# eps_version_0_4_0.net
KiCad netlist of a schematic drawn in EAGLE
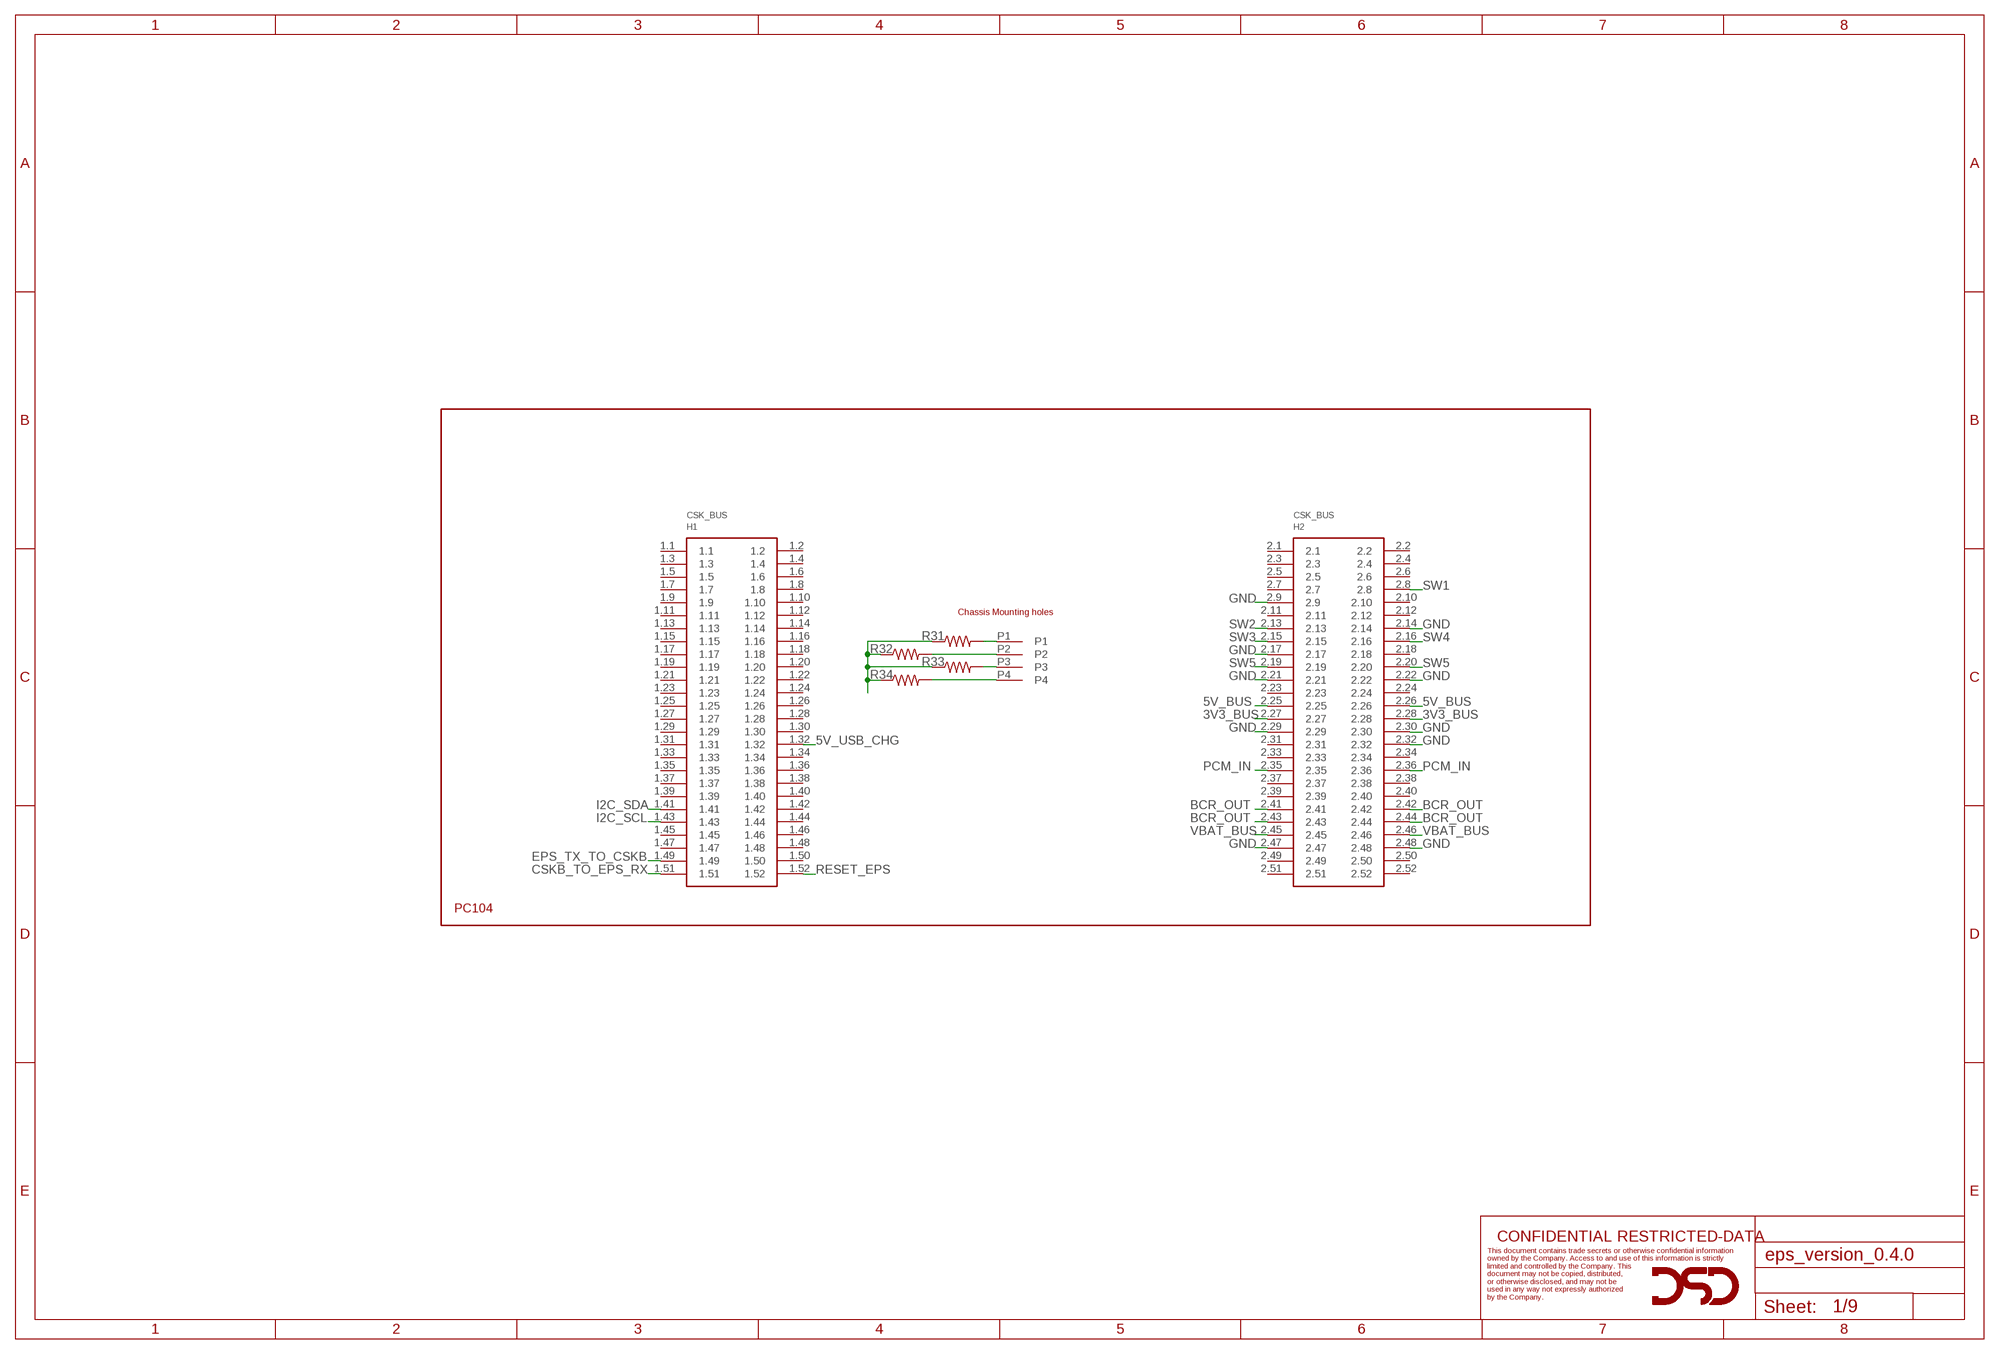
[diagram p0: schematic, sheet 1]
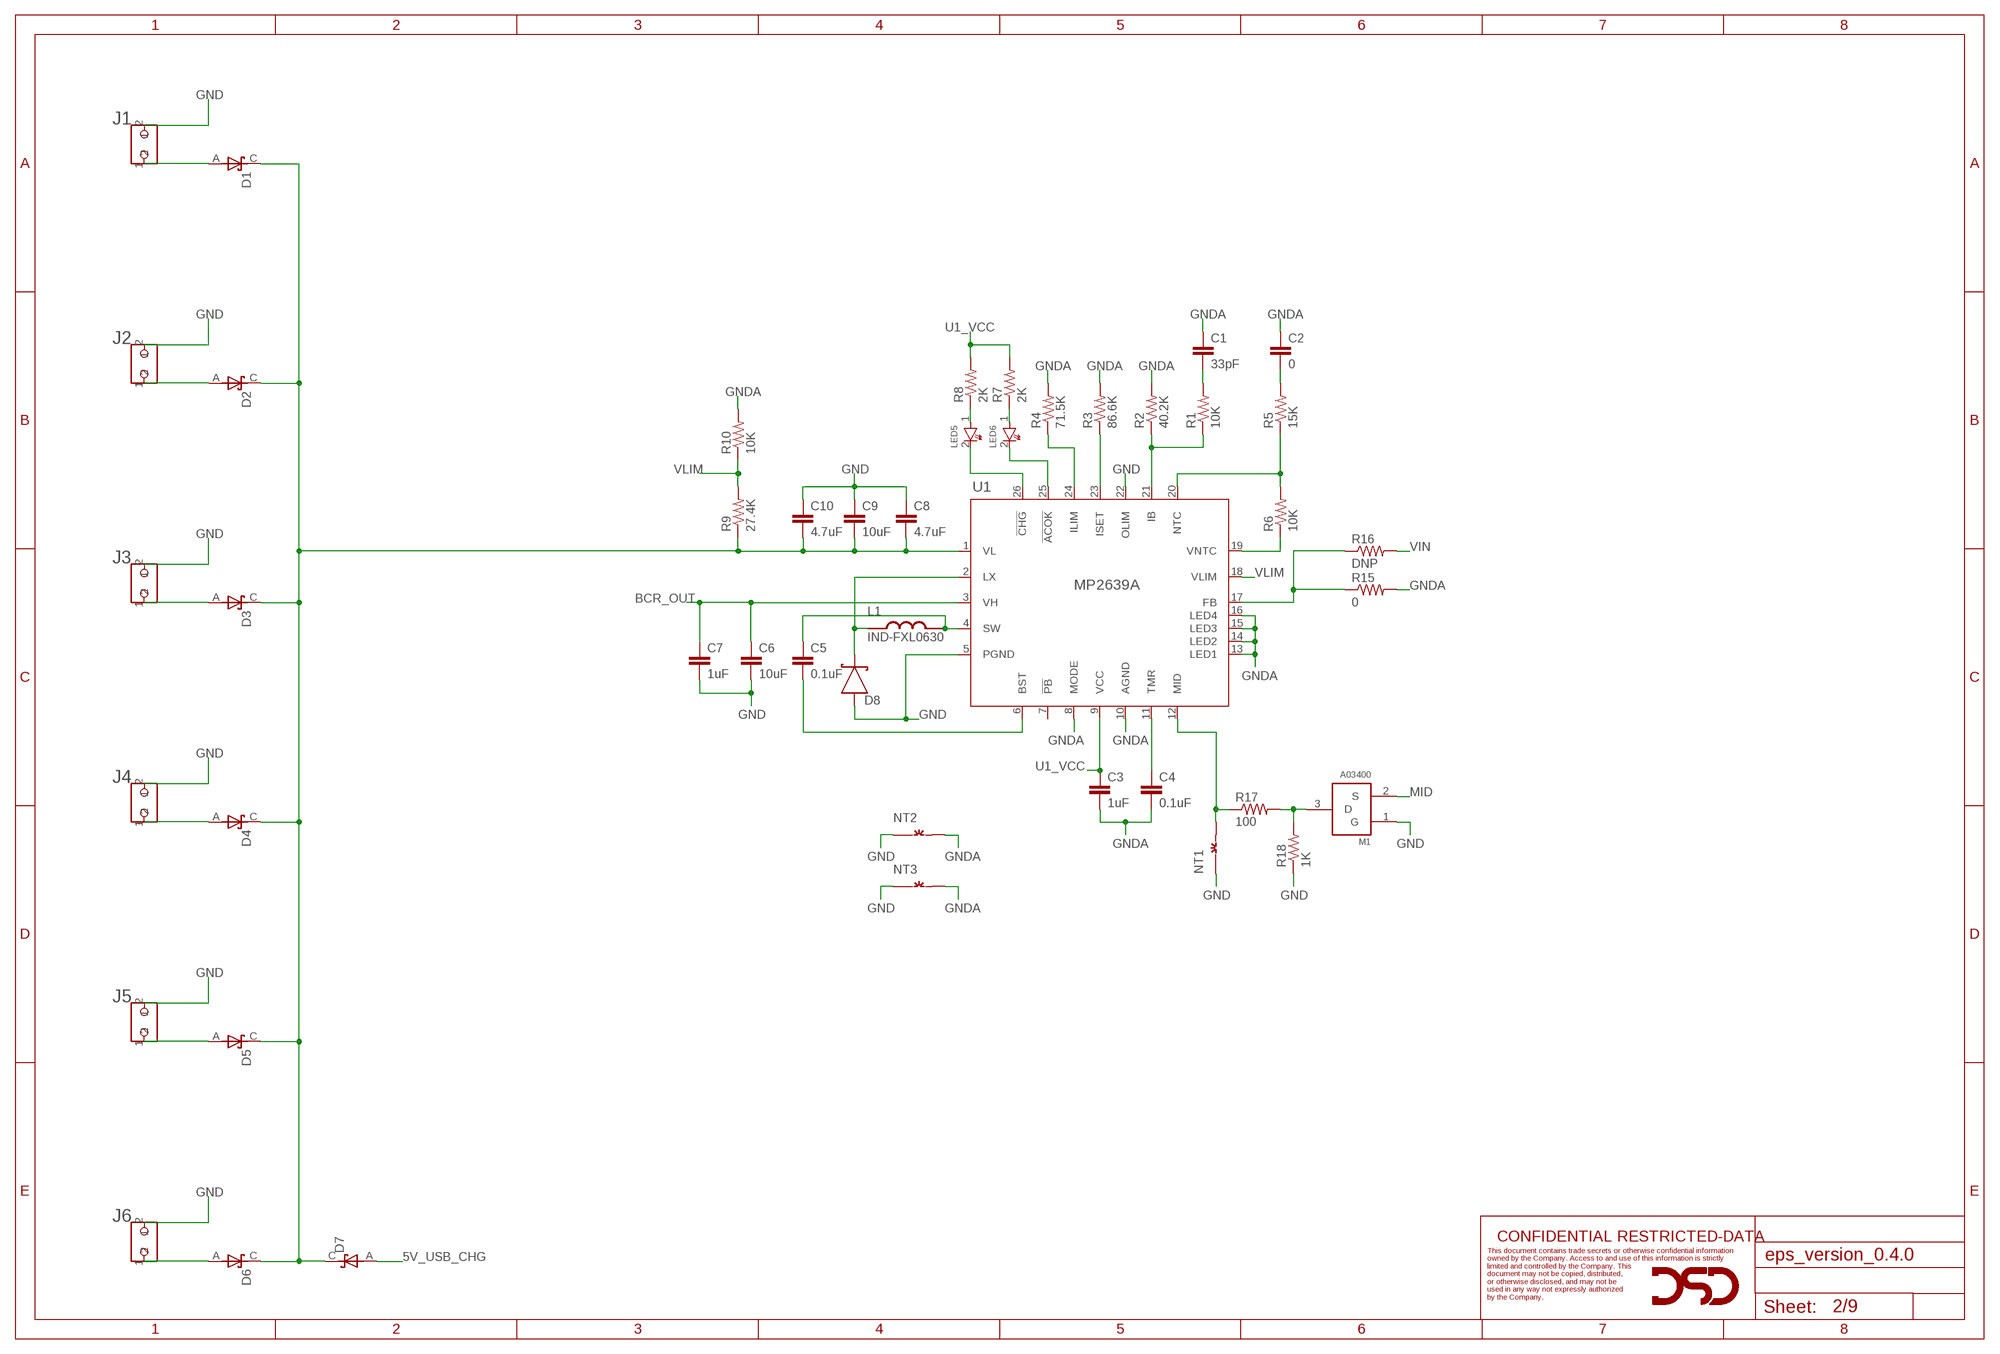
[diagram p1: schematic, sheet 2]
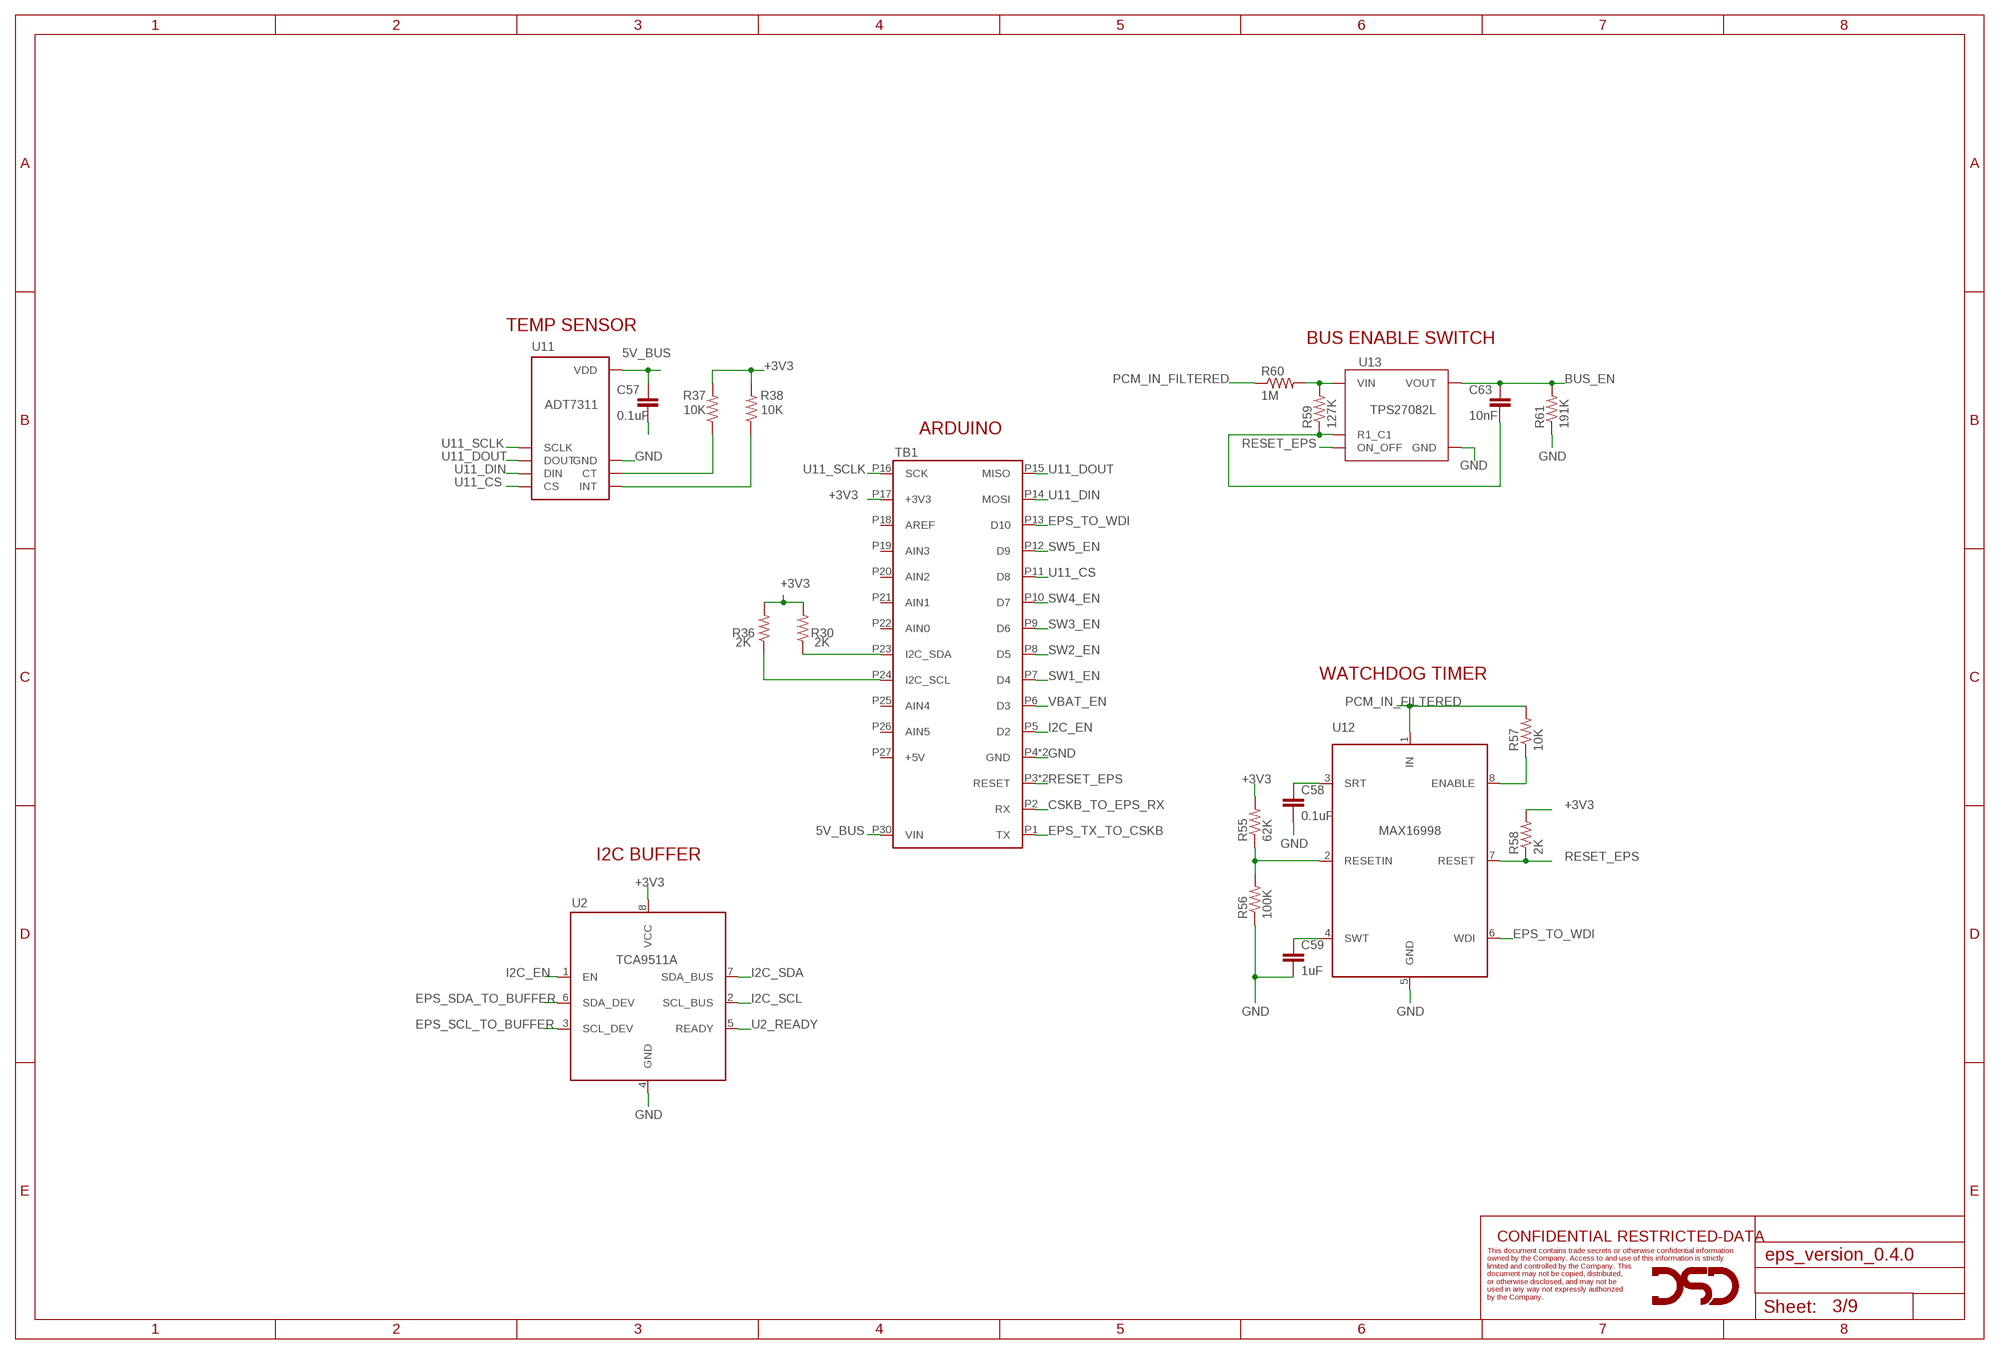
[diagram p2: schematic, sheet 3]
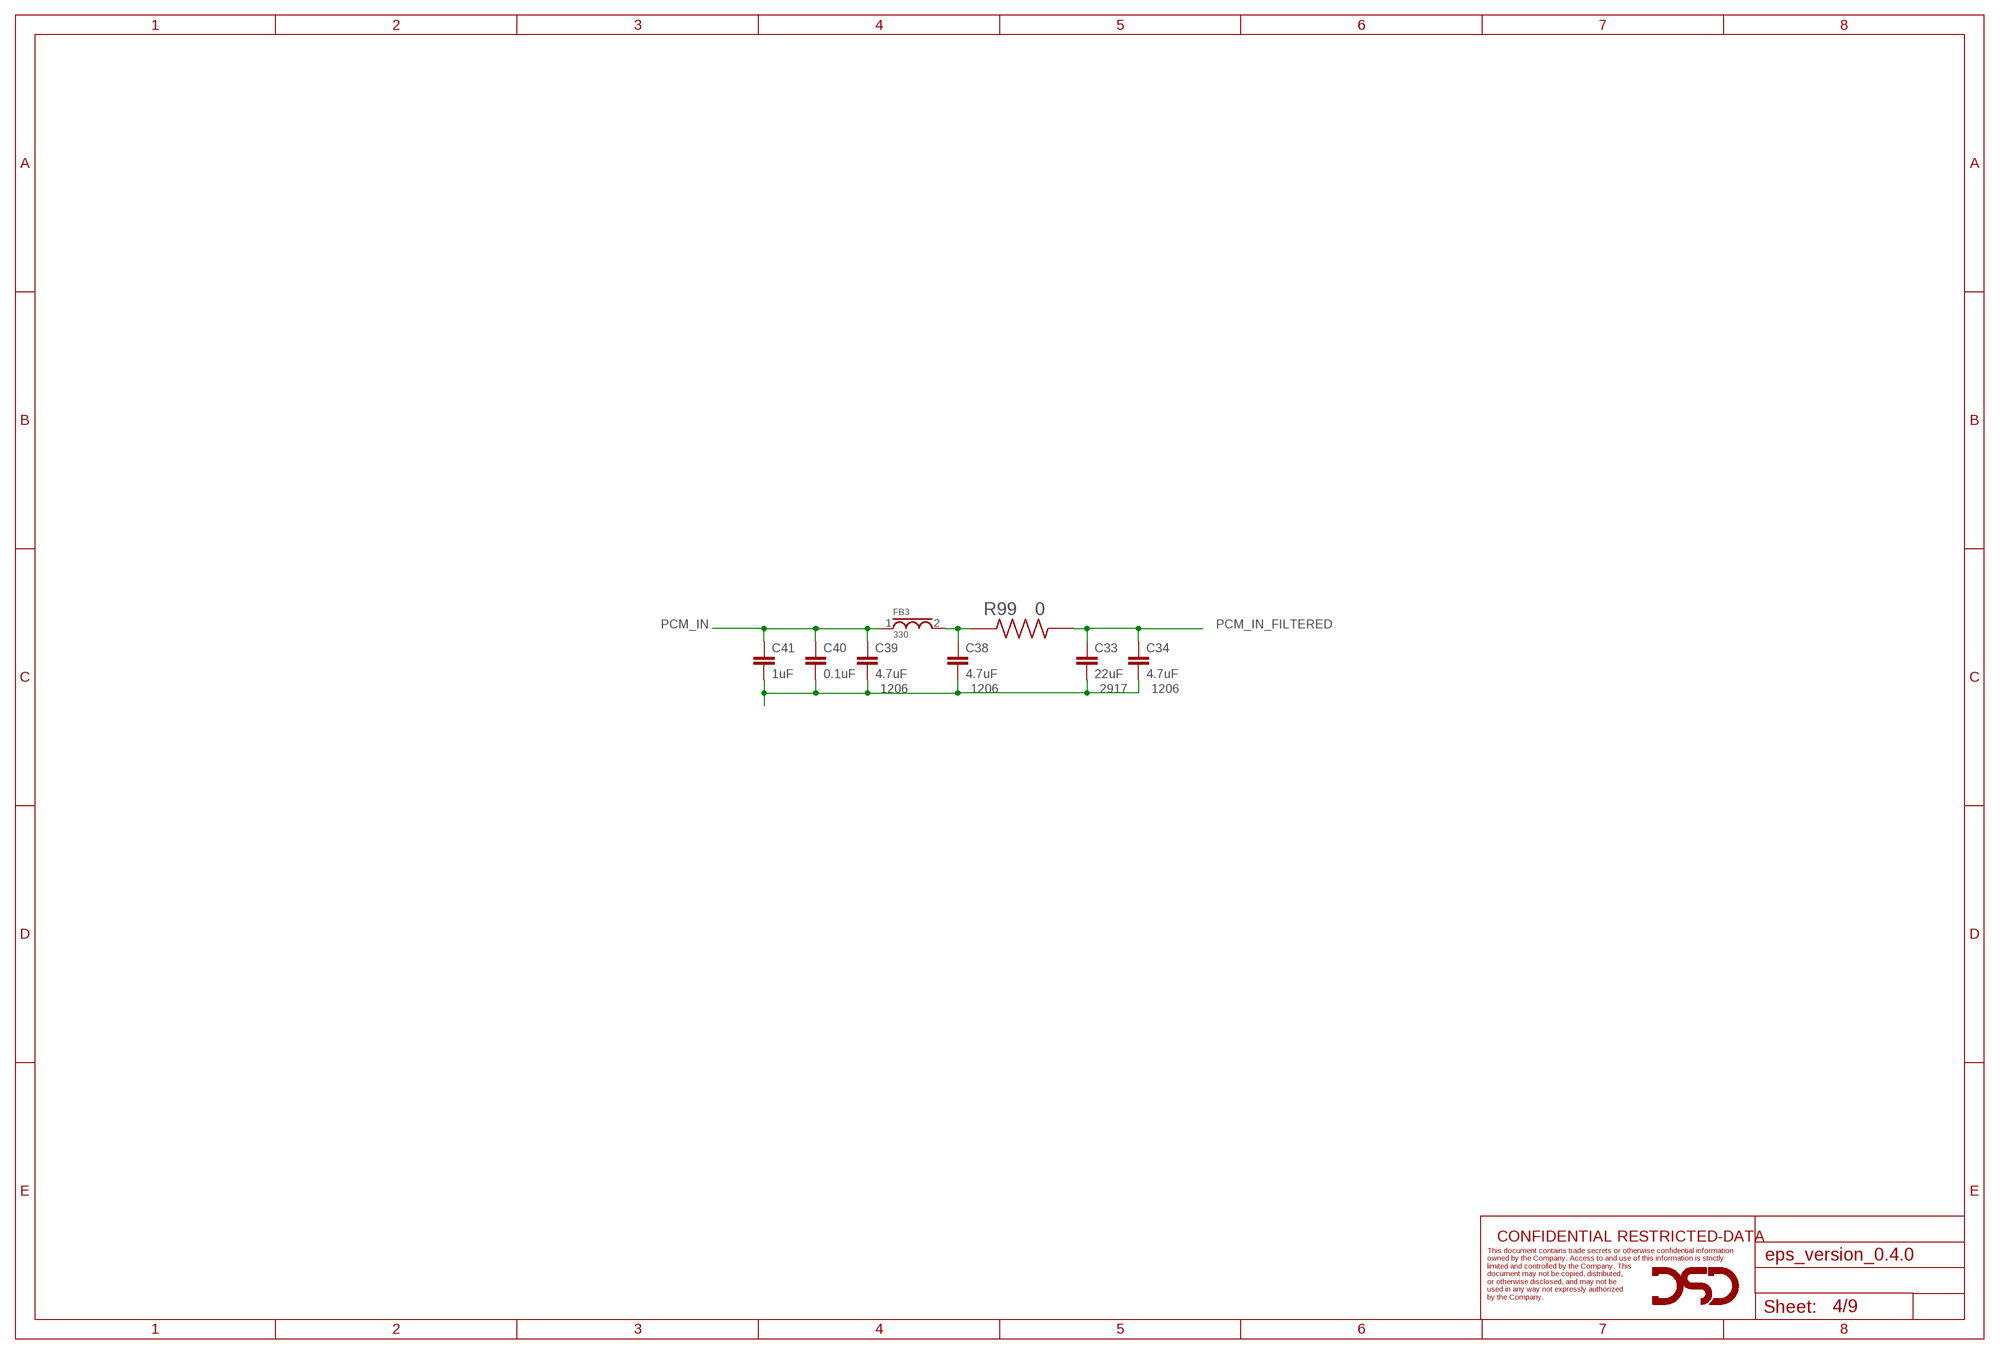
[diagram p3: schematic, sheet 4]
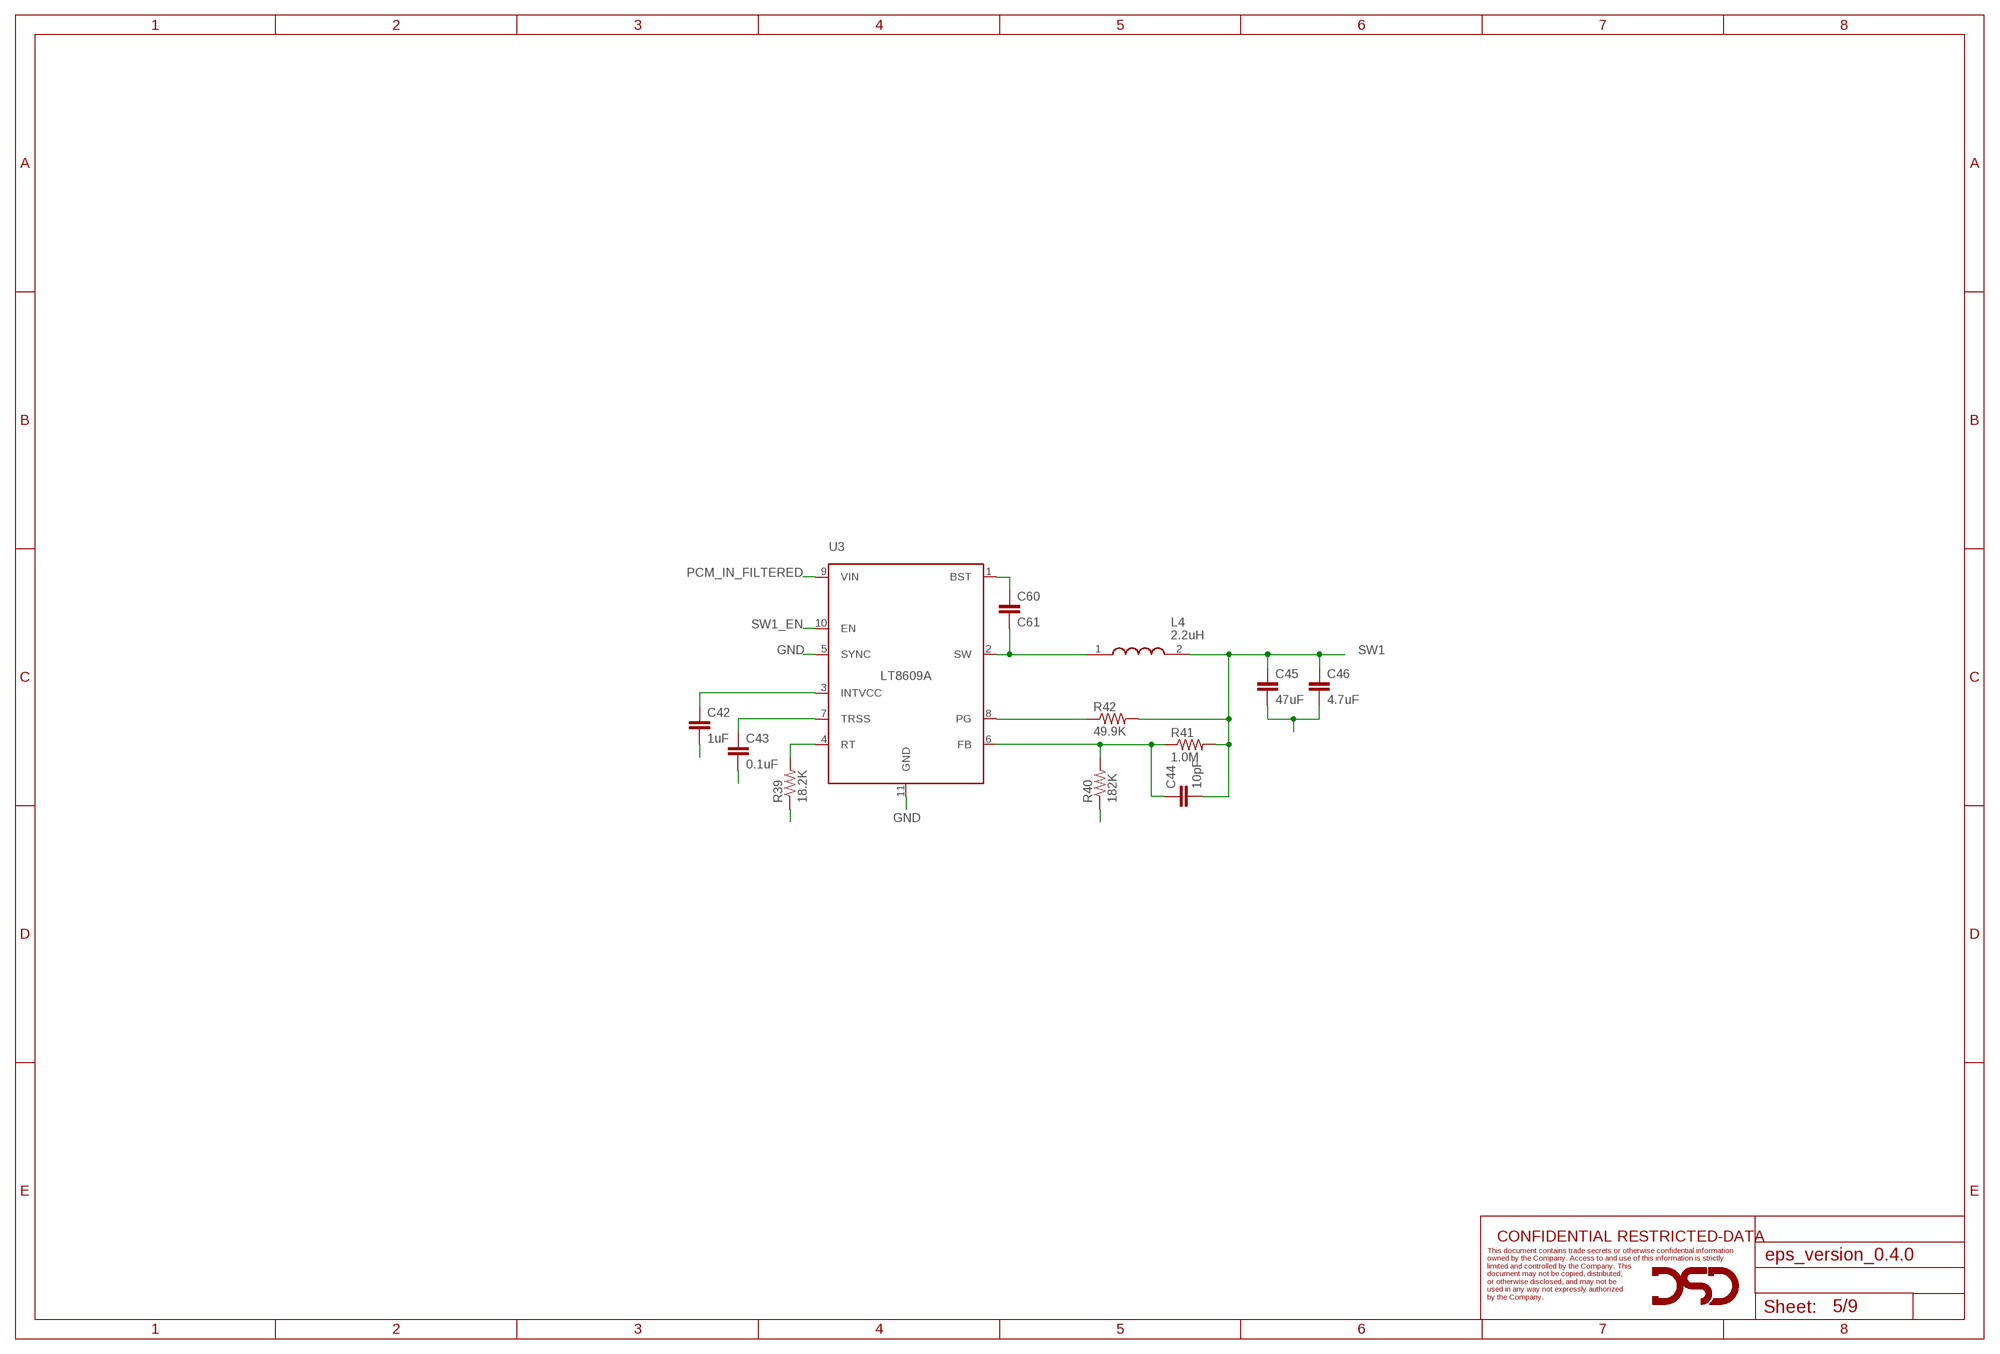
[diagram p4: schematic, sheet 5]
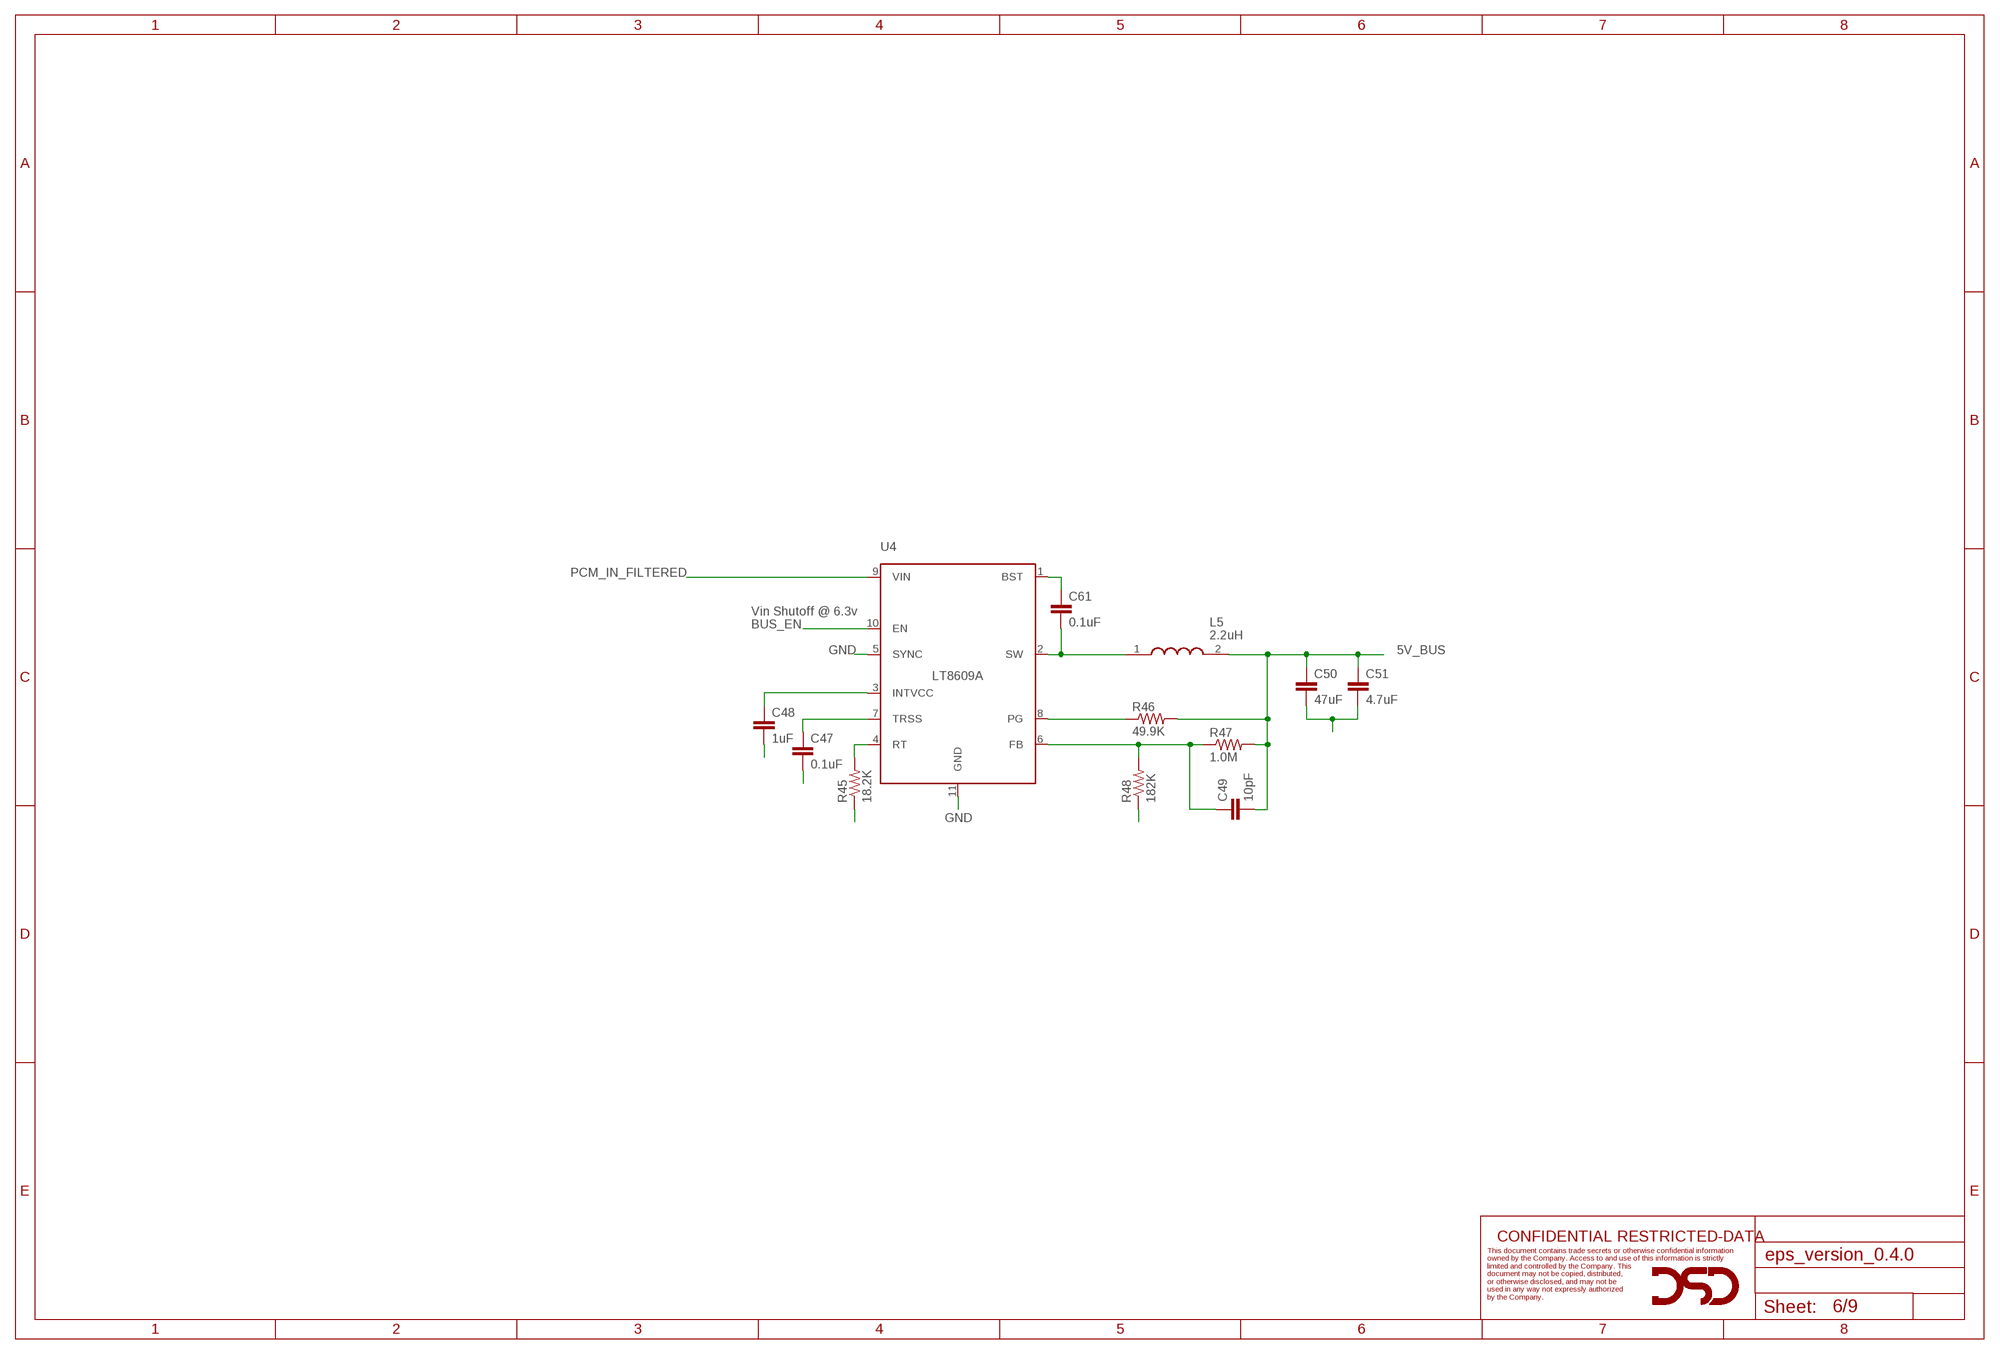
[diagram p5: schematic, sheet 6]
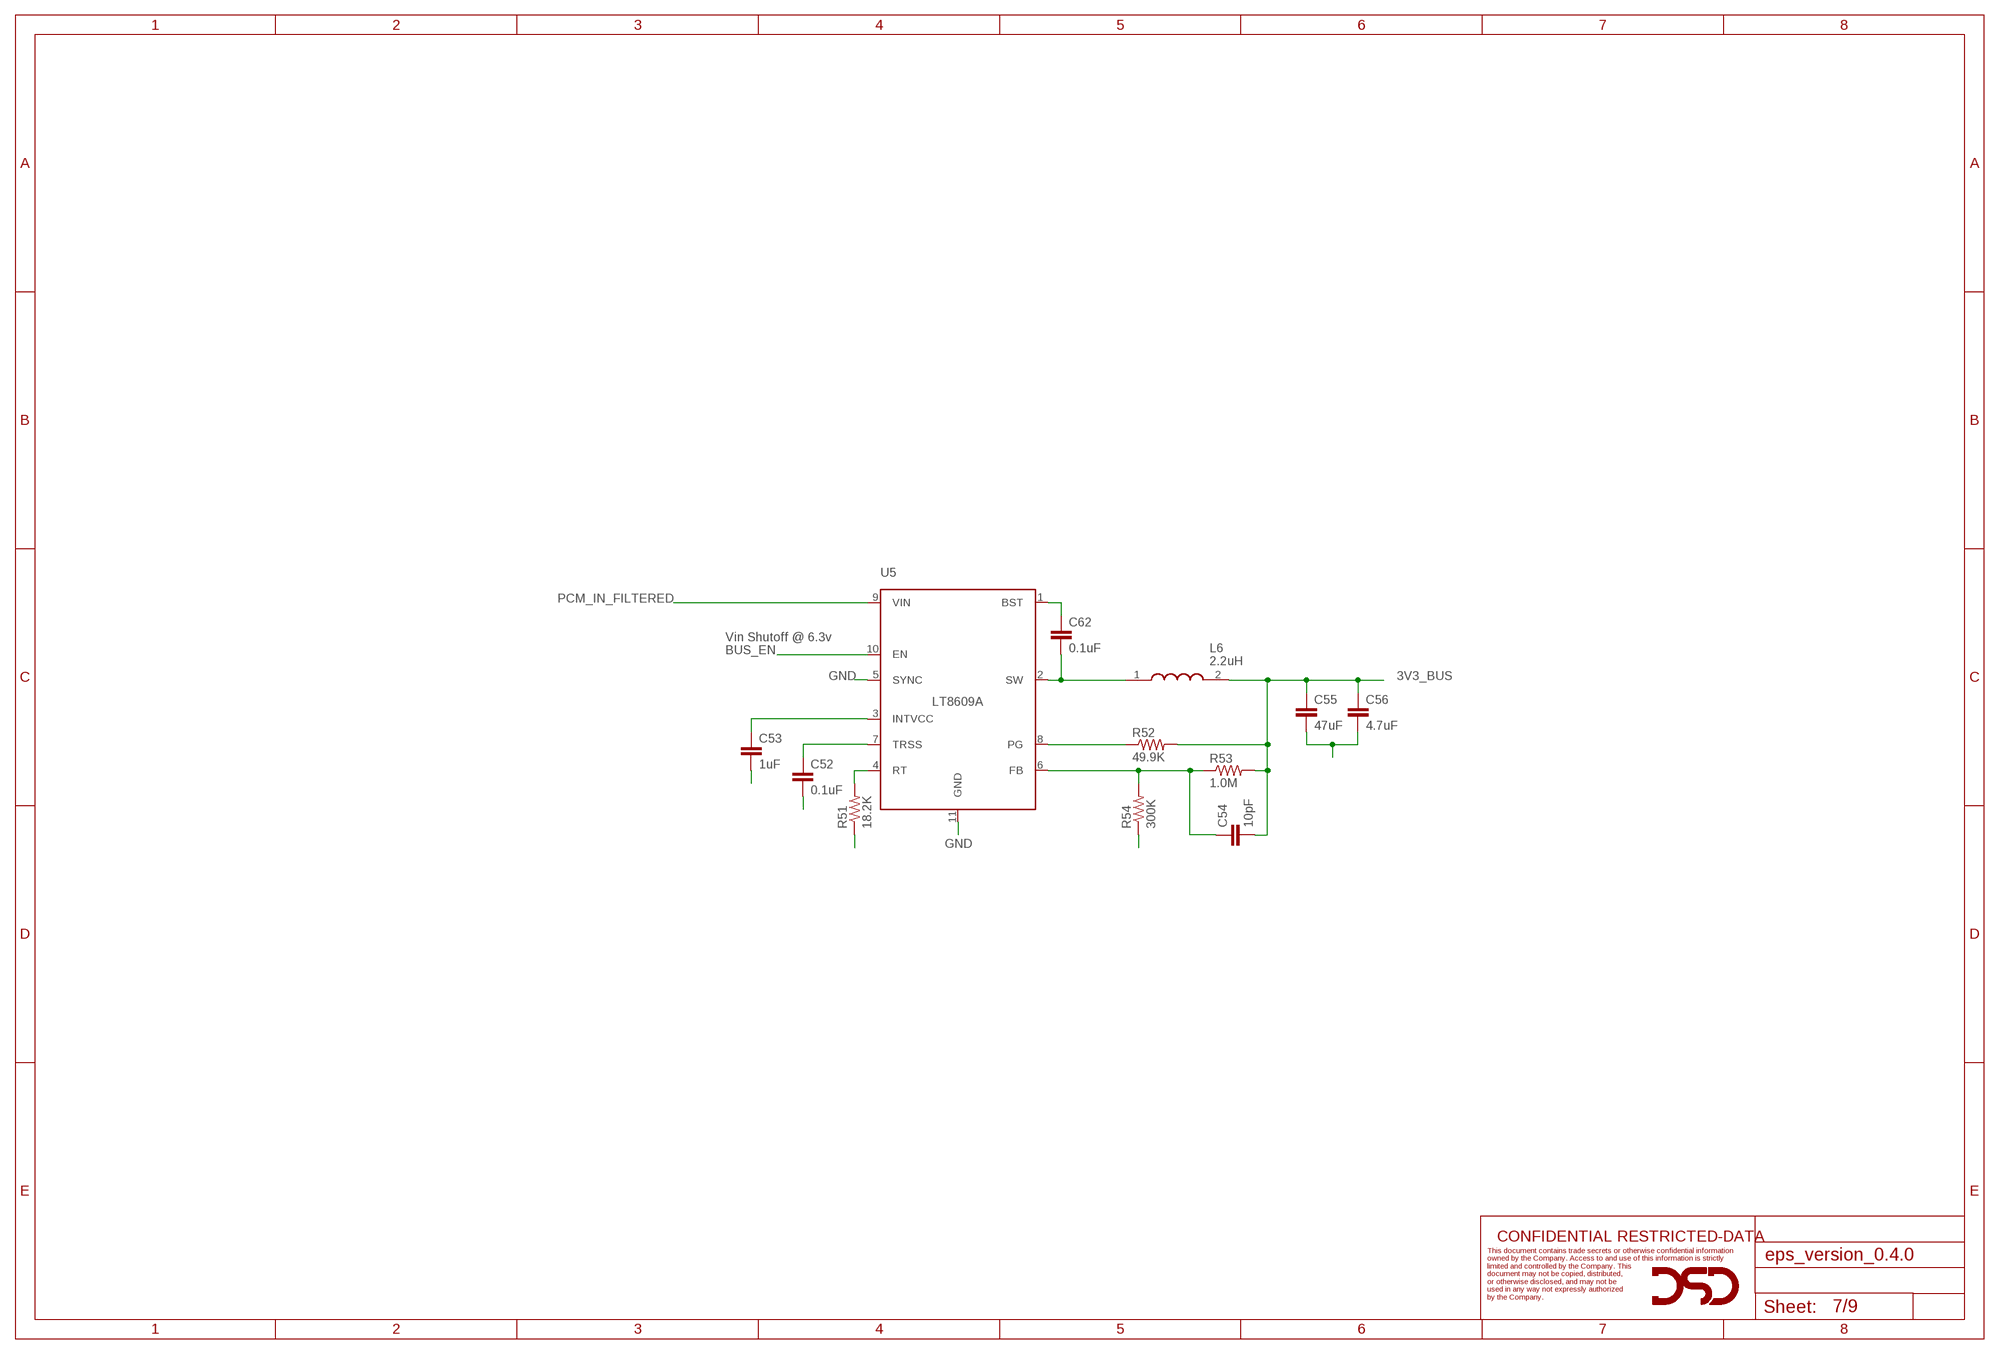
[diagram p6: schematic, sheet 7]
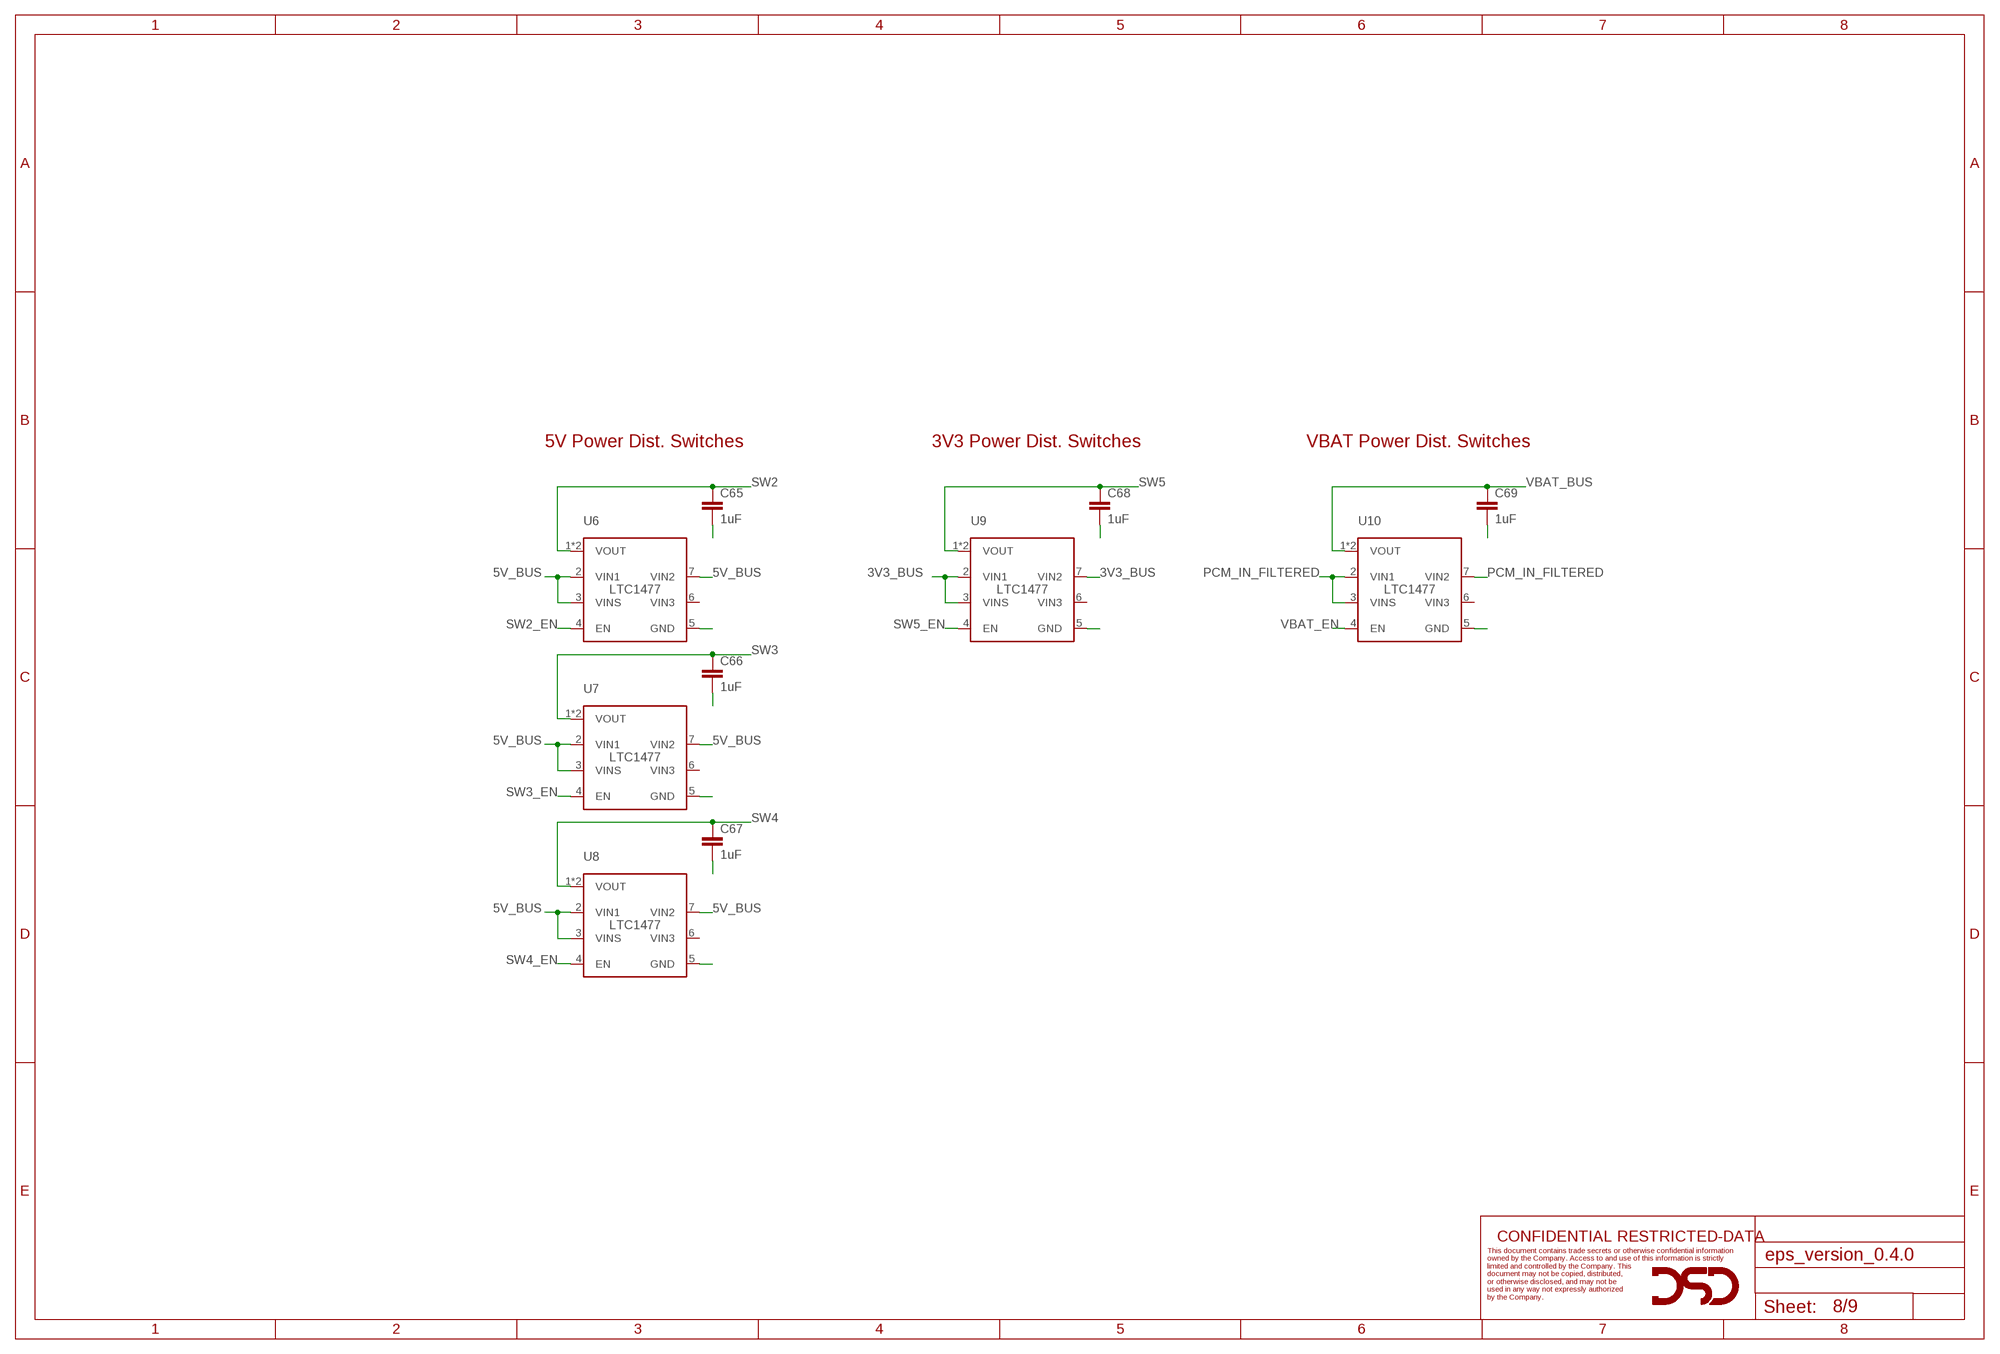
[diagram p7: schematic, sheet 8]
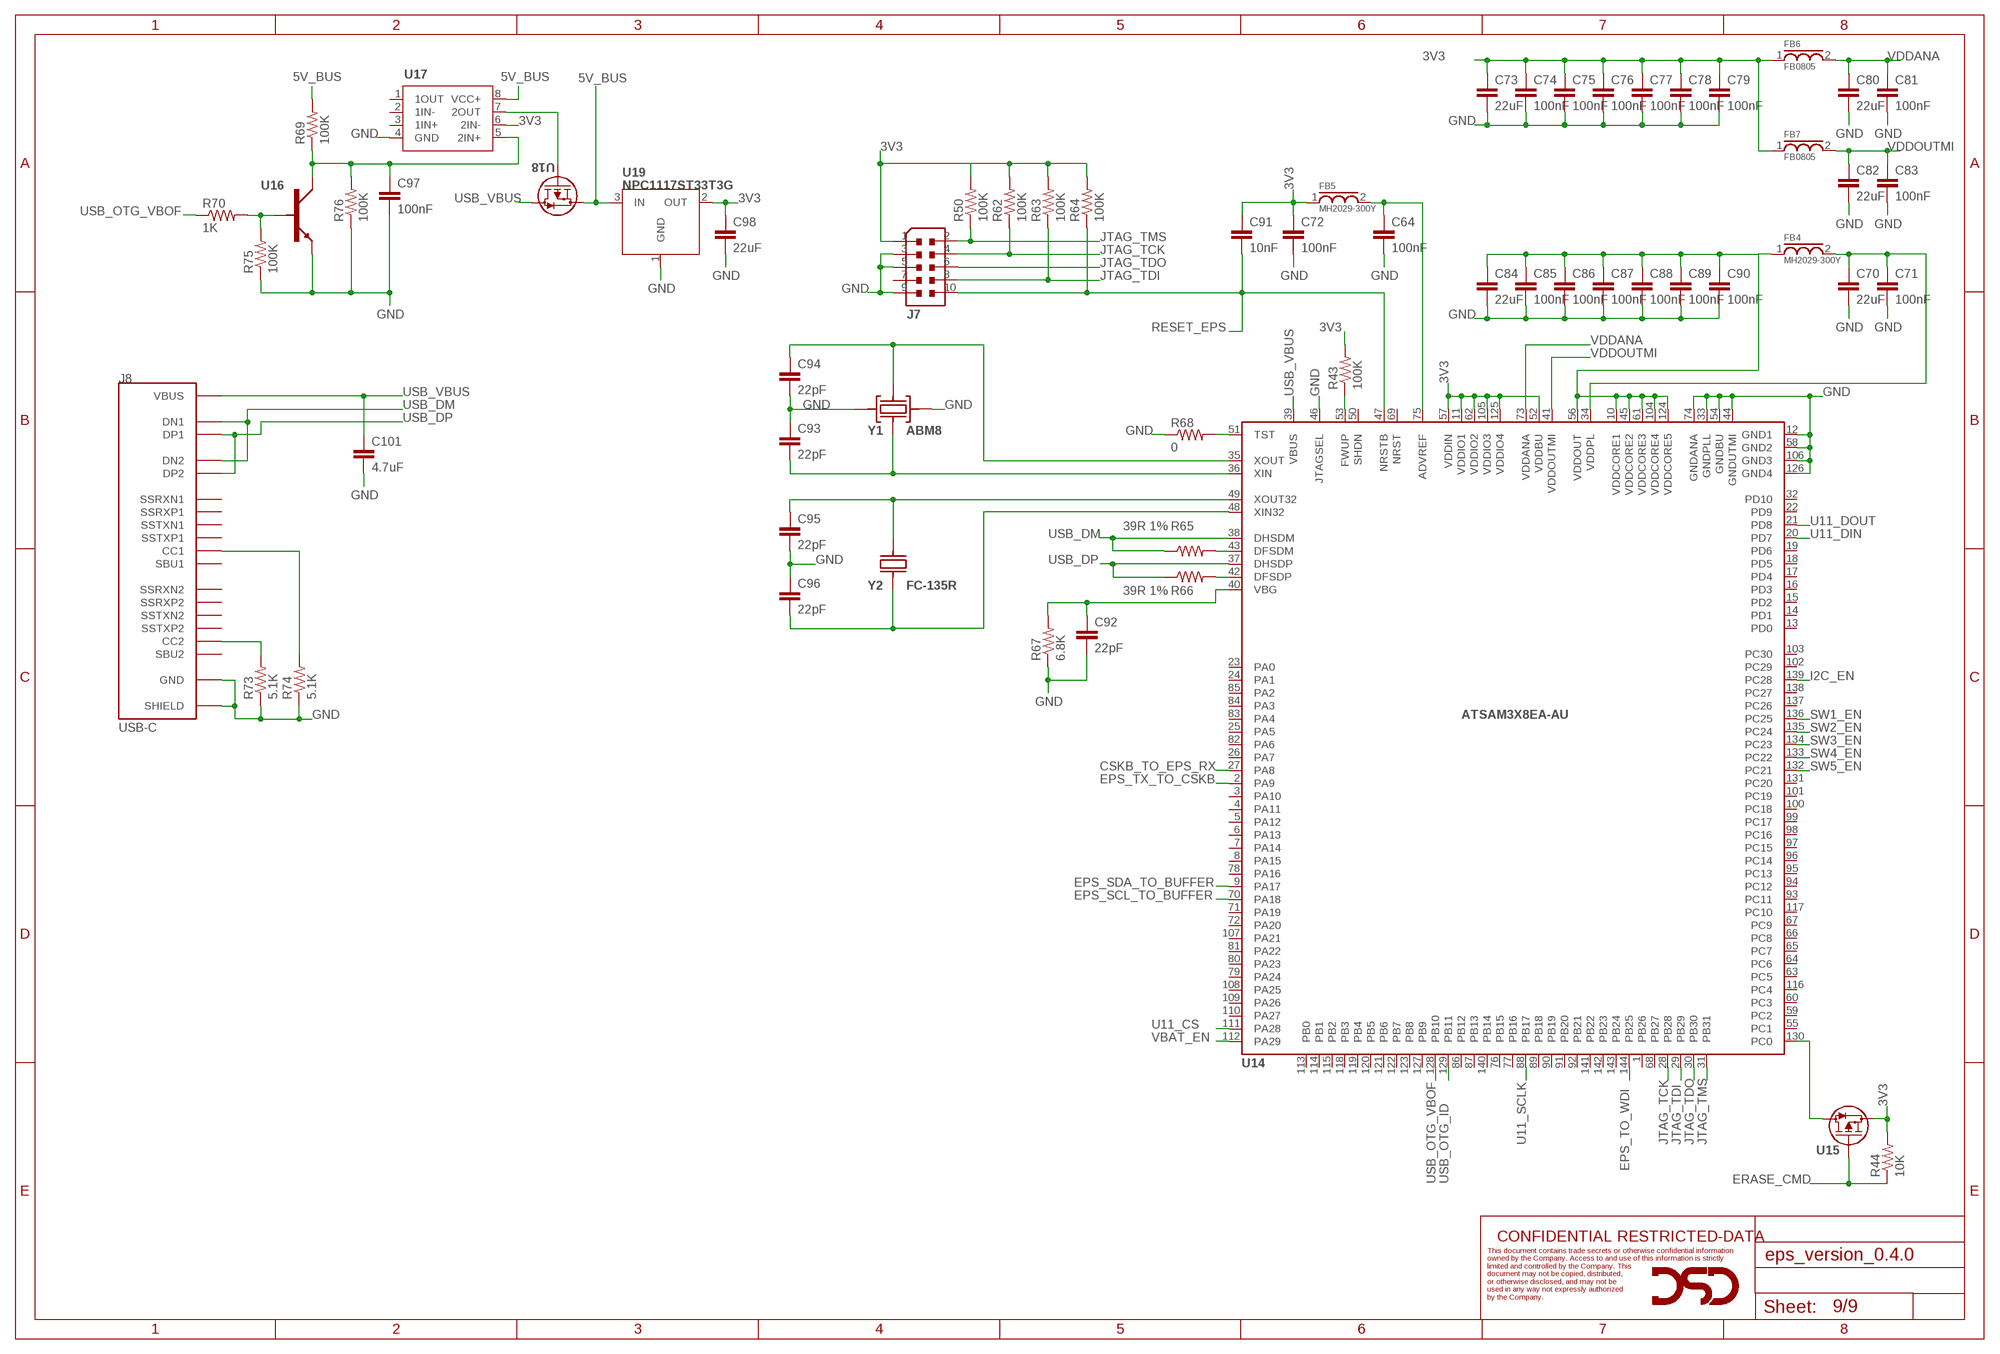
[diagram p8: schematic, sheet 9]

(export (version "E")
  (design (tool "Eeschema 10.0.6"))
  (components
    (comp (ref "C57")
      (value "0.1uF")
      (footprint "eagle-import:0805")
      (libsource (lib "eagle-import") (part "HSFL_Main_Library_CAP0805"))
    )
    (comp (ref "C58")
      (value "0.1uF")
      (footprint "eagle-import:0805")
      (libsource (lib "eagle-import") (part "HSFL_Main_Library_CAP0805"))
    )
    (comp (ref "C59")
      (value "1uF")
      (footprint "eagle-import:0805")
      (libsource (lib "eagle-import") (part "HSFL_Main_Library_CAP0805"))
    )
    (comp (ref "C63")
      (value "10nF")
      (footprint "eagle-import:0805")
      (libsource (lib "eagle-import") (part "HSFL_Main_Library_CAP0805"))
    )
    (comp (ref "R30")
      (value "2K")
      (footprint "eagle-import:0805")
      (libsource (lib "eagle-import") (part "HSFL_Main_Library_RESISTOR0805-RES"))
    )
    (comp (ref "R36")
      (value "2K")
      (footprint "eagle-import:0805")
      (libsource (lib "eagle-import") (part "HSFL_Main_Library_RESISTOR0805-RES"))
    )
    (comp (ref "R37")
      (value "10K")
      (footprint "eagle-import:0805")
      (libsource (lib "eagle-import") (part "HSFL_Main_Library_RESISTOR0805-RES"))
    )
    (comp (ref "R38")
      (value "10K")
      (footprint "eagle-import:0805")
      (libsource (lib "eagle-import") (part "HSFL_Main_Library_RESISTOR0805-RES"))
    )
    (comp (ref "R55")
      (value "62K")
      (footprint "eagle-import:0805")
      (libsource (lib "eagle-import") (part "HSFL_Main_Library_RESISTOR0805-RES"))
    )
    (comp (ref "R56")
      (value "100K")
      (footprint "eagle-import:0805")
      (libsource (lib "eagle-import") (part "HSFL_Main_Library_RESISTOR0805-RES"))
    )
    (comp (ref "R57")
      (value "10K")
      (footprint "eagle-import:0805")
      (libsource (lib "eagle-import") (part "HSFL_Main_Library_RESISTOR0805-RES"))
    )
    (comp (ref "R58")
      (value "2K")
      (footprint "eagle-import:0805")
      (libsource (lib "eagle-import") (part "HSFL_Main_Library_RESISTOR0805-RES"))
    )
    (comp (ref "R59")
      (value "127K")
      (footprint "eagle-import:0805")
      (libsource (lib "eagle-import") (part "HSFL_Main_Library_RESISTOR0805-RES"))
    )
    (comp (ref "R60")
      (value "1M")
      (footprint "eagle-import:0805")
      (libsource (lib "eagle-import") (part "HSFL_Main_Library_RESISTOR0805-RES"))
    )
    (comp (ref "R61")
      (value "191K")
      (footprint "eagle-import:0805")
      (libsource (lib "eagle-import") (part "HSFL_Main_Library_RESISTOR0805-RES"))
    )
    (comp (ref "TB1")
      (value "ARDUINO_NANO")
      (footprint "eagle-import:SHIELD_ARDUINO_NANO")
      (fields (field (name "MF") "Arduino") (field (name "MP") "ARDUINO NANO"))
      (libsource (lib "eagle-import") (part "ARDUINO_NANO"))
    )
    (comp (ref "U2")
      (value "TCA9511A")
      (footprint "eagle-import:SOP65P490X110-8N")
      (libsource (lib "eagle-import") (part "TCA9511A"))
    )
    (comp (ref "U11")
      (value "ADT7311")
      (footprint "eagle-import:SOIC-8")
      (libsource (lib "eagle-import") (part "ADT7311"))
    )
    (comp (ref "U12")
      (value "MAX16998AAUA+")
      (footprint "eagle-import:21-0036K_MXM")
      (libsource (lib "eagle-import") (part "MAX16998AAUA+"))
    )
    (comp (ref "U13")
      (value "Value")
      (footprint "eagle-import:DDC0006A_N")
      (fields (field (name "MANUFACTURER") "Texas Instruments") (field (name "PARTNUMBER") "TPS27082LDDC"))
      (libsource (lib "eagle-import") (part "TPS27082LDDCR"))
    )
    (comp (ref "H1")
      (value "PC104_WCONN")
      (footprint "eagle-import:PC104_WCONN")
      (libsource (lib "eagle-import") (part "PC104_WCONN"))
    )
    (comp (ref "R31")
      (value "1M")
      (footprint "eagle-import:0805")
      (libsource (lib "eagle-import") (part "HSFL_Main_Library_RESISTOR0805-RES"))
    )
    (comp (ref "R32")
      (value "1M")
      (footprint "eagle-import:0805")
      (libsource (lib "eagle-import") (part "HSFL_Main_Library_RESISTOR0805-RES"))
    )
    (comp (ref "R33")
      (value "1M")
      (footprint "eagle-import:0805")
      (libsource (lib "eagle-import") (part "HSFL_Main_Library_RESISTOR0805-RES"))
    )
    (comp (ref "R34")
      (value "1M")
      (footprint "eagle-import:0805")
      (libsource (lib "eagle-import") (part "HSFL_Main_Library_RESISTOR0805-RES"))
    )
    (comp (ref "C33")
      (value "22uF")
      (footprint "eagle-import:CAPMP7343X430N")
      (libsource (lib "eagle-import") (part "CAP_29172917"))
    )
    (comp (ref "C34")
      (value "4.7uF")
      (footprint "eagle-import:1206")
      (libsource (lib "eagle-import") (part "HSFL_Main_Library_CAP1206"))
    )
    (comp (ref "C38")
      (value "4.7uF")
      (footprint "eagle-import:1206")
      (libsource (lib "eagle-import") (part "HSFL_Main_Library_CAP1206"))
    )
    (comp (ref "C39")
      (value "4.7uF")
      (footprint "eagle-import:1206")
      (libsource (lib "eagle-import") (part "HSFL_Main_Library_CAP1206"))
    )
    (comp (ref "C40")
      (value "0.1uF")
      (footprint "eagle-import:0805")
      (libsource (lib "eagle-import") (part "HSFL_Main_Library_CAP0805"))
    )
    (comp (ref "C41")
      (value "1uF")
      (footprint "eagle-import:0805")
      (libsource (lib "eagle-import") (part "HSFL_Main_Library_CAP0805"))
    )
    (comp (ref "FB3")
      (value "330")
      (footprint "eagle-import:0805")
      (libsource (lib "eagle-import") (part "FB_0805"))
    )
    (comp (ref "R99")
      (value "0")
      (footprint "eagle-import:RESC5025X70N")
      (fields
        (field (name "DIGI-KEY_PART_NUMBER") "541-0.0WCT-ND")
        (field (name "MF") "Vishay Dale")
        (field (name "MP") "CRCW20100000Z0EF")
      )
      (libsource (lib "eagle-import") (part "CRCW20100000Z0EF"))
    )
    (comp (ref "C47")
      (value "0.1uF")
      (footprint "eagle-import:0805")
      (libsource (lib "eagle-import") (part "HSFL_Main_Library_CAP0805"))
    )
    (comp (ref "C48")
      (value "1uF")
      (footprint "eagle-import:0805")
      (libsource (lib "eagle-import") (part "HSFL_Main_Library_CAP0805"))
    )
    (comp (ref "C49")
      (value "10pF")
      (footprint "eagle-import:0805")
      (libsource (lib "eagle-import") (part "HSFL_Main_Library_CAP0805"))
    )
    (comp (ref "C50")
      (value "47uF")
      (footprint "eagle-import:1210")
      (libsource (lib "eagle-import") (part "HSFL_Main_Library_CAP1210"))
    )
    (comp (ref "C51")
      (value "4.7uF")
      (footprint "eagle-import:0805")
      (libsource (lib "eagle-import") (part "HSFL_Main_Library_CAP0805"))
    )
    (comp (ref "C61")
      (value "0.1uF")
      (footprint "eagle-import:0805")
      (libsource (lib "eagle-import") (part "HSFL_Main_Library_CAP0805"))
    )
    (comp (ref "L5")
      (value "2.2uH")
      (footprint "eagle-import:XFL4030472MEB")
      (fields
        (field (name "ARROW_PART_NUMBER") "XFL4020-222MEC")
        (field (name "MOUSER_PART_NUMBER") "994-XFL4020-222MEC")
      )
      (libsource (lib "eagle-import") (part "XFL4020-222MEC"))
    )
    (comp (ref "R45")
      (value "18.2K")
      (footprint "eagle-import:0805")
      (libsource (lib "eagle-import") (part "HSFL_Main_Library_RESISTOR0805-RES"))
    )
    (comp (ref "R46")
      (value "49.9K")
      (footprint "eagle-import:0805")
      (libsource (lib "eagle-import") (part "HSFL_Main_Library_RESISTOR0805-RES"))
    )
    (comp (ref "R47")
      (value "1.0M")
      (footprint "eagle-import:0805")
      (libsource (lib "eagle-import") (part "HSFL_Main_Library_RESISTOR0805-RES"))
    )
    (comp (ref "R48")
      (value "182K")
      (footprint "eagle-import:0805")
      (libsource (lib "eagle-import") (part "HSFL_Main_Library_RESISTOR0805-RES"))
    )
    (comp (ref "U4")
      (value "LT8609A")
      (footprint "eagle-import:MSOP-10_MSE")
      (libsource (lib "eagle-import") (part "LT8609A"))
    )
    (comp (ref "C52")
      (value "0.1uF")
      (footprint "eagle-import:0805")
      (libsource (lib "eagle-import") (part "HSFL_Main_Library_CAP0805"))
    )
    (comp (ref "C53")
      (value "1uF")
      (footprint "eagle-import:0805")
      (libsource (lib "eagle-import") (part "HSFL_Main_Library_CAP0805"))
    )
    (comp (ref "C54")
      (value "10pF")
      (footprint "eagle-import:0805")
      (libsource (lib "eagle-import") (part "HSFL_Main_Library_CAP0805"))
    )
    (comp (ref "C55")
      (value "47uF")
      (footprint "eagle-import:1210")
      (libsource (lib "eagle-import") (part "HSFL_Main_Library_CAP1210"))
    )
    (comp (ref "C56")
      (value "4.7uF")
      (footprint "eagle-import:0805")
      (libsource (lib "eagle-import") (part "HSFL_Main_Library_CAP0805"))
    )
    (comp (ref "C62")
      (value "0.1uF")
      (footprint "eagle-import:0805")
      (libsource (lib "eagle-import") (part "HSFL_Main_Library_CAP0805"))
    )
    (comp (ref "L6")
      (value "2.2uH")
      (footprint "eagle-import:XFL4030472MEB")
      (fields
        (field (name "ARROW_PART_NUMBER") "XFL4020-222MEC")
        (field (name "MOUSER_PART_NUMBER") "994-XFL4020-222MEC")
      )
      (libsource (lib "eagle-import") (part "XFL4020-222MEC"))
    )
    (comp (ref "R51")
      (value "18.2K")
      (footprint "eagle-import:0805")
      (libsource (lib "eagle-import") (part "HSFL_Main_Library_RESISTOR0805-RES"))
    )
    (comp (ref "R52")
      (value "49.9K")
      (footprint "eagle-import:0805")
      (libsource (lib "eagle-import") (part "HSFL_Main_Library_RESISTOR0805-RES"))
    )
    (comp (ref "R53")
      (value "1.0M")
      (footprint "eagle-import:0805")
      (libsource (lib "eagle-import") (part "HSFL_Main_Library_RESISTOR0805-RES"))
    )
    (comp (ref "R54")
      (value "300K")
      (footprint "eagle-import:0805")
      (libsource (lib "eagle-import") (part "HSFL_Main_Library_RESISTOR0805-RES"))
    )
    (comp (ref "U5")
      (value "LT8609A")
      (footprint "eagle-import:MSOP-10_MSE")
      (libsource (lib "eagle-import") (part "LT8609A"))
    )
    (comp (ref "C42")
      (value "1uF")
      (footprint "eagle-import:0805")
      (libsource (lib "eagle-import") (part "HSFL_Main_Library_CAP0805"))
    )
    (comp (ref "C43")
      (value "0.1uF")
      (footprint "eagle-import:0805")
      (libsource (lib "eagle-import") (part "HSFL_Main_Library_CAP0805"))
    )
    (comp (ref "C44")
      (value "10pF")
      (footprint "eagle-import:0805")
      (libsource (lib "eagle-import") (part "HSFL_Main_Library_CAP0805"))
    )
    (comp (ref "C45")
      (value "47uF")
      (footprint "eagle-import:1210")
      (libsource (lib "eagle-import") (part "HSFL_Main_Library_CAP1210"))
    )
    (comp (ref "C46")
      (value "4.7uF")
      (footprint "eagle-import:0805")
      (libsource (lib "eagle-import") (part "HSFL_Main_Library_CAP0805"))
    )
    (comp (ref "C60")
      (value "C61")
      (footprint "eagle-import:0805")
      (libsource (lib "eagle-import") (part "HSFL_Main_Library_CAP0805"))
    )
    (comp (ref "L4")
      (value "2.2uH")
      (footprint "eagle-import:XFL4030472MEB")
      (fields
        (field (name "ARROW_PART_NUMBER") "XFL4020-222MEC")
        (field (name "MOUSER_PART_NUMBER") "994-XFL4020-222MEC")
      )
      (libsource (lib "eagle-import") (part "XFL4020-222MEC"))
    )
    (comp (ref "R39")
      (value "18.2K")
      (footprint "eagle-import:0805")
      (libsource (lib "eagle-import") (part "HSFL_Main_Library_RESISTOR0805-RES"))
    )
    (comp (ref "R40")
      (value "182K")
      (footprint "eagle-import:0805")
      (libsource (lib "eagle-import") (part "HSFL_Main_Library_RESISTOR0805-RES"))
    )
    (comp (ref "R41")
      (value "1.0M")
      (footprint "eagle-import:0805")
      (libsource (lib "eagle-import") (part "HSFL_Main_Library_RESISTOR0805-RES"))
    )
    (comp (ref "R42")
      (value "49.9K")
      (footprint "eagle-import:0805")
      (libsource (lib "eagle-import") (part "HSFL_Main_Library_RESISTOR0805-RES"))
    )
    (comp (ref "U3")
      (value "LT8609A")
      (footprint "eagle-import:MSOP-10_MSE")
      (libsource (lib "eagle-import") (part "LT8609A"))
    )
    (comp (ref "C1")
      (value "33pF")
      (footprint "eagle-import:0603-CAP")
      (libsource (lib "eagle-import") (part "CAP0603-CAP"))
    )
    (comp (ref "C2")
      (value "0")
      (footprint "eagle-import:0603-CAP")
      (libsource (lib "eagle-import") (part "CAP0603-CAP"))
    )
    (comp (ref "C3")
      (value "1uF")
      (footprint "eagle-import:0603-CAP")
      (libsource (lib "eagle-import") (part "CAP0603-CAP"))
    )
    (comp (ref "C4")
      (value "0.1uF")
      (footprint "eagle-import:0603-CAP")
      (libsource (lib "eagle-import") (part "CAP0603-CAP"))
    )
    (comp (ref "C5")
      (value "0.1uF")
      (footprint "eagle-import:0603-CAP")
      (libsource (lib "eagle-import") (part "CAP0603-CAP"))
    )
    (comp (ref "C6")
      (value "10uF")
      (footprint "eagle-import:1206")
      (libsource (lib "eagle-import") (part "CAP1206"))
    )
    (comp (ref "C7")
      (value "1uF")
      (footprint "eagle-import:0603-CAP")
      (libsource (lib "eagle-import") (part "CAP0603-CAP"))
    )
    (comp (ref "C8")
      (value "4.7uF")
      (footprint "eagle-import:0603-CAP")
      (libsource (lib "eagle-import") (part "CAP0603-CAP"))
    )
    (comp (ref "C9")
      (value "10uF")
      (footprint "eagle-import:1206")
      (libsource (lib "eagle-import") (part "CAP1206"))
    )
    (comp (ref "C10")
      (value "4.7uF")
      (footprint "eagle-import:0603-CAP")
      (libsource (lib "eagle-import") (part "CAP0603-CAP"))
    )
    (comp (ref "D1")
      (value "DNP")
      (footprint "eagle-import:SODFL3616X98N")
      (fields (field (name "MF") "ON Semiconductor") (field (name "MP") "MBR2H100SFT3G"))
      (libsource (lib "eagle-import") (part "MBR2H100SFT3G"))
    )
    (comp (ref "D2")
      (value "DNP")
      (footprint "eagle-import:SODFL3616X98N")
      (fields (field (name "MF") "ON Semiconductor") (field (name "MP") "MBR2H100SFT3G"))
      (libsource (lib "eagle-import") (part "MBR2H100SFT3G"))
    )
    (comp (ref "D3")
      (value "DNP")
      (footprint "eagle-import:SODFL3616X98N")
      (fields (field (name "MF") "ON Semiconductor") (field (name "MP") "MBR2H100SFT3G"))
      (libsource (lib "eagle-import") (part "MBR2H100SFT3G"))
    )
    (comp (ref "D4")
      (value "DNP")
      (footprint "eagle-import:SODFL3616X98N")
      (fields (field (name "MF") "ON Semiconductor") (field (name "MP") "MBR2H100SFT3G"))
      (libsource (lib "eagle-import") (part "MBR2H100SFT3G"))
    )
    (comp (ref "D5")
      (value "DNP")
      (footprint "eagle-import:SODFL3616X98N")
      (fields (field (name "MF") "ON Semiconductor") (field (name "MP") "MBR2H100SFT3G"))
      (libsource (lib "eagle-import") (part "MBR2H100SFT3G"))
    )
    (comp (ref "D6")
      (value "DNP")
      (footprint "eagle-import:SODFL3616X98N")
      (fields (field (name "MF") "ON Semiconductor") (field (name "MP") "MBR2H100SFT3G"))
      (libsource (lib "eagle-import") (part "MBR2H100SFT3G"))
    )
    (comp (ref "D7")
      (value "DNP")
      (footprint "eagle-import:SODFL3616X98N")
      (fields (field (name "MF") "ON Semiconductor") (field (name "MP") "MBR2H100SFT3G"))
      (libsource (lib "eagle-import") (part "MBR2H100SFT3G"))
    )
    (comp (ref "D8")
      (value "1N5819HW")
      (footprint "eagle-import:SOD123")
      (libsource (lib "eagle-import") (part "DIODE-SOD123"))
    )
    (comp (ref "J1")
      (value "2PIN_HEADER")
      (footprint "eagle-import:2MM_2PIN_HEADER")
      (libsource (lib "eagle-import") (part "2PIN_HEADER"))
    )
    (comp (ref "J2")
      (value "2PIN_HEADER")
      (footprint "eagle-import:2MM_2PIN_HEADER")
      (libsource (lib "eagle-import") (part "2PIN_HEADER"))
    )
    (comp (ref "J3")
      (value "2PIN_HEADER")
      (footprint "eagle-import:2MM_2PIN_HEADER")
      (libsource (lib "eagle-import") (part "2PIN_HEADER"))
    )
    (comp (ref "J4")
      (value "2PIN_HEADER")
      (footprint "eagle-import:2MM_2PIN_HEADER")
      (libsource (lib "eagle-import") (part "2PIN_HEADER"))
    )
    (comp (ref "J5")
      (value "2PIN_HEADER")
      (footprint "eagle-import:2MM_2PIN_HEADER")
      (libsource (lib "eagle-import") (part "2PIN_HEADER"))
    )
    (comp (ref "J6")
      (value "2PIN_HEADER")
      (footprint "eagle-import:2MM_2PIN_HEADER")
      (libsource (lib "eagle-import") (part "2PIN_HEADER"))
    )
    (comp (ref "L1")
      (value "IND-FXL0630")
      (footprint "eagle-import:FXL0630")
      (libsource (lib "eagle-import") (part "IND-FXL0630"))
    )
    (comp (ref "LED5")
      (value "LED_0805")
      (footprint "eagle-import:LED_0805")
      (libsource (lib "eagle-import") (part "LED_0805"))
    )
    (comp (ref "LED6")
      (value "LED_0805")
      (footprint "eagle-import:LED_0805")
      (libsource (lib "eagle-import") (part "LED_0805"))
    )
    (comp (ref "M1")
      (value "A03400")
      (footprint "eagle-import:SOT23")
      (libsource (lib "eagle-import") (part "SOT23_NMOS"))
    )
    (comp (ref "NT1")
      (value "GND-GNDA1,27MM")
      (footprint "eagle-import:GND-GNDA-1,27MM")
      (libsource (lib "eagle-import") (part "GND-GNDA1,27MM"))
    )
    (comp (ref "NT2")
      (value "GND-GNDA1,27MM")
      (footprint "eagle-import:GND-GNDA-1,27MM")
      (libsource (lib "eagle-import") (part "GND-GNDA1,27MM"))
    )
    (comp (ref "NT3")
      (value "GND-GNDA1,27MM")
      (footprint "eagle-import:GND-GNDA-1,27MM")
      (libsource (lib "eagle-import") (part "GND-GNDA1,27MM"))
    )
    (comp (ref "R1")
      (value "10K")
      (footprint "eagle-import:0603-RES")
      (libsource (lib "eagle-import") (part "RESISTOR0603-RES"))
    )
    (comp (ref "R2")
      (value "40.2K")
      (footprint "eagle-import:0603-RES")
      (libsource (lib "eagle-import") (part "RESISTOR0603-RES"))
    )
    (comp (ref "R3")
      (value "86.6K")
      (footprint "eagle-import:0603-RES")
      (libsource (lib "eagle-import") (part "RESISTOR0603-RES"))
    )
    (comp (ref "R4")
      (value "71.5K")
      (footprint "eagle-import:0603-RES")
      (libsource (lib "eagle-import") (part "RESISTOR0603-RES"))
    )
    (comp (ref "R5")
      (value "15K")
      (footprint "eagle-import:0805")
      (libsource (lib "eagle-import") (part "RESISTOR0805-RES"))
    )
    (comp (ref "R6")
      (value "10K")
      (footprint "eagle-import:0805")
      (libsource (lib "eagle-import") (part "RESISTOR0805-RES"))
    )
    (comp (ref "R7")
      (value "2K")
      (footprint "eagle-import:0603-RES")
      (libsource (lib "eagle-import") (part "RESISTOR0603-RES"))
    )
    (comp (ref "R8")
      (value "2K")
      (footprint "eagle-import:0603-RES")
      (libsource (lib "eagle-import") (part "RESISTOR0603-RES"))
    )
    (comp (ref "R9")
      (value "27.4K")
      (footprint "eagle-import:0603-RES")
      (libsource (lib "eagle-import") (part "RESISTOR0603-RES"))
    )
    (comp (ref "R10")
      (value "10K")
      (footprint "eagle-import:0603-RES")
      (libsource (lib "eagle-import") (part "RESISTOR0603-RES"))
    )
    (comp (ref "R15")
      (value "0")
      (footprint "eagle-import:0603-RES")
      (libsource (lib "eagle-import") (part "RESISTOR0603-RES"))
    )
    (comp (ref "R16")
      (value "DNP")
      (footprint "eagle-import:0603-RES")
      (libsource (lib "eagle-import") (part "RESISTOR0603-RES"))
    )
    (comp (ref "R17")
      (value "100")
      (footprint "eagle-import:0603-RES")
      (libsource (lib "eagle-import") (part "RESISTOR0603-RES"))
    )
    (comp (ref "R18")
      (value "1K")
      (footprint "eagle-import:0603-RES")
      (libsource (lib "eagle-import") (part "RESISTOR0603-RES"))
    )
    (comp (ref "U1")
      (value "MP2639A")
      (footprint "eagle-import:IC26_MP2639A_MNP")
      (fields (field (name "COPYRIGHT") "Copyright (C) 2018 Accelerated Designs. All rights reserved"))
      (libsource (lib "eagle-import") (part "MP2639A"))
    )
    (comp (ref "C65")
      (value "1uF")
      (footprint "eagle-import:0805")
      (libsource (lib "eagle-import") (part "HSFL_Main_Library_CAP0805"))
    )
    (comp (ref "C66")
      (value "1uF")
      (footprint "eagle-import:0805")
      (libsource (lib "eagle-import") (part "HSFL_Main_Library_CAP0805"))
    )
    (comp (ref "C67")
      (value "1uF")
      (footprint "eagle-import:0805")
      (libsource (lib "eagle-import") (part "HSFL_Main_Library_CAP0805"))
    )
    (comp (ref "C68")
      (value "1uF")
      (footprint "eagle-import:0805")
      (libsource (lib "eagle-import") (part "HSFL_Main_Library_CAP0805"))
    )
    (comp (ref "C69")
      (value "1uF")
      (footprint "eagle-import:0805")
      (libsource (lib "eagle-import") (part "HSFL_Main_Library_CAP0805"))
    )
    (comp (ref "U6")
      (value "LTC1477")
      (footprint "eagle-import:SO8")
      (libsource (lib "eagle-import") (part "LTC1477"))
    )
    (comp (ref "U7")
      (value "LTC1477")
      (footprint "eagle-import:SO8")
      (libsource (lib "eagle-import") (part "LTC1477"))
    )
    (comp (ref "U8")
      (value "LTC1477")
      (footprint "eagle-import:SO8")
      (libsource (lib "eagle-import") (part "LTC1477"))
    )
    (comp (ref "U9")
      (value "LTC1477")
      (footprint "eagle-import:SO8")
      (libsource (lib "eagle-import") (part "LTC1477"))
    )
    (comp (ref "U10")
      (value "LTC1477")
      (footprint "eagle-import:SO8")
      (libsource (lib "eagle-import") (part "LTC1477"))
    )
    (comp (ref "C64")
      (value "100nF")
      (footprint "eagle-import:0603-CAP")
      (libsource (lib "eagle-import") (part "CAP0603-CAP"))
    )
    (comp (ref "C70")
      (value "22uF")
      (footprint "eagle-import:0603-CAP")
      (libsource (lib "eagle-import") (part "CAP0603-CAP"))
    )
    (comp (ref "C71")
      (value "100nF")
      (footprint "eagle-import:0603-CAP")
      (libsource (lib "eagle-import") (part "CAP0603-CAP"))
    )
    (comp (ref "C72")
      (value "100nF")
      (footprint "eagle-import:0603-CAP")
      (libsource (lib "eagle-import") (part "CAP0603-CAP"))
    )
    (comp (ref "C73")
      (value "22uF")
      (footprint "eagle-import:0603-CAP")
      (libsource (lib "eagle-import") (part "CAP0603-CAP"))
    )
    (comp (ref "C74")
      (value "100nF")
      (footprint "eagle-import:0603-CAP")
      (libsource (lib "eagle-import") (part "CAP0603-CAP"))
    )
    (comp (ref "C75")
      (value "100nF")
      (footprint "eagle-import:0603-CAP")
      (libsource (lib "eagle-import") (part "CAP0603-CAP"))
    )
    (comp (ref "C76")
      (value "100nF")
      (footprint "eagle-import:0603-CAP")
      (libsource (lib "eagle-import") (part "CAP0603-CAP"))
    )
    (comp (ref "C77")
      (value "100nF")
      (footprint "eagle-import:0603-CAP")
      (libsource (lib "eagle-import") (part "CAP0603-CAP"))
    )
    (comp (ref "C78")
      (value "100nF")
      (footprint "eagle-import:0603-CAP")
      (libsource (lib "eagle-import") (part "CAP0603-CAP"))
    )
    (comp (ref "C79")
      (value "100nF")
      (footprint "eagle-import:0603-CAP")
      (libsource (lib "eagle-import") (part "CAP0603-CAP"))
    )
    (comp (ref "C80")
      (value "22uF")
      (footprint "eagle-import:0603-CAP")
      (libsource (lib "eagle-import") (part "CAP0603-CAP"))
    )
    (comp (ref "C81")
      (value "100nF")
      (footprint "eagle-import:0603-CAP")
      (libsource (lib "eagle-import") (part "CAP0603-CAP"))
    )
    (comp (ref "C82")
      (value "22uF")
      (footprint "eagle-import:0603-CAP")
      (libsource (lib "eagle-import") (part "CAP0603-CAP"))
    )
    (comp (ref "C83")
      (value "100nF")
      (footprint "eagle-import:0603-CAP")
      (libsource (lib "eagle-import") (part "CAP0603-CAP"))
    )
    (comp (ref "C84")
      (value "22uF")
      (footprint "eagle-import:0603-CAP")
      (libsource (lib "eagle-import") (part "CAP0603-CAP"))
    )
    (comp (ref "C85")
      (value "100nF")
      (footprint "eagle-import:0603-CAP")
      (libsource (lib "eagle-import") (part "CAP0603-CAP"))
    )
    (comp (ref "C86")
      (value "100nF")
      (footprint "eagle-import:0603-CAP")
      (libsource (lib "eagle-import") (part "CAP0603-CAP"))
    )
    (comp (ref "C87")
      (value "100nF")
      (footprint "eagle-import:0603-CAP")
      (libsource (lib "eagle-import") (part "CAP0603-CAP"))
    )
    (comp (ref "C88")
      (value "100nF")
      (footprint "eagle-import:0603-CAP")
      (libsource (lib "eagle-import") (part "CAP0603-CAP"))
    )
    (comp (ref "C89")
      (value "100nF")
      (footprint "eagle-import:0603-CAP")
      (libsource (lib "eagle-import") (part "CAP0603-CAP"))
    )
    (comp (ref "C90")
      (value "100nF")
      (footprint "eagle-import:0603-CAP")
      (libsource (lib "eagle-import") (part "CAP0603-CAP"))
    )
    (comp (ref "C91")
      (value "10nF")
      (footprint "eagle-import:0603-CAP")
      (libsource (lib "eagle-import") (part "CAP0603-CAP"))
    )
    (comp (ref "C92")
      (value "22pF")
      (footprint "eagle-import:0603-CAP")
      (libsource (lib "eagle-import") (part "CAP0603-CAP"))
    )
    (comp (ref "C93")
      (value "22pF")
      (footprint "eagle-import:0603-CAP")
      (libsource (lib "eagle-import") (part "CAP0603-CAP"))
    )
    (comp (ref "C94")
      (value "22pF")
      (footprint "eagle-import:0603-CAP")
      (libsource (lib "eagle-import") (part "CAP0603-CAP"))
    )
    (comp (ref "C95")
      (value "22pF")
      (footprint "eagle-import:0603-CAP")
      (libsource (lib "eagle-import") (part "CAP0603-CAP"))
    )
    (comp (ref "C96")
      (value "22pF")
      (footprint "eagle-import:0603-CAP")
      (libsource (lib "eagle-import") (part "CAP0603-CAP"))
    )
    (comp (ref "C97")
      (value "100nF")
      (footprint "eagle-import:0603-CAP")
      (libsource (lib "eagle-import") (part "CAP0603-CAP"))
    )
    (comp (ref "C98")
      (value "22uF")
      (footprint "eagle-import:0603-CAP")
      (libsource (lib "eagle-import") (part "CAP0603-CAP"))
    )
    (comp (ref "C101")
      (value "4.7uF")
      (footprint "eagle-import:0603-CAP")
      (libsource (lib "eagle-import") (part "CAP0603-CAP"))
    )
    (comp (ref "FB4")
      (value "MH2029-300Y")
      (footprint "eagle-import:0805")
      (libsource (lib "eagle-import") (part "FB0805"))
    )
    (comp (ref "FB5")
      (value "MH2029-300Y")
      (footprint "eagle-import:0805")
      (libsource (lib "eagle-import") (part "FB0805"))
    )
    (comp (ref "FB6")
      (value "FB0805")
      (footprint "eagle-import:0805")
      (libsource (lib "eagle-import") (part "FB0805"))
    )
    (comp (ref "FB7")
      (value "FB0805")
      (footprint "eagle-import:0805")
      (libsource (lib "eagle-import") (part "FB0805"))
    )
    (comp (ref "J7")
      (value "CONN_2X5_127")
      (footprint "eagle-import:2X5_127")
      (fields
        (field (name "MANUFACTURER_PART_NUMBER") "20021121-00010C4LF")
        (field (name "COPYRIGHT") "Copyright (C) 2018 Accelerated Designs. All rights reserved")
      )
      (libsource (lib "eagle-import") (part "CONN_2X5_127"))
    )
    (comp (ref "J8")
      (value "USB-C")
      (footprint "eagle-import:CUI_UJ31-CH-G1-SMT-TR")
      (fields (field (name "MF") "CUI Devices") (field (name "MP") "UJ31-CH-G1-SMT-TR"))
      (libsource (lib "eagle-import") (part "USB-C"))
    )
    (comp (ref "R43")
      (value "100K")
      (footprint "eagle-import:0603-RES")
      (libsource (lib "eagle-import") (part "RESISTOR0603-RES"))
    )
    (comp (ref "R44")
      (value "10K")
      (footprint "eagle-import:0603-RES")
      (libsource (lib "eagle-import") (part "RESISTOR0603-RES"))
    )
    (comp (ref "R50")
      (value "100K")
      (footprint "eagle-import:0603-RES")
      (libsource (lib "eagle-import") (part "RESISTOR0603-RES"))
    )
    (comp (ref "R62")
      (value "100K")
      (footprint "eagle-import:0603-RES")
      (libsource (lib "eagle-import") (part "RESISTOR0603-RES"))
    )
    (comp (ref "R63")
      (value "100K")
      (footprint "eagle-import:0603-RES")
      (libsource (lib "eagle-import") (part "RESISTOR0603-RES"))
    )
    (comp (ref "R64")
      (value "100K")
      (footprint "eagle-import:0603-RES")
      (libsource (lib "eagle-import") (part "RESISTOR0603-RES"))
    )
    (comp (ref "R65")
      (value "39R 1%")
      (footprint "eagle-import:0603-RES")
      (libsource (lib "eagle-import") (part "RESISTOR0603-RES"))
    )
    (comp (ref "R66")
      (value "39R 1%")
      (footprint "eagle-import:0603-RES")
      (libsource (lib "eagle-import") (part "RESISTOR0603-RES"))
    )
    (comp (ref "R67")
      (value "6.8K")
      (footprint "eagle-import:0603-RES")
      (libsource (lib "eagle-import") (part "RESISTOR0603-RES"))
    )
    (comp (ref "R68")
      (value "0")
      (footprint "eagle-import:0402-RES")
      (libsource (lib "eagle-import") (part "RESISTOR0402-RES"))
    )
    (comp (ref "R69")
      (value "100K")
      (footprint "eagle-import:0603-RES")
      (libsource (lib "eagle-import") (part "RESISTOR0603-RES"))
    )
    (comp (ref "R70")
      (value "1K")
      (footprint "eagle-import:0603-RES")
      (libsource (lib "eagle-import") (part "RESISTOR0603-RES"))
    )
    (comp (ref "R73")
      (value "5.1K")
      (footprint "eagle-import:0603-RES")
      (libsource (lib "eagle-import") (part "RESISTOR0603-RES"))
    )
    (comp (ref "R74")
      (value "5.1K")
      (footprint "eagle-import:0603-RES")
      (libsource (lib "eagle-import") (part "RESISTOR0603-RES"))
    )
    (comp (ref "R75")
      (value "100K")
      (footprint "eagle-import:0603-RES")
      (libsource (lib "eagle-import") (part "RESISTOR0603-RES"))
    )
    (comp (ref "R76")
      (value "100K")
      (footprint "eagle-import:0603-RES")
      (libsource (lib "eagle-import") (part "RESISTOR0603-RES"))
    )
    (comp (ref "U14")
      (value "ATSAM3X8EA-AU")
      (footprint "eagle-import:LQFP144")
      (libsource (lib "eagle-import") (part "ATSAM3X8EA-AU"))
    )
    (comp (ref "U15")
      (value "PMV48XP")
      (footprint "eagle-import:TO-236_SOT23_NEX")
      (fields
        (field (name "MANUFACTURER_PART_NUMBER") "PMV48XP,215")
        (field (name "COPYRIGHT") "Copyright (C) 2018 Accelerated Designs. All rights reserved")
      )
      (libsource (lib "eagle-import") (part "PMV48XP,215"))
    )
    (comp (ref "U16")
      (value "BC847B-7-F")
      (footprint "eagle-import:TO-236_SOT23_NEX")
      (libsource (lib "eagle-import") (part "BC847B-7-F"))
    )
    (comp (ref "U17")
      (value "LMV358IDGKR")
      (footprint "eagle-import:DGK8")
      (fields (field (name "GENERIC_PART_NUMBER") "LMV358") (field (name "MANUFACTURER") "Texas Instruments"))
      (libsource (lib "eagle-import") (part "LMV358IDGKR"))
    )
    (comp (ref "U18")
      (value "PMV48XP,215")
      (footprint "eagle-import:TO-236_SOT23_NEX")
      (fields (field (name "COPYRIGHT") "Copyright (C) 2018 Accelerated Designs. All rights reserved"))
      (libsource (lib "eagle-import") (part "PMV48XP,215"))
    )
    (comp (ref "U19")
      (value "NCP1117ST33T3G")
      (footprint "eagle-import:SOT223-3_ONS")
      (fields (field (name "COPYRIGHT") "Copyright (C) 2016 Accelerated Designs. All rights reserved"))
      (libsource (lib "eagle-import") (part "NCP1117ST33T3G"))
    )
    (comp (ref "Y1")
      (value "ABM8")
      (footprint "eagle-import:ABM8")
      (libsource (lib "eagle-import") (part "ABM8"))
    )
    (comp (ref "Y2")
      (value "FC-135R")
      (footprint "eagle-import:FC-135")
      (libsource (lib "eagle-import") (part "FC-135R"))
    )
  )
  (nets
    (net (code "1") (name "+3V3") (class "Default")
      (node (ref "R30") (pin "2") (pinfunction "2_2") (pintype "passive"))
      (node (ref "R36") (pin "2") (pinfunction "2_2") (pintype "passive"))
      (node (ref "R37") (pin "2") (pinfunction "2_2") (pintype "passive"))
      (node (ref "R38") (pin "2") (pinfunction "2_2") (pintype "passive"))
      (node (ref "R55") (pin "2") (pinfunction "2_2") (pintype "passive"))
      (node (ref "R58") (pin "2") (pinfunction "2_2") (pintype "passive"))
      (node (ref "TB1") (pin "P17") (pinfunction "+3V3_P17") (pintype "bidirectional"))
      (node (ref "U2") (pin "8") (pinfunction "VCC_8") (pintype "bidirectional"))
    )
    (net (code "2") (name "3V3") (class "Default")
      (node (ref "C72") (pin "1") (pinfunction "1_1") (pintype "passive"))
      (node (ref "C73") (pin "1") (pinfunction "1_1") (pintype "passive"))
      (node (ref "C74") (pin "1") (pinfunction "1_1") (pintype "passive"))
      (node (ref "C75") (pin "1") (pinfunction "1_1") (pintype "passive"))
      (node (ref "C76") (pin "1") (pinfunction "1_1") (pintype "passive"))
      (node (ref "C77") (pin "1") (pinfunction "1_1") (pintype "passive"))
      (node (ref "C78") (pin "1") (pinfunction "1_1") (pintype "passive"))
      (node (ref "C79") (pin "1") (pinfunction "1_1") (pintype "passive"))
      (node (ref "C91") (pin "1") (pinfunction "1_1") (pintype "passive"))
      (node (ref "C98") (pin "1") (pinfunction "1_1") (pintype "passive"))
      (node (ref "FB5") (pin "1") (pinfunction "1_1") (pintype "bidirectional"))
      (node (ref "FB6") (pin "1") (pinfunction "1_1") (pintype "bidirectional"))
      (node (ref "FB7") (pin "1") (pinfunction "1_1") (pintype "bidirectional"))
      (node (ref "J7") (pin "1") (pinfunction "1_1") (pintype "passive"))
      (node (ref "R43") (pin "2") (pinfunction "2_2") (pintype "passive"))
      (node (ref "R44") (pin "2") (pinfunction "2_2") (pintype "passive"))
      (node (ref "R50") (pin "2") (pinfunction "2_2") (pintype "passive"))
      (node (ref "R62") (pin "2") (pinfunction "2_2") (pintype "passive"))
      (node (ref "R63") (pin "2") (pinfunction "2_2") (pintype "passive"))
      (node (ref "R64") (pin "2") (pinfunction "2_2") (pintype "passive"))
      (node (ref "U14") (pin "105") (pinfunction "VDDIO3_105") (pintype "bidirectional"))
      (node (ref "U14") (pin "11") (pinfunction "VDDIO1_11") (pintype "bidirectional"))
      (node (ref "U14") (pin "125") (pinfunction "VDDIO4_125") (pintype "bidirectional"))
      (node (ref "U14") (pin "52") (pinfunction "VDDBU_52") (pintype "bidirectional"))
      (node (ref "U14") (pin "57") (pinfunction "VDDIN_57") (pintype "bidirectional"))
      (node (ref "U14") (pin "62") (pinfunction "VDDIO2_62") (pintype "bidirectional"))
      (node (ref "U15") (pin "2") (pinfunction "S_2") (pintype "passive"))
      (node (ref "U17") (pin "6") (pinfunction "2IN-_6") (pintype "input"))
      (node (ref "U19") (pin "2") (pinfunction "OUT_2") (pintype "output"))
    )
    (net (code "3") (name "3V3_BUS") (class "Default")
      (node (ref "C54") (pin "2") (pinfunction "2_2") (pintype "passive"))
      (node (ref "C55") (pin "1") (pinfunction "1_1") (pintype "passive"))
      (node (ref "C56") (pin "1") (pinfunction "1_1") (pintype "passive"))
      (node (ref "H1") (pin "2.27") (pinfunction "2.27_2.27") (pintype "bidirectional"))
      (node (ref "H1") (pin "2.28") (pinfunction "2.28_2.28") (pintype "bidirectional"))
      (node (ref "L6") (pin "2") (pinfunction "2_2") (pintype "bidirectional"))
      (node (ref "R52") (pin "2") (pinfunction "2_2") (pintype "passive"))
      (node (ref "R53") (pin "2") (pinfunction "2_2") (pintype "passive"))
      (node (ref "U9") (pin "2") (pinfunction "VIN1_2") (pintype "bidirectional"))
      (node (ref "U9") (pin "3") (pinfunction "VINS_3") (pintype "bidirectional"))
      (node (ref "U9") (pin "7") (pinfunction "VIN2_7") (pintype "bidirectional"))
    )
    (net (code "4") (name "5V_BUS") (class "Default")
      (node (ref "C49") (pin "2") (pinfunction "2_2") (pintype "passive"))
      (node (ref "C50") (pin "1") (pinfunction "1_1") (pintype "passive"))
      (node (ref "C51") (pin "1") (pinfunction "1_1") (pintype "passive"))
      (node (ref "C57") (pin "1") (pinfunction "1_1") (pintype "passive"))
      (node (ref "H1") (pin "2.25") (pinfunction "2.25_2.25") (pintype "bidirectional"))
      (node (ref "H1") (pin "2.26") (pinfunction "2.26_2.26") (pintype "bidirectional"))
      (node (ref "L5") (pin "2") (pinfunction "2_2") (pintype "bidirectional"))
      (node (ref "R46") (pin "2") (pinfunction "2_2") (pintype "passive"))
      (node (ref "R47") (pin "2") (pinfunction "2_2") (pintype "passive"))
      (node (ref "R69") (pin "2") (pinfunction "2_2") (pintype "passive"))
      (node (ref "TB1") (pin "P30") (pinfunction "VIN_P30") (pintype "bidirectional"))
      (node (ref "U11") (pin "8") (pinfunction "VDD_8") (pintype "bidirectional"))
      (node (ref "U17") (pin "8") (pinfunction "VCC+_8") (pintype "power_in"))
      (node (ref "U18") (pin "2") (pinfunction "S_2") (pintype "passive"))
      (node (ref "U19") (pin "3") (pinfunction "IN_3") (pintype "input"))
      (node (ref "U6") (pin "2") (pinfunction "VIN1_2") (pintype "bidirectional"))
      (node (ref "U6") (pin "3") (pinfunction "VINS_3") (pintype "bidirectional"))
      (node (ref "U6") (pin "7") (pinfunction "VIN2_7") (pintype "bidirectional"))
      (node (ref "U7") (pin "2") (pinfunction "VIN1_2") (pintype "bidirectional"))
      (node (ref "U7") (pin "3") (pinfunction "VINS_3") (pintype "bidirectional"))
      (node (ref "U7") (pin "7") (pinfunction "VIN2_7") (pintype "bidirectional"))
      (node (ref "U8") (pin "2") (pinfunction "VIN1_2") (pintype "bidirectional"))
      (node (ref "U8") (pin "3") (pinfunction "VINS_3") (pintype "bidirectional"))
      (node (ref "U8") (pin "7") (pinfunction "VIN2_7") (pintype "bidirectional"))
    )
    (net (code "5") (name "5V_USB_CHG") (class "Default")
      (node (ref "D7") (pin "A") (pinfunction "A_A") (pintype "passive"))
      (node (ref "H1") (pin "1.32") (pinfunction "1.32_1.32") (pintype "bidirectional"))
    )
    (net (code "6") (name "BCR_OUT") (class "Default")
      (node (ref "C6") (pin "1") (pinfunction "1_1") (pintype "passive"))
      (node (ref "C7") (pin "1") (pinfunction "1_1") (pintype "passive"))
      (node (ref "H1") (pin "2.41") (pinfunction "2.41_2.41") (pintype "bidirectional"))
      (node (ref "H1") (pin "2.42") (pinfunction "2.42_2.42") (pintype "bidirectional"))
      (node (ref "H1") (pin "2.43") (pinfunction "2.43_2.43") (pintype "bidirectional"))
      (node (ref "H1") (pin "2.44") (pinfunction "2.44_2.44") (pintype "bidirectional"))
      (node (ref "U1") (pin "3") (pinfunction "VH_3") (pintype "passive"))
    )
    (net (code "7") (name "BUS_EN") (class "Default")
      (node (ref "C63") (pin "1") (pinfunction "1_1") (pintype "passive"))
      (node (ref "R61") (pin "2") (pinfunction "2_2") (pintype "passive"))
      (node (ref "U13") (pin "2") (pinfunction "VOUT_2") (pintype "power_in"))
      (node (ref "U13") (pin "3") (pinfunction "VOUT_3") (pintype "power_in"))
      (node (ref "U4") (pin "10") (pinfunction "EN_10") (pintype "bidirectional"))
      (node (ref "U5") (pin "10") (pinfunction "EN_10") (pintype "bidirectional"))
    )
    (net (code "8") (name "CSKB_TO_EPS_RX") (class "Default")
      (node (ref "H1") (pin "1.51") (pinfunction "1.51_1.51") (pintype "bidirectional"))
      (node (ref "TB1") (pin "P2") (pinfunction "RX_P2") (pintype "bidirectional"))
      (node (ref "U14") (pin "27") (pinfunction "PA8_27") (pintype "bidirectional"))
    )
    (net (code "9") (name "EPS_SCL_TO_BUFFER") (class "Default")
      (node (ref "R36") (pin "1") (pinfunction "1_1") (pintype "passive"))
      (node (ref "TB1") (pin "P24") (pinfunction "I2C_SCL_P24") (pintype "bidirectional"))
      (node (ref "U14") (pin "70") (pinfunction "PA18_70") (pintype "bidirectional"))
      (node (ref "U2") (pin "3") (pinfunction "SCL_DEV_3") (pintype "bidirectional"))
    )
    (net (code "10") (name "EPS_SDA_TO_BUFFER") (class "Default")
      (node (ref "R30") (pin "1") (pinfunction "1_1") (pintype "passive"))
      (node (ref "TB1") (pin "P23") (pinfunction "I2C_SDA_P23") (pintype "bidirectional"))
      (node (ref "U14") (pin "9") (pinfunction "PA17_9") (pintype "bidirectional"))
      (node (ref "U2") (pin "6") (pinfunction "SDA_DEV_6") (pintype "bidirectional"))
    )
    (net (code "11") (name "EPS_TO_WDI") (class "Default")
      (node (ref "TB1") (pin "P13") (pinfunction "D10_P13") (pintype "bidirectional"))
      (node (ref "U12") (pin "6") (pinfunction "WDI_6") (pintype "bidirectional"))
      (node (ref "U14") (pin "144") (pinfunction "PB25_144") (pintype "bidirectional"))
    )
    (net (code "12") (name "EPS_TX_TO_CSKB") (class "Default")
      (node (ref "H1") (pin "1.49") (pinfunction "1.49_1.49") (pintype "bidirectional"))
      (node (ref "TB1") (pin "P1") (pinfunction "TX_P1") (pintype "bidirectional"))
      (node (ref "U14") (pin "2") (pinfunction "PA9_2") (pintype "bidirectional"))
    )
    (net (code "13") (name "ERASE_CMD") (class "Default")
      (node (ref "R44") (pin "1") (pinfunction "1_1") (pintype "passive"))
      (node (ref "U15") (pin "1") (pinfunction "G_1") (pintype "passive"))
    )
    (net (code "14") (name "GND") (class "Default")
      (node (ref "C10") (pin "1") (pinfunction "1_1") (pintype "passive"))
      (node (ref "C101") (pin "2") (pinfunction "2_2") (pintype "passive"))
      (node (ref "C33") (pin "2") (pinfunction "2_2") (pintype "passive"))
      (node (ref "C34") (pin "2") (pinfunction "2_2") (pintype "passive"))
      (node (ref "C38") (pin "2") (pinfunction "2_2") (pintype "passive"))
      (node (ref "C39") (pin "2") (pinfunction "2_2") (pintype "passive"))
      (node (ref "C40") (pin "2") (pinfunction "2_2") (pintype "passive"))
      (node (ref "C41") (pin "2") (pinfunction "2_2") (pintype "passive"))
      (node (ref "C42") (pin "2") (pinfunction "2_2") (pintype "passive"))
      (node (ref "C43") (pin "2") (pinfunction "2_2") (pintype "passive"))
      (node (ref "C45") (pin "2") (pinfunction "2_2") (pintype "passive"))
      (node (ref "C46") (pin "2") (pinfunction "2_2") (pintype "passive"))
      (node (ref "C47") (pin "2") (pinfunction "2_2") (pintype "passive"))
      (node (ref "C48") (pin "2") (pinfunction "2_2") (pintype "passive"))
      (node (ref "C50") (pin "2") (pinfunction "2_2") (pintype "passive"))
      (node (ref "C51") (pin "2") (pinfunction "2_2") (pintype "passive"))
      (node (ref "C52") (pin "2") (pinfunction "2_2") (pintype "passive"))
      (node (ref "C53") (pin "2") (pinfunction "2_2") (pintype "passive"))
      (node (ref "C55") (pin "2") (pinfunction "2_2") (pintype "passive"))
      (node (ref "C56") (pin "2") (pinfunction "2_2") (pintype "passive"))
      (node (ref "C57") (pin "2") (pinfunction "2_2") (pintype "passive"))
      (node (ref "C58") (pin "2") (pinfunction "2_2") (pintype "passive"))
      (node (ref "C59") (pin "2") (pinfunction "2_2") (pintype "passive"))
      (node (ref "C6") (pin "2") (pinfunction "2_2") (pintype "passive"))
      (node (ref "C64") (pin "2") (pinfunction "2_2") (pintype "passive"))
      (node (ref "C65") (pin "2") (pinfunction "2_2") (pintype "passive"))
      (node (ref "C66") (pin "2") (pinfunction "2_2") (pintype "passive"))
      (node (ref "C67") (pin "2") (pinfunction "2_2") (pintype "passive"))
      (node (ref "C68") (pin "2") (pinfunction "2_2") (pintype "passive"))
      (node (ref "C69") (pin "2") (pinfunction "2_2") (pintype "passive"))
      (node (ref "C7") (pin "2") (pinfunction "2_2") (pintype "passive"))
      (node (ref "C70") (pin "2") (pinfunction "2_2") (pintype "passive"))
      (node (ref "C71") (pin "2") (pinfunction "2_2") (pintype "passive"))
      (node (ref "C72") (pin "2") (pinfunction "2_2") (pintype "passive"))
      (node (ref "C73") (pin "2") (pinfunction "2_2") (pintype "passive"))
      (node (ref "C74") (pin "2") (pinfunction "2_2") (pintype "passive"))
      (node (ref "C75") (pin "2") (pinfunction "2_2") (pintype "passive"))
      (node (ref "C76") (pin "2") (pinfunction "2_2") (pintype "passive"))
      (node (ref "C77") (pin "2") (pinfunction "2_2") (pintype "passive"))
      (node (ref "C78") (pin "2") (pinfunction "2_2") (pintype "passive"))
      (node (ref "C79") (pin "2") (pinfunction "2_2") (pintype "passive"))
      (node (ref "C8") (pin "1") (pinfunction "1_1") (pintype "passive"))
      (node (ref "C80") (pin "2") (pinfunction "2_2") (pintype "passive"))
      (node (ref "C81") (pin "2") (pinfunction "2_2") (pintype "passive"))
      (node (ref "C82") (pin "2") (pinfunction "2_2") (pintype "passive"))
      (node (ref "C83") (pin "2") (pinfunction "2_2") (pintype "passive"))
      (node (ref "C84") (pin "2") (pinfunction "2_2") (pintype "passive"))
      (node (ref "C85") (pin "2") (pinfunction "2_2") (pintype "passive"))
      (node (ref "C86") (pin "2") (pinfunction "2_2") (pintype "passive"))
      (node (ref "C87") (pin "2") (pinfunction "2_2") (pintype "passive"))
      (node (ref "C88") (pin "2") (pinfunction "2_2") (pintype "passive"))
      (node (ref "C89") (pin "2") (pinfunction "2_2") (pintype "passive"))
      (node (ref "C9") (pin "1") (pinfunction "1_1") (pintype "passive"))
      (node (ref "C90") (pin "2") (pinfunction "2_2") (pintype "passive"))
      (node (ref "C92") (pin "2") (pinfunction "2_2") (pintype "passive"))
      (node (ref "C93") (pin "1") (pinfunction "1_1") (pintype "passive"))
      (node (ref "C94") (pin "2") (pinfunction "2_2") (pintype "passive"))
      (node (ref "C95") (pin "2") (pinfunction "2_2") (pintype "passive"))
      (node (ref "C96") (pin "1") (pinfunction "1_1") (pintype "passive"))
      (node (ref "C97") (pin "2") (pinfunction "2_2") (pintype "passive"))
      (node (ref "C98") (pin "2") (pinfunction "2_2") (pintype "passive"))
      (node (ref "D8") (pin "2") (pinfunction "1_2") (pintype "bidirectional"))
      (node (ref "H1") (pin "2.14") (pinfunction "2.14_2.14") (pintype "bidirectional"))
      (node (ref "H1") (pin "2.17") (pinfunction "2.17_2.17") (pintype "bidirectional"))
      (node (ref "H1") (pin "2.21") (pinfunction "2.21_2.21") (pintype "bidirectional"))
      (node (ref "H1") (pin "2.22") (pinfunction "2.22_2.22") (pintype "bidirectional"))
      (node (ref "H1") (pin "2.29") (pinfunction "2.29_2.29") (pintype "bidirectional"))
      (node (ref "H1") (pin "2.30") (pinfunction "2.30_2.30") (pintype "bidirectional"))
      (node (ref "H1") (pin "2.32") (pinfunction "2.32_2.32") (pintype "bidirectional"))
      (node (ref "H1") (pin "2.47") (pinfunction "2.47_2.47") (pintype "bidirectional"))
      (node (ref "H1") (pin "2.48") (pinfunction "2.48_2.48") (pintype "bidirectional"))
      (node (ref "H1") (pin "2.9") (pinfunction "2.9_2.9") (pintype "bidirectional"))
      (node (ref "J1") (pin "2") (pinfunction "2_2") (pintype "bidirectional"))
      (node (ref "J2") (pin "2") (pinfunction "2_2") (pintype "bidirectional"))
      (node (ref "J3") (pin "2") (pinfunction "2_2") (pintype "bidirectional"))
      (node (ref "J4") (pin "2") (pinfunction "2_2") (pintype "bidirectional"))
      (node (ref "J5") (pin "2") (pinfunction "2_2") (pintype "bidirectional"))
      (node (ref "J6") (pin "2") (pinfunction "2_2") (pintype "bidirectional"))
      (node (ref "J7") (pin "3") (pinfunction "3_3") (pintype "passive"))
      (node (ref "J7") (pin "5") (pinfunction "5_5") (pintype "passive"))
      (node (ref "J7") (pin "9") (pinfunction "9_9") (pintype "passive"))
      (node (ref "J8") (pin "A1") (pinfunction "GND_A1") (pintype "power_in"))
      (node (ref "J8") (pin "A12") (pinfunction "GND_A12") (pintype "power_in"))
      (node (ref "J8") (pin "B1") (pinfunction "GND_B1") (pintype "power_in"))
      (node (ref "J8") (pin "B12") (pinfunction "GND_B12") (pintype "power_in"))
      (node (ref "J8") (pin "SH1") (pinfunction "SHIELD_SH1") (pintype "power_in"))
      (node (ref "J8") (pin "SH2") (pinfunction "SHIELD_SH2") (pintype "power_in"))
      (node (ref "J8") (pin "SH3") (pinfunction "SHIELD_SH3") (pintype "power_in"))
      (node (ref "J8") (pin "SH4") (pinfunction "SHIELD_SH4") (pintype "power_in"))
      (node (ref "J8") (pin "SH5") (pinfunction "SHIELD_SH5") (pintype "power_in"))
      (node (ref "J8") (pin "SH6") (pinfunction "SHIELD_SH6") (pintype "power_in"))
      (node (ref "M1") (pin "1") (pinfunction "G_1") (pintype "bidirectional"))
      (node (ref "NT1") (pin "GND") (pinfunction "GND_GND") (pintype "power_in"))
      (node (ref "NT2") (pin "GND") (pinfunction "GND_GND") (pintype "power_in"))
      (node (ref "NT3") (pin "GND") (pinfunction "GND_GND") (pintype "power_in"))
      (node (ref "R18") (pin "1") (pinfunction "1_1") (pintype "passive"))
      (node (ref "R31") (pin "1") (pinfunction "1_1") (pintype "passive"))
      (node (ref "R32") (pin "1") (pinfunction "1_1") (pintype "passive"))
      (node (ref "R33") (pin "1") (pinfunction "1_1") (pintype "passive"))
      (node (ref "R34") (pin "1") (pinfunction "1_1") (pintype "passive"))
      (node (ref "R39") (pin "1") (pinfunction "1_1") (pintype "passive"))
      (node (ref "R40") (pin "1") (pinfunction "1_1") (pintype "passive"))
      (node (ref "R45") (pin "1") (pinfunction "1_1") (pintype "passive"))
      (node (ref "R48") (pin "1") (pinfunction "1_1") (pintype "passive"))
      (node (ref "R51") (pin "1") (pinfunction "1_1") (pintype "passive"))
      (node (ref "R54") (pin "1") (pinfunction "1_1") (pintype "passive"))
      (node (ref "R56") (pin "1") (pinfunction "1_1") (pintype "passive"))
      (node (ref "R61") (pin "1") (pinfunction "1_1") (pintype "passive"))
      (node (ref "R67") (pin "1") (pinfunction "1_1") (pintype "passive"))
      (node (ref "R68") (pin "1") (pinfunction "1_1") (pintype "passive"))
      (node (ref "R73") (pin "1") (pinfunction "1_1") (pintype "passive"))
      (node (ref "R74") (pin "1") (pinfunction "1_1") (pintype "passive"))
      (node (ref "R75") (pin "1") (pinfunction "1_1") (pintype "passive"))
      (node (ref "R76") (pin "1") (pinfunction "1_1") (pintype "passive"))
      (node (ref "TB1") (pin "P29") (pinfunction "GND_P29") (pintype "bidirectional"))
      (node (ref "TB1") (pin "P4") (pinfunction "GND_P4") (pintype "bidirectional"))
      (node (ref "U1") (pin "22") (pinfunction "OLIM_22") (pintype "passive"))
      (node (ref "U1") (pin "5") (pinfunction "PGND_5") (pintype "passive"))
      (node (ref "U10") (pin "5") (pinfunction "GND_5") (pintype "bidirectional"))
      (node (ref "U11") (pin "7") (pinfunction "GND_7") (pintype "bidirectional"))
      (node (ref "U12") (pin "5") (pinfunction "GND_5") (pintype "bidirectional"))
      (node (ref "U13") (pin "1") (pinfunction "GND_1") (pintype "power_in"))
      (node (ref "U14") (pin "106") (pinfunction "GND3_106") (pintype "bidirectional"))
      (node (ref "U14") (pin "12") (pinfunction "GND1_12") (pintype "bidirectional"))
      (node (ref "U14") (pin "126") (pinfunction "GND4_126") (pintype "bidirectional"))
      (node (ref "U14") (pin "33") (pinfunction "GNDPLL_33") (pintype "bidirectional"))
      (node (ref "U14") (pin "44") (pinfunction "GNDUTMI_44") (pintype "bidirectional"))
      (node (ref "U14") (pin "46") (pinfunction "JTAGSEL_46") (pintype "bidirectional"))
      (node (ref "U14") (pin "54") (pinfunction "GNDBU_54") (pintype "bidirectional"))
      (node (ref "U14") (pin "58") (pinfunction "GND2_58") (pintype "bidirectional"))
      (node (ref "U14") (pin "74") (pinfunction "GNDANA_74") (pintype "bidirectional"))
      (node (ref "U16") (pin "2") (pinfunction "E_2") (pintype "passive"))
      (node (ref "U17") (pin "4") (pinfunction "GND_4") (pintype "power_in"))
      (node (ref "U19") (pin "1") (pinfunction "GND_1") (pintype "bidirectional"))
      (node (ref "U2") (pin "4") (pinfunction "GND_4") (pintype "bidirectional"))
      (node (ref "U3") (pin "11") (pinfunction "GND_11") (pintype "bidirectional"))
      (node (ref "U3") (pin "5") (pinfunction "SYNC_5") (pintype "bidirectional"))
      (node (ref "U4") (pin "11") (pinfunction "GND_11") (pintype "bidirectional"))
      (node (ref "U4") (pin "5") (pinfunction "SYNC_5") (pintype "bidirectional"))
      (node (ref "U5") (pin "11") (pinfunction "GND_11") (pintype "bidirectional"))
      (node (ref "U5") (pin "5") (pinfunction "SYNC_5") (pintype "bidirectional"))
      (node (ref "U6") (pin "5") (pinfunction "GND_5") (pintype "bidirectional"))
      (node (ref "U7") (pin "5") (pinfunction "GND_5") (pintype "bidirectional"))
      (node (ref "U8") (pin "5") (pinfunction "GND_5") (pintype "bidirectional"))
      (node (ref "U9") (pin "5") (pinfunction "GND_5") (pintype "bidirectional"))
      (node (ref "Y1") (pin "2") (pinfunction "2_2") (pintype "bidirectional"))
      (node (ref "Y1") (pin "4") (pinfunction "4_4") (pintype "bidirectional"))
    )
    (net (code "15") (name "GNDA") (class "Default")
      (node (ref "C1") (pin "1") (pinfunction "1_1") (pintype "passive"))
      (node (ref "C2") (pin "1") (pinfunction "1_1") (pintype "passive"))
      (node (ref "C3") (pin "2") (pinfunction "2_2") (pintype "passive"))
      (node (ref "C4") (pin "2") (pinfunction "2_2") (pintype "passive"))
      (node (ref "NT2") (pin "GNDA") (pinfunction "GNDA_GNDA") (pintype "power_in"))
      (node (ref "NT3") (pin "GNDA") (pinfunction "GNDA_GNDA") (pintype "power_in"))
      (node (ref "R10") (pin "2") (pinfunction "2_2") (pintype "passive"))
      (node (ref "R15") (pin "2") (pinfunction "2_2") (pintype "passive"))
      (node (ref "R2") (pin "2") (pinfunction "2_2") (pintype "passive"))
      (node (ref "R3") (pin "2") (pinfunction "2_2") (pintype "passive"))
      (node (ref "R4") (pin "2") (pinfunction "2_2") (pintype "passive"))
      (node (ref "U1") (pin "10") (pinfunction "AGND_10") (pintype "passive"))
      (node (ref "U1") (pin "13") (pinfunction "LED1_13") (pintype "bidirectional"))
      (node (ref "U1") (pin "14") (pinfunction "LED2_14") (pintype "bidirectional"))
      (node (ref "U1") (pin "15") (pinfunction "LED3_15") (pintype "bidirectional"))
      (node (ref "U1") (pin "16") (pinfunction "LED4_16") (pintype "bidirectional"))
      (node (ref "U1") (pin "8") (pinfunction "MODE_8") (pintype "passive"))
    )
    (net (code "16") (name "I2C_EN") (class "Default")
      (node (ref "TB1") (pin "P5") (pinfunction "D2_P5") (pintype "bidirectional"))
      (node (ref "U14") (pin "139") (pinfunction "PC28_139") (pintype "bidirectional"))
      (node (ref "U2") (pin "1") (pinfunction "EN_1") (pintype "bidirectional"))
    )
    (net (code "17") (name "I2C_SCL") (class "Default")
      (node (ref "H1") (pin "1.43") (pinfunction "1.43_1.43") (pintype "bidirectional"))
      (node (ref "U2") (pin "2") (pinfunction "SCL_BUS_2") (pintype "bidirectional"))
    )
    (net (code "18") (name "I2C_SDA") (class "Default")
      (node (ref "H1") (pin "1.41") (pinfunction "1.41_1.41") (pintype "bidirectional"))
      (node (ref "U2") (pin "7") (pinfunction "SDA_BUS_7") (pintype "bidirectional"))
    )
    (net (code "19") (name "JTAG_TCK") (class "Default")
      (node (ref "J7") (pin "4") (pinfunction "4_4") (pintype "passive"))
      (node (ref "R62") (pin "1") (pinfunction "1_1") (pintype "passive"))
      (node (ref "U14") (pin "28") (pinfunction "PB28_28") (pintype "bidirectional"))
    )
    (net (code "20") (name "JTAG_TDI") (class "Default")
      (node (ref "J7") (pin "8") (pinfunction "8_8") (pintype "passive"))
      (node (ref "R63") (pin "1") (pinfunction "1_1") (pintype "passive"))
      (node (ref "U14") (pin "29") (pinfunction "PB29_29") (pintype "bidirectional"))
    )
    (net (code "21") (name "JTAG_TDO") (class "Default")
      (node (ref "J7") (pin "6") (pinfunction "6_6") (pintype "passive"))
      (node (ref "U14") (pin "30") (pinfunction "PB30_30") (pintype "bidirectional"))
    )
    (net (code "22") (name "JTAG_TMS") (class "Default")
      (node (ref "J7") (pin "2") (pinfunction "2_2") (pintype "passive"))
      (node (ref "R50") (pin "1") (pinfunction "1_1") (pintype "passive"))
      (node (ref "U14") (pin "31") (pinfunction "PB31_31") (pintype "bidirectional"))
    )
    (net (code "23") (name "MID") (class "Default")
      (node (ref "M1") (pin "2") (pinfunction "S_2") (pintype "bidirectional"))
      (node (ref "NT1") (pin "GNDA") (pinfunction "GNDA_GNDA") (pintype "power_in"))
      (node (ref "R17") (pin "1") (pinfunction "1_1") (pintype "passive"))
      (node (ref "U1") (pin "12") (pinfunction "MID_12") (pintype "passive"))
    )
    (net (code "24") (name "Net-(C1-Pad2)") (class "Default")
      (node (ref "C1") (pin "2") (pinfunction "2_2") (pintype "passive"))
      (node (ref "R1") (pin "2") (pinfunction "2_2") (pintype "passive"))
    )
    (net (code "25") (name "Net-(C2-Pad2)") (class "Default")
      (node (ref "C2") (pin "2") (pinfunction "2_2") (pintype "passive"))
      (node (ref "R5") (pin "2") (pinfunction "2_2") (pintype "passive"))
    )
    (net (code "26") (name "Net-(C38-Pad1)") (class "Default")
      (node (ref "C38") (pin "1") (pinfunction "1_1") (pintype "passive"))
      (node (ref "FB3") (pin "2") (pinfunction "2_2") (pintype "bidirectional"))
      (node (ref "R99") (pin "1") (pinfunction "1_1") (pintype "passive"))
    )
    (net (code "27") (name "Net-(D1-PadA)") (class "Default")
      (node (ref "D1") (pin "A") (pinfunction "A_A") (pintype "passive"))
      (node (ref "J1") (pin "1") (pinfunction "1_1") (pintype "bidirectional"))
    )
    (net (code "28") (name "Net-(D2-PadA)") (class "Default")
      (node (ref "D2") (pin "A") (pinfunction "A_A") (pintype "passive"))
      (node (ref "J2") (pin "1") (pinfunction "1_1") (pintype "bidirectional"))
    )
    (net (code "29") (name "Net-(D3-PadA)") (class "Default")
      (node (ref "D3") (pin "A") (pinfunction "A_A") (pintype "passive"))
      (node (ref "J3") (pin "1") (pinfunction "1_1") (pintype "bidirectional"))
    )
    (net (code "30") (name "Net-(D4-PadA)") (class "Default")
      (node (ref "D4") (pin "A") (pinfunction "A_A") (pintype "passive"))
      (node (ref "J4") (pin "1") (pinfunction "1_1") (pintype "bidirectional"))
    )
    (net (code "31") (name "Net-(D5-PadA)") (class "Default")
      (node (ref "D5") (pin "A") (pinfunction "A_A") (pintype "passive"))
      (node (ref "J5") (pin "1") (pinfunction "1_1") (pintype "bidirectional"))
    )
    (net (code "32") (name "Net-(D6-PadA)") (class "Default")
      (node (ref "D6") (pin "A") (pinfunction "A_A") (pintype "passive"))
      (node (ref "J6") (pin "1") (pinfunction "1_1") (pintype "bidirectional"))
    )
    (net (code "33") (name "Net-(D8-2)") (class "Default")
      (node (ref "D8") (pin "1") (pinfunction "2_1") (pintype "bidirectional"))
      (node (ref "L1") (pin "1") (pinfunction "1_1") (pintype "bidirectional"))
      (node (ref "U1") (pin "2") (pinfunction "LX_2") (pintype "passive"))
    )
    (net (code "34") (name "Net-(H1-PadP1)") (class "Default")
      (node (ref "H1") (pin "P1") (pinfunction "P1_P1") (pintype "bidirectional"))
      (node (ref "R31") (pin "2") (pinfunction "2_2") (pintype "passive"))
    )
    (net (code "35") (name "Net-(H1-PadP2)") (class "Default")
      (node (ref "H1") (pin "P2") (pinfunction "P2_P2") (pintype "bidirectional"))
      (node (ref "R32") (pin "2") (pinfunction "2_2") (pintype "passive"))
    )
    (net (code "36") (name "Net-(H1-PadP3)") (class "Default")
      (node (ref "H1") (pin "P3") (pinfunction "P3_P3") (pintype "bidirectional"))
      (node (ref "R33") (pin "2") (pinfunction "2_2") (pintype "passive"))
    )
    (net (code "37") (name "Net-(H1-PadP4)") (class "Default")
      (node (ref "H1") (pin "P4") (pinfunction "P4_P4") (pintype "bidirectional"))
      (node (ref "R34") (pin "2") (pinfunction "2_2") (pintype "passive"))
    )
    (net (code "38") (name "Net-(J8-CC1)") (class "Default")
      (node (ref "J8") (pin "A5") (pinfunction "CC1_A5") (pintype "bidirectional"))
      (node (ref "R74") (pin "2") (pinfunction "2_2") (pintype "passive"))
    )
    (net (code "39") (name "Net-(J8-CC2)") (class "Default")
      (node (ref "J8") (pin "B5") (pinfunction "CC2_B5") (pintype "bidirectional"))
      (node (ref "R73") (pin "2") (pinfunction "2_2") (pintype "passive"))
    )
    (net (code "40") (name "Net-(LED5-Pad1)") (class "Default")
      (node (ref "LED5") (pin "1") (pinfunction "1_1") (pintype "bidirectional"))
      (node (ref "R8") (pin "1") (pinfunction "1_1") (pintype "passive"))
    )
    (net (code "41") (name "Net-(LED6-Pad1)") (class "Default")
      (node (ref "LED6") (pin "1") (pinfunction "1_1") (pintype "bidirectional"))
      (node (ref "R7") (pin "1") (pinfunction "1_1") (pintype "passive"))
    )
    (net (code "42") (name "Net-(M1-D)") (class "Default")
      (node (ref "M1") (pin "3") (pinfunction "D_3") (pintype "bidirectional"))
      (node (ref "R17") (pin "2") (pinfunction "2_2") (pintype "passive"))
      (node (ref "R18") (pin "2") (pinfunction "2_2") (pintype "passive"))
    )
    (net (code "43") (name "Net-(U1-BST)") (class "Default")
      (node (ref "C5") (pin "2") (pinfunction "2_2") (pintype "passive"))
      (node (ref "U1") (pin "6") (pinfunction "BST_6") (pintype "passive"))
    )
    (net (code "44") (name "Net-(U1-FB)") (class "Default")
      (node (ref "R15") (pin "1") (pinfunction "1_1") (pintype "passive"))
      (node (ref "R16") (pin "1") (pinfunction "1_1") (pintype "passive"))
      (node (ref "U1") (pin "17") (pinfunction "FB_17") (pintype "passive"))
    )
    (net (code "45") (name "Net-(U1-IB)") (class "Default")
      (node (ref "R1") (pin "1") (pinfunction "1_1") (pintype "passive"))
      (node (ref "R2") (pin "1") (pinfunction "1_1") (pintype "passive"))
      (node (ref "U1") (pin "21") (pinfunction "IB_21") (pintype "passive"))
    )
    (net (code "46") (name "Net-(U1-ILIM)") (class "Default")
      (node (ref "R4") (pin "1") (pinfunction "1_1") (pintype "passive"))
      (node (ref "U1") (pin "24") (pinfunction "ILIM_24") (pintype "passive"))
    )
    (net (code "47") (name "Net-(U1-ISET)") (class "Default")
      (node (ref "R3") (pin "1") (pinfunction "1_1") (pintype "passive"))
      (node (ref "U1") (pin "23") (pinfunction "ISET_23") (pintype "passive"))
    )
    (net (code "48") (name "Net-(U1-NTC)") (class "Default")
      (node (ref "R5") (pin "1") (pinfunction "1_1") (pintype "passive"))
      (node (ref "R6") (pin "2") (pinfunction "2_2") (pintype "passive"))
      (node (ref "U1") (pin "20") (pinfunction "NTC_20") (pintype "passive"))
    )
    (net (code "49") (name "Net-(U1-SW)") (class "Default")
      (node (ref "C5") (pin "1") (pinfunction "1_1") (pintype "passive"))
      (node (ref "L1") (pin "2") (pinfunction "2_2") (pintype "bidirectional"))
      (node (ref "U1") (pin "4") (pinfunction "SW_4") (pintype "passive"))
    )
    (net (code "50") (name "Net-(U1-TMR)") (class "Default")
      (node (ref "C4") (pin "1") (pinfunction "1_1") (pintype "passive"))
      (node (ref "U1") (pin "11") (pinfunction "TMR_11") (pintype "passive"))
    )
    (net (code "51") (name "Net-(U1-VNTC)") (class "Default")
      (node (ref "R6") (pin "1") (pinfunction "1_1") (pintype "passive"))
      (node (ref "U1") (pin "19") (pinfunction "VNTC_19") (pintype "passive"))
    )
    (net (code "52") (name "Net-(U1-~{ACOK})") (class "Default")
      (node (ref "LED6") (pin "2") (pinfunction "2_2") (pintype "bidirectional"))
      (node (ref "U1") (pin "25") (pinfunction "~{ACOK}_25") (pintype "passive"))
    )
    (net (code "53") (name "Net-(U1-~{CHG})") (class "Default")
      (node (ref "LED5") (pin "2") (pinfunction "2_2") (pintype "bidirectional"))
      (node (ref "U1") (pin "26") (pinfunction "~{CHG}_26") (pintype "passive"))
    )
    (net (code "54") (name "Net-(U3-BST)") (class "Default")
      (node (ref "C60") (pin "1") (pinfunction "1_1") (pintype "passive"))
      (node (ref "U3") (pin "1") (pinfunction "BST_1") (pintype "bidirectional"))
    )
    (net (code "55") (name "Net-(U3-FB)") (class "Default")
      (node (ref "C44") (pin "1") (pinfunction "1_1") (pintype "passive"))
      (node (ref "R40") (pin "2") (pinfunction "2_2") (pintype "passive"))
      (node (ref "R41") (pin "1") (pinfunction "1_1") (pintype "passive"))
      (node (ref "U3") (pin "6") (pinfunction "FB_6") (pintype "bidirectional"))
    )
    (net (code "56") (name "Net-(U3-INTVCC)") (class "Default")
      (node (ref "C42") (pin "1") (pinfunction "1_1") (pintype "passive"))
      (node (ref "U3") (pin "3") (pinfunction "INTVCC_3") (pintype "bidirectional"))
    )
    (net (code "57") (name "Net-(U3-PG)") (class "Default")
      (node (ref "R42") (pin "1") (pinfunction "1_1") (pintype "passive"))
      (node (ref "U3") (pin "8") (pinfunction "PG_8") (pintype "bidirectional"))
    )
    (net (code "58") (name "Net-(U3-RT)") (class "Default")
      (node (ref "R39") (pin "2") (pinfunction "2_2") (pintype "passive"))
      (node (ref "U3") (pin "4") (pinfunction "RT_4") (pintype "bidirectional"))
    )
    (net (code "59") (name "Net-(U3-SW)") (class "Default")
      (node (ref "C60") (pin "2") (pinfunction "2_2") (pintype "passive"))
      (node (ref "L4") (pin "1") (pinfunction "1_1") (pintype "bidirectional"))
      (node (ref "U3") (pin "2") (pinfunction "SW_2") (pintype "bidirectional"))
    )
    (net (code "60") (name "Net-(U3-TRSS)") (class "Default")
      (node (ref "C43") (pin "1") (pinfunction "1_1") (pintype "passive"))
      (node (ref "U3") (pin "7") (pinfunction "TRSS_7") (pintype "bidirectional"))
    )
    (net (code "61") (name "Net-(U4-BST)") (class "Default")
      (node (ref "C61") (pin "1") (pinfunction "1_1") (pintype "passive"))
      (node (ref "U4") (pin "1") (pinfunction "BST_1") (pintype "bidirectional"))
    )
    (net (code "62") (name "Net-(U4-FB)") (class "Default")
      (node (ref "C49") (pin "1") (pinfunction "1_1") (pintype "passive"))
      (node (ref "R47") (pin "1") (pinfunction "1_1") (pintype "passive"))
      (node (ref "R48") (pin "2") (pinfunction "2_2") (pintype "passive"))
      (node (ref "U4") (pin "6") (pinfunction "FB_6") (pintype "bidirectional"))
    )
    (net (code "63") (name "Net-(U4-INTVCC)") (class "Default")
      (node (ref "C48") (pin "1") (pinfunction "1_1") (pintype "passive"))
      (node (ref "U4") (pin "3") (pinfunction "INTVCC_3") (pintype "bidirectional"))
    )
    (net (code "64") (name "Net-(U4-PG)") (class "Default")
      (node (ref "R46") (pin "1") (pinfunction "1_1") (pintype "passive"))
      (node (ref "U4") (pin "8") (pinfunction "PG_8") (pintype "bidirectional"))
    )
    (net (code "65") (name "Net-(U4-RT)") (class "Default")
      (node (ref "R45") (pin "2") (pinfunction "2_2") (pintype "passive"))
      (node (ref "U4") (pin "4") (pinfunction "RT_4") (pintype "bidirectional"))
    )
    (net (code "66") (name "Net-(U4-SW)") (class "Default")
      (node (ref "C61") (pin "2") (pinfunction "2_2") (pintype "passive"))
      (node (ref "L5") (pin "1") (pinfunction "1_1") (pintype "bidirectional"))
      (node (ref "U4") (pin "2") (pinfunction "SW_2") (pintype "bidirectional"))
    )
    (net (code "67") (name "Net-(U4-TRSS)") (class "Default")
      (node (ref "C47") (pin "1") (pinfunction "1_1") (pintype "passive"))
      (node (ref "U4") (pin "7") (pinfunction "TRSS_7") (pintype "bidirectional"))
    )
    (net (code "68") (name "Net-(U5-BST)") (class "Default")
      (node (ref "C62") (pin "1") (pinfunction "1_1") (pintype "passive"))
      (node (ref "U5") (pin "1") (pinfunction "BST_1") (pintype "bidirectional"))
    )
    (net (code "69") (name "Net-(U5-FB)") (class "Default")
      (node (ref "C54") (pin "1") (pinfunction "1_1") (pintype "passive"))
      (node (ref "R53") (pin "1") (pinfunction "1_1") (pintype "passive"))
      (node (ref "R54") (pin "2") (pinfunction "2_2") (pintype "passive"))
      (node (ref "U5") (pin "6") (pinfunction "FB_6") (pintype "bidirectional"))
    )
    (net (code "70") (name "Net-(U5-INTVCC)") (class "Default")
      (node (ref "C53") (pin "1") (pinfunction "1_1") (pintype "passive"))
      (node (ref "U5") (pin "3") (pinfunction "INTVCC_3") (pintype "bidirectional"))
    )
    (net (code "71") (name "Net-(U5-PG)") (class "Default")
      (node (ref "R52") (pin "1") (pinfunction "1_1") (pintype "passive"))
      (node (ref "U5") (pin "8") (pinfunction "PG_8") (pintype "bidirectional"))
    )
    (net (code "72") (name "Net-(U5-RT)") (class "Default")
      (node (ref "R51") (pin "2") (pinfunction "2_2") (pintype "passive"))
      (node (ref "U5") (pin "4") (pinfunction "RT_4") (pintype "bidirectional"))
    )
    (net (code "73") (name "Net-(U5-SW)") (class "Default")
      (node (ref "C62") (pin "2") (pinfunction "2_2") (pintype "passive"))
      (node (ref "L6") (pin "1") (pinfunction "1_1") (pintype "bidirectional"))
      (node (ref "U5") (pin "2") (pinfunction "SW_2") (pintype "bidirectional"))
    )
    (net (code "74") (name "Net-(U5-TRSS)") (class "Default")
      (node (ref "C52") (pin "1") (pinfunction "1_1") (pintype "passive"))
      (node (ref "U5") (pin "7") (pinfunction "TRSS_7") (pintype "bidirectional"))
    )
    (net (code "75") (name "Net-(U11-CT)") (class "Default")
      (node (ref "R37") (pin "1") (pinfunction "1_1") (pintype "passive"))
      (node (ref "U11") (pin "6") (pinfunction "CT_6") (pintype "bidirectional"))
    )
    (net (code "76") (name "Net-(U11-INT)") (class "Default")
      (node (ref "R38") (pin "1") (pinfunction "1_1") (pintype "passive"))
      (node (ref "U11") (pin "5") (pinfunction "INT_5") (pintype "bidirectional"))
    )
    (net (code "77") (name "Net-(U12-ENABLE)") (class "Default")
      (node (ref "R57") (pin "1") (pinfunction "1_1") (pintype "passive"))
      (node (ref "U12") (pin "8") (pinfunction "ENABLE_8") (pintype "bidirectional"))
    )
    (net (code "78") (name "Net-(U12-RESETIN)") (class "Default")
      (node (ref "R55") (pin "1") (pinfunction "1_1") (pintype "passive"))
      (node (ref "R56") (pin "2") (pinfunction "2_2") (pintype "passive"))
      (node (ref "U12") (pin "2") (pinfunction "RESETIN_2") (pintype "bidirectional"))
    )
    (net (code "79") (name "Net-(U12-SRT)") (class "Default")
      (node (ref "C58") (pin "1") (pinfunction "1_1") (pintype "passive"))
      (node (ref "U12") (pin "3") (pinfunction "SRT_3") (pintype "bidirectional"))
    )
    (net (code "80") (name "Net-(U12-SWT)") (class "Default")
      (node (ref "C59") (pin "1") (pinfunction "1_1") (pintype "passive"))
      (node (ref "U12") (pin "4") (pinfunction "SWT_4") (pintype "bidirectional"))
    )
    (net (code "81") (name "Net-(U13-R1_C1)") (class "Default")
      (node (ref "C63") (pin "2") (pinfunction "2_2") (pintype "passive"))
      (node (ref "R59") (pin "1") (pinfunction "1_1") (pintype "passive"))
      (node (ref "U13") (pin "6") (pinfunction "R1_C1_6") (pintype "input"))
    )
    (net (code "82") (name "Net-(U13-VIN)") (class "Default")
      (node (ref "R59") (pin "2") (pinfunction "2_2") (pintype "passive"))
      (node (ref "R60") (pin "2") (pinfunction "2_2") (pintype "passive"))
      (node (ref "U13") (pin "4") (pinfunction "VIN_4") (pintype "power_in"))
    )
    (net (code "83") (name "Net-(U14-ADVREF)") (class "Default")
      (node (ref "C64") (pin "1") (pinfunction "1_1") (pintype "passive"))
      (node (ref "FB5") (pin "2") (pinfunction "2_2") (pintype "bidirectional"))
      (node (ref "U14") (pin "75") (pinfunction "ADVREF_75") (pintype "bidirectional"))
    )
    (net (code "84") (name "Net-(U14-DFSDM)") (class "Default")
      (node (ref "R65") (pin "2") (pinfunction "2_2") (pintype "passive"))
      (node (ref "U14") (pin "43") (pinfunction "DFSDM_43") (pintype "bidirectional"))
    )
    (net (code "85") (name "Net-(U14-DFSDP)") (class "Default")
      (node (ref "R66") (pin "2") (pinfunction "2_2") (pintype "passive"))
      (node (ref "U14") (pin "42") (pinfunction "DFSDP_42") (pintype "bidirectional"))
    )
    (net (code "86") (name "Net-(U14-FWUP)") (class "Default")
      (node (ref "R43") (pin "1") (pinfunction "1_1") (pintype "passive"))
      (node (ref "U14") (pin "53") (pinfunction "FWUP_53") (pintype "bidirectional"))
    )
    (net (code "87") (name "Net-(U14-PC0)") (class "Default")
      (node (ref "U14") (pin "130") (pinfunction "PC0_130") (pintype "bidirectional"))
      (node (ref "U15") (pin "3") (pinfunction "D_3") (pintype "passive"))
    )
    (net (code "88") (name "Net-(U14-TST)") (class "Default")
      (node (ref "R68") (pin "2") (pinfunction "2_2") (pintype "passive"))
      (node (ref "U14") (pin "51") (pinfunction "TST_51") (pintype "bidirectional"))
    )
    (net (code "89") (name "Net-(U14-VBG)") (class "Default")
      (node (ref "C92") (pin "1") (pinfunction "1_1") (pintype "passive"))
      (node (ref "R67") (pin "2") (pinfunction "2_2") (pintype "passive"))
      (node (ref "U14") (pin "40") (pinfunction "VBG_40") (pintype "bidirectional"))
    )
    (net (code "90") (name "Net-(U14-VDDCORE1)") (class "Default")
      (node (ref "C84") (pin "1") (pinfunction "1_1") (pintype "passive"))
      (node (ref "C85") (pin "1") (pinfunction "1_1") (pintype "passive"))
      (node (ref "C86") (pin "1") (pinfunction "1_1") (pintype "passive"))
      (node (ref "C87") (pin "1") (pinfunction "1_1") (pintype "passive"))
      (node (ref "C88") (pin "1") (pinfunction "1_1") (pintype "passive"))
      (node (ref "C89") (pin "1") (pinfunction "1_1") (pintype "passive"))
      (node (ref "C90") (pin "1") (pinfunction "1_1") (pintype "passive"))
      (node (ref "FB4") (pin "1") (pinfunction "1_1") (pintype "bidirectional"))
      (node (ref "U14") (pin "10") (pinfunction "VDDCORE1_10") (pintype "bidirectional"))
      (node (ref "U14") (pin "104") (pinfunction "VDDCORE4_104") (pintype "bidirectional"))
      (node (ref "U14") (pin "124") (pinfunction "VDDCORE5_124") (pintype "bidirectional"))
      (node (ref "U14") (pin "45") (pinfunction "VDDCORE2_45") (pintype "bidirectional"))
      (node (ref "U14") (pin "56") (pinfunction "VDDOUT_56") (pintype "bidirectional"))
      (node (ref "U14") (pin "61") (pinfunction "VDDCORE3_61") (pintype "bidirectional"))
    )
    (net (code "91") (name "Net-(U14-VDDPL)") (class "Default")
      (node (ref "C70") (pin "1") (pinfunction "1_1") (pintype "passive"))
      (node (ref "C71") (pin "1") (pinfunction "1_1") (pintype "passive"))
      (node (ref "FB4") (pin "2") (pinfunction "2_2") (pintype "bidirectional"))
      (node (ref "U14") (pin "34") (pinfunction "VDDPL_34") (pintype "bidirectional"))
    )
    (net (code "92") (name "Net-(U14-XIN)") (class "Default")
      (node (ref "C93") (pin "2") (pinfunction "2_2") (pintype "passive"))
      (node (ref "U14") (pin "36") (pinfunction "XIN_36") (pintype "bidirectional"))
      (node (ref "Y1") (pin "3") (pinfunction "3_3") (pintype "bidirectional"))
    )
    (net (code "93") (name "Net-(U14-XIN32)") (class "Default")
      (node (ref "C96") (pin "2") (pinfunction "2_2") (pintype "passive"))
      (node (ref "U14") (pin "48") (pinfunction "XIN32_48") (pintype "bidirectional"))
      (node (ref "Y2") (pin "2") (pinfunction "2_2") (pintype "bidirectional"))
    )
    (net (code "94") (name "Net-(U14-XOUT)") (class "Default")
      (node (ref "C94") (pin "1") (pinfunction "1_1") (pintype "passive"))
      (node (ref "U14") (pin "35") (pinfunction "XOUT_35") (pintype "bidirectional"))
      (node (ref "Y1") (pin "1") (pinfunction "1_1") (pintype "bidirectional"))
    )
    (net (code "95") (name "Net-(U14-XOUT32)") (class "Default")
      (node (ref "C95") (pin "1") (pinfunction "1_1") (pintype "passive"))
      (node (ref "U14") (pin "49") (pinfunction "XOUT32_49") (pintype "bidirectional"))
      (node (ref "Y2") (pin "1") (pinfunction "1_1") (pintype "bidirectional"))
    )
    (net (code "96") (name "Net-(U16-B)") (class "Default")
      (node (ref "R70") (pin "2") (pinfunction "2_2") (pintype "passive"))
      (node (ref "R75") (pin "2") (pinfunction "2_2") (pintype "passive"))
      (node (ref "U16") (pin "1") (pinfunction "B_1") (pintype "passive"))
    )
    (net (code "97") (name "Net-(U16-C)") (class "Default")
      (node (ref "C97") (pin "1") (pinfunction "1_1") (pintype "passive"))
      (node (ref "R69") (pin "1") (pinfunction "1_1") (pintype "passive"))
      (node (ref "R76") (pin "2") (pinfunction "2_2") (pintype "passive"))
      (node (ref "U16") (pin "3") (pinfunction "C_3") (pintype "passive"))
      (node (ref "U17") (pin "5") (pinfunction "2IN+_5") (pintype "input"))
    )
    (net (code "98") (name "Net-(U17-2OUT)") (class "Default")
      (node (ref "U17") (pin "7") (pinfunction "2OUT_7") (pintype "output"))
      (node (ref "U18") (pin "1") (pinfunction "G_1") (pintype "passive"))
    )
    (net (code "99") (name "PCM_IN") (class "Default")
      (node (ref "C39") (pin "1") (pinfunction "1_1") (pintype "passive"))
      (node (ref "C40") (pin "1") (pinfunction "1_1") (pintype "passive"))
      (node (ref "C41") (pin "1") (pinfunction "1_1") (pintype "passive"))
      (node (ref "FB3") (pin "1") (pinfunction "1_1") (pintype "bidirectional"))
      (node (ref "H1") (pin "2.35") (pinfunction "2.35_2.35") (pintype "bidirectional"))
      (node (ref "H1") (pin "2.36") (pinfunction "2.36_2.36") (pintype "bidirectional"))
    )
    (net (code "100") (name "PCM_IN_FILTERED") (class "Default")
      (node (ref "C33") (pin "1") (pinfunction "1_1") (pintype "passive"))
      (node (ref "C34") (pin "1") (pinfunction "1_1") (pintype "passive"))
      (node (ref "R57") (pin "2") (pinfunction "2_2") (pintype "passive"))
      (node (ref "R60") (pin "1") (pinfunction "1_1") (pintype "passive"))
      (node (ref "R99") (pin "2") (pinfunction "2_2") (pintype "passive"))
      (node (ref "U10") (pin "2") (pinfunction "VIN1_2") (pintype "bidirectional"))
      (node (ref "U10") (pin "3") (pinfunction "VINS_3") (pintype "bidirectional"))
      (node (ref "U10") (pin "7") (pinfunction "VIN2_7") (pintype "bidirectional"))
      (node (ref "U12") (pin "1") (pinfunction "IN_1") (pintype "bidirectional"))
      (node (ref "U3") (pin "9") (pinfunction "VIN_9") (pintype "bidirectional"))
      (node (ref "U4") (pin "9") (pinfunction "VIN_9") (pintype "bidirectional"))
      (node (ref "U5") (pin "9") (pinfunction "VIN_9") (pintype "bidirectional"))
    )
    (net (code "101") (name "RESET_EPS") (class "Default")
      (node (ref "C91") (pin "2") (pinfunction "2_2") (pintype "passive"))
      (node (ref "H1") (pin "1.52") (pinfunction "1.52_1.52") (pintype "bidirectional"))
      (node (ref "J7") (pin "10") (pinfunction "10_10") (pintype "passive"))
      (node (ref "R58") (pin "1") (pinfunction "1_1") (pintype "passive"))
      (node (ref "R64") (pin "1") (pinfunction "1_1") (pintype "passive"))
      (node (ref "TB1") (pin "P28") (pinfunction "RESET_P28") (pintype "bidirectional"))
      (node (ref "TB1") (pin "P3") (pinfunction "RESET_P3") (pintype "bidirectional"))
      (node (ref "U12") (pin "7") (pinfunction "RESET_7") (pintype "bidirectional"))
      (node (ref "U13") (pin "5") (pinfunction "ON_OFF_5") (pintype "input"))
      (node (ref "U14") (pin "47") (pinfunction "NRSTB_47") (pintype "bidirectional"))
    )
    (net (code "102") (name "SW1") (class "Default")
      (node (ref "C44") (pin "2") (pinfunction "2_2") (pintype "passive"))
      (node (ref "C45") (pin "1") (pinfunction "1_1") (pintype "passive"))
      (node (ref "C46") (pin "1") (pinfunction "1_1") (pintype "passive"))
      (node (ref "H1") (pin "2.8") (pinfunction "2.8_2.8") (pintype "bidirectional"))
      (node (ref "L4") (pin "2") (pinfunction "2_2") (pintype "bidirectional"))
      (node (ref "R41") (pin "2") (pinfunction "2_2") (pintype "passive"))
      (node (ref "R42") (pin "2") (pinfunction "2_2") (pintype "passive"))
    )
    (net (code "103") (name "SW1_EN") (class "Default")
      (node (ref "TB1") (pin "P7") (pinfunction "D4_P7") (pintype "bidirectional"))
      (node (ref "U14") (pin "136") (pinfunction "PC25_136") (pintype "bidirectional"))
      (node (ref "U3") (pin "10") (pinfunction "EN_10") (pintype "bidirectional"))
    )
    (net (code "104") (name "SW2") (class "Default")
      (node (ref "C65") (pin "1") (pinfunction "1_1") (pintype "passive"))
      (node (ref "H1") (pin "2.13") (pinfunction "2.13_2.13") (pintype "bidirectional"))
      (node (ref "U6") (pin "1") (pinfunction "VOUT_1") (pintype "bidirectional"))
      (node (ref "U6") (pin "8") (pinfunction "VOUT_8") (pintype "bidirectional"))
    )
    (net (code "105") (name "SW2_EN") (class "Default")
      (node (ref "TB1") (pin "P8") (pinfunction "D5_P8") (pintype "bidirectional"))
      (node (ref "U14") (pin "135") (pinfunction "PC24_135") (pintype "bidirectional"))
      (node (ref "U6") (pin "4") (pinfunction "EN_4") (pintype "bidirectional"))
    )
    (net (code "106") (name "SW3") (class "Default")
      (node (ref "C66") (pin "1") (pinfunction "1_1") (pintype "passive"))
      (node (ref "H1") (pin "2.15") (pinfunction "2.15_2.15") (pintype "bidirectional"))
      (node (ref "U7") (pin "1") (pinfunction "VOUT_1") (pintype "bidirectional"))
      (node (ref "U7") (pin "8") (pinfunction "VOUT_8") (pintype "bidirectional"))
    )
    (net (code "107") (name "SW3_EN") (class "Default")
      (node (ref "TB1") (pin "P9") (pinfunction "D6_P9") (pintype "bidirectional"))
      (node (ref "U14") (pin "134") (pinfunction "PC23_134") (pintype "bidirectional"))
      (node (ref "U7") (pin "4") (pinfunction "EN_4") (pintype "bidirectional"))
    )
    (net (code "108") (name "SW4") (class "Default")
      (node (ref "C67") (pin "1") (pinfunction "1_1") (pintype "passive"))
      (node (ref "H1") (pin "2.16") (pinfunction "2.16_2.16") (pintype "bidirectional"))
      (node (ref "U8") (pin "1") (pinfunction "VOUT_1") (pintype "bidirectional"))
      (node (ref "U8") (pin "8") (pinfunction "VOUT_8") (pintype "bidirectional"))
    )
    (net (code "109") (name "SW4_EN") (class "Default")
      (node (ref "TB1") (pin "P10") (pinfunction "D7_P10") (pintype "bidirectional"))
      (node (ref "U14") (pin "133") (pinfunction "PC22_133") (pintype "bidirectional"))
      (node (ref "U8") (pin "4") (pinfunction "EN_4") (pintype "bidirectional"))
    )
    (net (code "110") (name "SW5") (class "Default")
      (node (ref "C68") (pin "1") (pinfunction "1_1") (pintype "passive"))
      (node (ref "H1") (pin "2.19") (pinfunction "2.19_2.19") (pintype "bidirectional"))
      (node (ref "H1") (pin "2.20") (pinfunction "2.20_2.20") (pintype "bidirectional"))
      (node (ref "U9") (pin "1") (pinfunction "VOUT_1") (pintype "bidirectional"))
      (node (ref "U9") (pin "8") (pinfunction "VOUT_8") (pintype "bidirectional"))
    )
    (net (code "111") (name "SW5_EN") (class "Default")
      (node (ref "TB1") (pin "P12") (pinfunction "D9_P12") (pintype "bidirectional"))
      (node (ref "U14") (pin "132") (pinfunction "PC21_132") (pintype "bidirectional"))
      (node (ref "U9") (pin "4") (pinfunction "EN_4") (pintype "bidirectional"))
    )
    (net (code "112") (name "U1_VCC") (class "Default")
      (node (ref "C3") (pin "1") (pinfunction "1_1") (pintype "passive"))
      (node (ref "R7") (pin "2") (pinfunction "2_2") (pintype "passive"))
      (node (ref "R8") (pin "2") (pinfunction "2_2") (pintype "passive"))
      (node (ref "U1") (pin "9") (pinfunction "VCC_9") (pintype "power_in"))
    )
    (net (code "113") (name "U2_READY") (class "Default")
      (node (ref "U2") (pin "5") (pinfunction "READY_5") (pintype "bidirectional"))
    )
    (net (code "114") (name "U11_CS") (class "Default")
      (node (ref "TB1") (pin "P11") (pinfunction "D8_P11") (pintype "bidirectional"))
      (node (ref "U11") (pin "4") (pinfunction "CS_4") (pintype "bidirectional"))
      (node (ref "U14") (pin "111") (pinfunction "PA28_111") (pintype "bidirectional"))
    )
    (net (code "115") (name "U11_DIN") (class "Default")
      (node (ref "TB1") (pin "P14") (pinfunction "MOSI_P14") (pintype "bidirectional"))
      (node (ref "U11") (pin "3") (pinfunction "DIN_3") (pintype "bidirectional"))
      (node (ref "U14") (pin "20") (pinfunction "PD7_20") (pintype "bidirectional"))
    )
    (net (code "116") (name "U11_DOUT") (class "Default")
      (node (ref "TB1") (pin "P15") (pinfunction "MISO_P15") (pintype "bidirectional"))
      (node (ref "U11") (pin "2") (pinfunction "DOUT_2") (pintype "bidirectional"))
      (node (ref "U14") (pin "21") (pinfunction "PD8_21") (pintype "bidirectional"))
    )
    (net (code "117") (name "U11_SCLK") (class "Default")
      (node (ref "TB1") (pin "P16") (pinfunction "SCK_P16") (pintype "bidirectional"))
      (node (ref "U11") (pin "1") (pinfunction "SCLK_1") (pintype "bidirectional"))
      (node (ref "U14") (pin "88") (pinfunction "PB17_88") (pintype "bidirectional"))
    )
    (net (code "118") (name "USB_DM") (class "Default")
      (node (ref "J8") (pin "A7") (pinfunction "DN1_A7") (pintype "bidirectional"))
      (node (ref "J8") (pin "B7") (pinfunction "DN2_B7") (pintype "bidirectional"))
      (node (ref "R65") (pin "1") (pinfunction "1_1") (pintype "passive"))
      (node (ref "U14") (pin "38") (pinfunction "DHSDM_38") (pintype "bidirectional"))
    )
    (net (code "119") (name "USB_DP") (class "Default")
      (node (ref "J8") (pin "A6") (pinfunction "DP1_A6") (pintype "bidirectional"))
      (node (ref "J8") (pin "B6") (pinfunction "DP2_B6") (pintype "bidirectional"))
      (node (ref "R66") (pin "1") (pinfunction "1_1") (pintype "passive"))
      (node (ref "U14") (pin "37") (pinfunction "DHSDP_37") (pintype "bidirectional"))
    )
    (net (code "120") (name "USB_OTG_ID") (class "Default")
      (node (ref "U14") (pin "129") (pinfunction "PB11_129") (pintype "bidirectional"))
    )
    (net (code "121") (name "USB_OTG_VBOF") (class "Default")
      (node (ref "R70") (pin "1") (pinfunction "1_1") (pintype "passive"))
      (node (ref "U14") (pin "128") (pinfunction "PB10_128") (pintype "bidirectional"))
    )
    (net (code "122") (name "USB_VBUS") (class "Default")
      (node (ref "C101") (pin "1") (pinfunction "1_1") (pintype "passive"))
      (node (ref "J8") (pin "A4") (pinfunction "VBUS_A4") (pintype "power_in"))
      (node (ref "J8") (pin "A9") (pinfunction "VBUS_A9") (pintype "power_in"))
      (node (ref "J8") (pin "B4") (pinfunction "VBUS_B4") (pintype "power_in"))
      (node (ref "J8") (pin "B9") (pinfunction "VBUS_B9") (pintype "power_in"))
      (node (ref "U14") (pin "39") (pinfunction "VBUS_39") (pintype "bidirectional"))
      (node (ref "U18") (pin "3") (pinfunction "D_3") (pintype "passive"))
    )
    (net (code "123") (name "VBAT_BUS") (class "Default")
      (node (ref "C69") (pin "1") (pinfunction "1_1") (pintype "passive"))
      (node (ref "H1") (pin "2.45") (pinfunction "2.45_2.45") (pintype "bidirectional"))
      (node (ref "H1") (pin "2.46") (pinfunction "2.46_2.46") (pintype "bidirectional"))
      (node (ref "U10") (pin "1") (pinfunction "VOUT_1") (pintype "bidirectional"))
      (node (ref "U10") (pin "8") (pinfunction "VOUT_8") (pintype "bidirectional"))
    )
    (net (code "124") (name "VBAT_EN") (class "Default")
      (node (ref "TB1") (pin "P6") (pinfunction "D3_P6") (pintype "bidirectional"))
      (node (ref "U10") (pin "4") (pinfunction "EN_4") (pintype "bidirectional"))
      (node (ref "U14") (pin "112") (pinfunction "PA29_112") (pintype "bidirectional"))
    )
    (net (code "125") (name "VDDANA") (class "Default")
      (node (ref "C80") (pin "1") (pinfunction "1_1") (pintype "passive"))
      (node (ref "C81") (pin "1") (pinfunction "1_1") (pintype "passive"))
      (node (ref "FB6") (pin "2") (pinfunction "2_2") (pintype "bidirectional"))
      (node (ref "U14") (pin "73") (pinfunction "VDDANA_73") (pintype "bidirectional"))
    )
    (net (code "126") (name "VDDOUTMI") (class "Default")
      (node (ref "C82") (pin "1") (pinfunction "1_1") (pintype "passive"))
      (node (ref "C83") (pin "1") (pinfunction "1_1") (pintype "passive"))
      (node (ref "FB7") (pin "2") (pinfunction "2_2") (pintype "bidirectional"))
      (node (ref "U14") (pin "41") (pinfunction "VDDOUTMI_41") (pintype "bidirectional"))
    )
    (net (code "127") (name "VIN") (class "Default")
      (node (ref "C10") (pin "2") (pinfunction "2_2") (pintype "passive"))
      (node (ref "C8") (pin "2") (pinfunction "2_2") (pintype "passive"))
      (node (ref "C9") (pin "2") (pinfunction "2_2") (pintype "passive"))
      (node (ref "D1") (pin "C") (pinfunction "C_C") (pintype "passive"))
      (node (ref "D2") (pin "C") (pinfunction "C_C") (pintype "passive"))
      (node (ref "D3") (pin "C") (pinfunction "C_C") (pintype "passive"))
      (node (ref "D4") (pin "C") (pinfunction "C_C") (pintype "passive"))
      (node (ref "D5") (pin "C") (pinfunction "C_C") (pintype "passive"))
      (node (ref "D6") (pin "C") (pinfunction "C_C") (pintype "passive"))
      (node (ref "D7") (pin "C") (pinfunction "C_C") (pintype "passive"))
      (node (ref "R16") (pin "2") (pinfunction "2_2") (pintype "passive"))
      (node (ref "R9") (pin "1") (pinfunction "1_1") (pintype "passive"))
      (node (ref "U1") (pin "1") (pinfunction "VL_1") (pintype "passive"))
    )
    (net (code "128") (name "VLIM") (class "Default")
      (node (ref "R10") (pin "1") (pinfunction "1_1") (pintype "passive"))
      (node (ref "R9") (pin "2") (pinfunction "2_2") (pintype "passive"))
      (node (ref "U1") (pin "18") (pinfunction "VLIM_18") (pintype "passive"))
    )
    (net (code "129") (name "unconnected-(H1-Pad1.1)") (class "Default")
      (node (ref "H1") (pin "1.1") (pinfunction "1.1_1.1") (pintype "bidirectional"))
    )
    (net (code "130") (name "unconnected-(H1-Pad1.2)") (class "Default")
      (node (ref "H1") (pin "1.2") (pinfunction "1.2_1.2") (pintype "bidirectional"))
    )
    (net (code "131") (name "unconnected-(H1-Pad1.3)") (class "Default")
      (node (ref "H1") (pin "1.3") (pinfunction "1.3_1.3") (pintype "bidirectional"))
    )
    (net (code "132") (name "unconnected-(H1-Pad1.4)") (class "Default")
      (node (ref "H1") (pin "1.4") (pinfunction "1.4_1.4") (pintype "bidirectional"))
    )
    (net (code "133") (name "unconnected-(H1-Pad1.5)") (class "Default")
      (node (ref "H1") (pin "1.5") (pinfunction "1.5_1.5") (pintype "bidirectional"))
    )
    (net (code "134") (name "unconnected-(H1-Pad1.6)") (class "Default")
      (node (ref "H1") (pin "1.6") (pinfunction "1.6_1.6") (pintype "bidirectional"))
    )
    (net (code "135") (name "unconnected-(H1-Pad1.7)") (class "Default")
      (node (ref "H1") (pin "1.7") (pinfunction "1.7_1.7") (pintype "bidirectional"))
    )
    (net (code "136") (name "unconnected-(H1-Pad1.8)") (class "Default")
      (node (ref "H1") (pin "1.8") (pinfunction "1.8_1.8") (pintype "bidirectional"))
    )
    (net (code "137") (name "unconnected-(H1-Pad1.9)") (class "Default")
      (node (ref "H1") (pin "1.9") (pinfunction "1.9_1.9") (pintype "bidirectional"))
    )
    (net (code "138") (name "unconnected-(H1-Pad1.10)") (class "Default")
      (node (ref "H1") (pin "1.10") (pinfunction "1.10_1.10") (pintype "bidirectional"))
    )
    (net (code "139") (name "unconnected-(H1-Pad1.11)") (class "Default")
      (node (ref "H1") (pin "1.11") (pinfunction "1.11_1.11") (pintype "bidirectional"))
    )
    (net (code "140") (name "unconnected-(H1-Pad1.12)") (class "Default")
      (node (ref "H1") (pin "1.12") (pinfunction "1.12_1.12") (pintype "bidirectional"))
    )
    (net (code "141") (name "unconnected-(H1-Pad1.13)") (class "Default")
      (node (ref "H1") (pin "1.13") (pinfunction "1.13_1.13") (pintype "bidirectional"))
    )
    (net (code "142") (name "unconnected-(H1-Pad1.14)") (class "Default")
      (node (ref "H1") (pin "1.14") (pinfunction "1.14_1.14") (pintype "bidirectional"))
    )
    (net (code "143") (name "unconnected-(H1-Pad1.15)") (class "Default")
      (node (ref "H1") (pin "1.15") (pinfunction "1.15_1.15") (pintype "bidirectional"))
    )
    (net (code "144") (name "unconnected-(H1-Pad1.16)") (class "Default")
      (node (ref "H1") (pin "1.16") (pinfunction "1.16_1.16") (pintype "bidirectional"))
    )
    (net (code "145") (name "unconnected-(H1-Pad1.17)") (class "Default")
      (node (ref "H1") (pin "1.17") (pinfunction "1.17_1.17") (pintype "bidirectional"))
    )
    (net (code "146") (name "unconnected-(H1-Pad1.18)") (class "Default")
      (node (ref "H1") (pin "1.18") (pinfunction "1.18_1.18") (pintype "bidirectional"))
    )
    (net (code "147") (name "unconnected-(H1-Pad1.19)") (class "Default")
      (node (ref "H1") (pin "1.19") (pinfunction "1.19_1.19") (pintype "bidirectional"))
    )
    (net (code "148") (name "unconnected-(H1-Pad1.20)") (class "Default")
      (node (ref "H1") (pin "1.20") (pinfunction "1.20_1.20") (pintype "bidirectional"))
    )
    (net (code "149") (name "unconnected-(H1-Pad1.21)") (class "Default")
      (node (ref "H1") (pin "1.21") (pinfunction "1.21_1.21") (pintype "bidirectional"))
    )
    (net (code "150") (name "unconnected-(H1-Pad1.22)") (class "Default")
      (node (ref "H1") (pin "1.22") (pinfunction "1.22_1.22") (pintype "bidirectional"))
    )
    (net (code "151") (name "unconnected-(H1-Pad1.23)") (class "Default")
      (node (ref "H1") (pin "1.23") (pinfunction "1.23_1.23") (pintype "bidirectional"))
    )
    (net (code "152") (name "unconnected-(H1-Pad1.24)") (class "Default")
      (node (ref "H1") (pin "1.24") (pinfunction "1.24_1.24") (pintype "bidirectional"))
    )
    (net (code "153") (name "unconnected-(H1-Pad1.25)") (class "Default")
      (node (ref "H1") (pin "1.25") (pinfunction "1.25_1.25") (pintype "bidirectional"))
    )
    (net (code "154") (name "unconnected-(H1-Pad1.26)") (class "Default")
      (node (ref "H1") (pin "1.26") (pinfunction "1.26_1.26") (pintype "bidirectional"))
    )
    (net (code "155") (name "unconnected-(H1-Pad1.27)") (class "Default")
      (node (ref "H1") (pin "1.27") (pinfunction "1.27_1.27") (pintype "bidirectional"))
    )
    (net (code "156") (name "unconnected-(H1-Pad1.28)") (class "Default")
      (node (ref "H1") (pin "1.28") (pinfunction "1.28_1.28") (pintype "bidirectional"))
    )
    (net (code "157") (name "unconnected-(H1-Pad1.29)") (class "Default")
      (node (ref "H1") (pin "1.29") (pinfunction "1.29_1.29") (pintype "bidirectional"))
    )
    (net (code "158") (name "unconnected-(H1-Pad1.30)") (class "Default")
      (node (ref "H1") (pin "1.30") (pinfunction "1.30_1.30") (pintype "bidirectional"))
    )
    (net (code "159") (name "unconnected-(H1-Pad1.31)") (class "Default")
      (node (ref "H1") (pin "1.31") (pinfunction "1.31_1.31") (pintype "bidirectional"))
    )
    (net (code "160") (name "unconnected-(H1-Pad1.33)") (class "Default")
      (node (ref "H1") (pin "1.33") (pinfunction "1.33_1.33") (pintype "bidirectional"))
    )
    (net (code "161") (name "unconnected-(H1-Pad1.34)") (class "Default")
      (node (ref "H1") (pin "1.34") (pinfunction "1.34_1.34") (pintype "bidirectional"))
    )
    (net (code "162") (name "unconnected-(H1-Pad1.35)") (class "Default")
      (node (ref "H1") (pin "1.35") (pinfunction "1.35_1.35") (pintype "bidirectional"))
    )
    (net (code "163") (name "unconnected-(H1-Pad1.36)") (class "Default")
      (node (ref "H1") (pin "1.36") (pinfunction "1.36_1.36") (pintype "bidirectional"))
    )
    (net (code "164") (name "unconnected-(H1-Pad1.37)") (class "Default")
      (node (ref "H1") (pin "1.37") (pinfunction "1.37_1.37") (pintype "bidirectional"))
    )
    (net (code "165") (name "unconnected-(H1-Pad1.38)") (class "Default")
      (node (ref "H1") (pin "1.38") (pinfunction "1.38_1.38") (pintype "bidirectional"))
    )
    (net (code "166") (name "unconnected-(H1-Pad1.39)") (class "Default")
      (node (ref "H1") (pin "1.39") (pinfunction "1.39_1.39") (pintype "bidirectional"))
    )
    (net (code "167") (name "unconnected-(H1-Pad1.40)") (class "Default")
      (node (ref "H1") (pin "1.40") (pinfunction "1.40_1.40") (pintype "bidirectional"))
    )
    (net (code "168") (name "unconnected-(H1-Pad1.42)") (class "Default")
      (node (ref "H1") (pin "1.42") (pinfunction "1.42_1.42") (pintype "bidirectional"))
    )
    (net (code "169") (name "unconnected-(H1-Pad1.44)") (class "Default")
      (node (ref "H1") (pin "1.44") (pinfunction "1.44_1.44") (pintype "bidirectional"))
    )
    (net (code "170") (name "unconnected-(H1-Pad1.45)") (class "Default")
      (node (ref "H1") (pin "1.45") (pinfunction "1.45_1.45") (pintype "bidirectional"))
    )
    (net (code "171") (name "unconnected-(H1-Pad1.46)") (class "Default")
      (node (ref "H1") (pin "1.46") (pinfunction "1.46_1.46") (pintype "bidirectional"))
    )
    (net (code "172") (name "unconnected-(H1-Pad1.47)") (class "Default")
      (node (ref "H1") (pin "1.47") (pinfunction "1.47_1.47") (pintype "bidirectional"))
    )
    (net (code "173") (name "unconnected-(H1-Pad1.48)") (class "Default")
      (node (ref "H1") (pin "1.48") (pinfunction "1.48_1.48") (pintype "bidirectional"))
    )
    (net (code "174") (name "unconnected-(H1-Pad1.50)") (class "Default")
      (node (ref "H1") (pin "1.50") (pinfunction "1.50_1.50") (pintype "bidirectional"))
    )
    (net (code "175") (name "unconnected-(H1-Pad2.1)") (class "Default")
      (node (ref "H1") (pin "2.1") (pinfunction "2.1_2.1") (pintype "bidirectional"))
    )
    (net (code "176") (name "unconnected-(H1-Pad2.2)") (class "Default")
      (node (ref "H1") (pin "2.2") (pinfunction "2.2_2.2") (pintype "bidirectional"))
    )
    (net (code "177") (name "unconnected-(H1-Pad2.3)") (class "Default")
      (node (ref "H1") (pin "2.3") (pinfunction "2.3_2.3") (pintype "bidirectional"))
    )
    (net (code "178") (name "unconnected-(H1-Pad2.4)") (class "Default")
      (node (ref "H1") (pin "2.4") (pinfunction "2.4_2.4") (pintype "bidirectional"))
    )
    (net (code "179") (name "unconnected-(H1-Pad2.5)") (class "Default")
      (node (ref "H1") (pin "2.5") (pinfunction "2.5_2.5") (pintype "bidirectional"))
    )
    (net (code "180") (name "unconnected-(H1-Pad2.6)") (class "Default")
      (node (ref "H1") (pin "2.6") (pinfunction "2.6_2.6") (pintype "bidirectional"))
    )
    (net (code "181") (name "unconnected-(H1-Pad2.7)") (class "Default")
      (node (ref "H1") (pin "2.7") (pinfunction "2.7_2.7") (pintype "bidirectional"))
    )
    (net (code "182") (name "unconnected-(H1-Pad2.10)") (class "Default")
      (node (ref "H1") (pin "2.10") (pinfunction "2.10_2.10") (pintype "bidirectional"))
    )
    (net (code "183") (name "unconnected-(H1-Pad2.11)") (class "Default")
      (node (ref "H1") (pin "2.11") (pinfunction "2.11_2.11") (pintype "bidirectional"))
    )
    (net (code "184") (name "unconnected-(H1-Pad2.12)") (class "Default")
      (node (ref "H1") (pin "2.12") (pinfunction "2.12_2.12") (pintype "bidirectional"))
    )
    (net (code "185") (name "unconnected-(H1-Pad2.18)") (class "Default")
      (node (ref "H1") (pin "2.18") (pinfunction "2.18_2.18") (pintype "bidirectional"))
    )
    (net (code "186") (name "unconnected-(H1-Pad2.23)") (class "Default")
      (node (ref "H1") (pin "2.23") (pinfunction "2.23_2.23") (pintype "bidirectional"))
    )
    (net (code "187") (name "unconnected-(H1-Pad2.24)") (class "Default")
      (node (ref "H1") (pin "2.24") (pinfunction "2.24_2.24") (pintype "bidirectional"))
    )
    (net (code "188") (name "unconnected-(H1-Pad2.31)") (class "Default")
      (node (ref "H1") (pin "2.31") (pinfunction "2.31_2.31") (pintype "bidirectional"))
    )
    (net (code "189") (name "unconnected-(H1-Pad2.33)") (class "Default")
      (node (ref "H1") (pin "2.33") (pinfunction "2.33_2.33") (pintype "bidirectional"))
    )
    (net (code "190") (name "unconnected-(H1-Pad2.34)") (class "Default")
      (node (ref "H1") (pin "2.34") (pinfunction "2.34_2.34") (pintype "bidirectional"))
    )
    (net (code "191") (name "unconnected-(H1-Pad2.37)") (class "Default")
      (node (ref "H1") (pin "2.37") (pinfunction "2.37_2.37") (pintype "bidirectional"))
    )
    (net (code "192") (name "unconnected-(H1-Pad2.38)") (class "Default")
      (node (ref "H1") (pin "2.38") (pinfunction "2.38_2.38") (pintype "bidirectional"))
    )
    (net (code "193") (name "unconnected-(H1-Pad2.39)") (class "Default")
      (node (ref "H1") (pin "2.39") (pinfunction "2.39_2.39") (pintype "bidirectional"))
    )
    (net (code "194") (name "unconnected-(H1-Pad2.40)") (class "Default")
      (node (ref "H1") (pin "2.40") (pinfunction "2.40_2.40") (pintype "bidirectional"))
    )
    (net (code "195") (name "unconnected-(H1-Pad2.49)") (class "Default")
      (node (ref "H1") (pin "2.49") (pinfunction "2.49_2.49") (pintype "bidirectional"))
    )
    (net (code "196") (name "unconnected-(H1-Pad2.50)") (class "Default")
      (node (ref "H1") (pin "2.50") (pinfunction "2.50_2.50") (pintype "bidirectional"))
    )
    (net (code "197") (name "unconnected-(H1-Pad2.51)") (class "Default")
      (node (ref "H1") (pin "2.51") (pinfunction "2.51_2.51") (pintype "bidirectional"))
    )
    (net (code "198") (name "unconnected-(H1-Pad2.52)") (class "Default")
      (node (ref "H1") (pin "2.52") (pinfunction "2.52_2.52") (pintype "bidirectional"))
    )
    (net (code "199") (name "unconnected-(J7-Pad7)") (class "Default")
      (node (ref "J7") (pin "7") (pinfunction "7_7") (pintype "passive"))
    )
    (net (code "200") (name "unconnected-(J8-SBU1-PadA8)") (class "Default")
      (node (ref "J8") (pin "A8") (pinfunction "SBU1_A8") (pintype "bidirectional"))
    )
    (net (code "201") (name "unconnected-(J8-SBU2-PadB8)") (class "Default")
      (node (ref "J8") (pin "B8") (pinfunction "SBU2_B8") (pintype "bidirectional"))
    )
    (net (code "202") (name "unconnected-(J8-SSRXN1-PadB10)") (class "Default")
      (node (ref "J8") (pin "B10") (pinfunction "SSRXN1_B10") (pintype "bidirectional"))
    )
    (net (code "203") (name "unconnected-(J8-SSRXN2-PadA10)") (class "Default")
      (node (ref "J8") (pin "A10") (pinfunction "SSRXN2_A10") (pintype "bidirectional"))
    )
    (net (code "204") (name "unconnected-(J8-SSRXP1-PadB11)") (class "Default")
      (node (ref "J8") (pin "B11") (pinfunction "SSRXP1_B11") (pintype "bidirectional"))
    )
    (net (code "205") (name "unconnected-(J8-SSRXP2-PadA11)") (class "Default")
      (node (ref "J8") (pin "A11") (pinfunction "SSRXP2_A11") (pintype "bidirectional"))
    )
    (net (code "206") (name "unconnected-(J8-SSTXN1-PadA3)") (class "Default")
      (node (ref "J8") (pin "A3") (pinfunction "SSTXN1_A3") (pintype "bidirectional"))
    )
    (net (code "207") (name "unconnected-(J8-SSTXN2-PadB3)") (class "Default")
      (node (ref "J8") (pin "B3") (pinfunction "SSTXN2_B3") (pintype "bidirectional"))
    )
    (net (code "208") (name "unconnected-(J8-SSTXP1-PadA2)") (class "Default")
      (node (ref "J8") (pin "A2") (pinfunction "SSTXP1_A2") (pintype "bidirectional"))
    )
    (net (code "209") (name "unconnected-(J8-SSTXP2-PadB2)") (class "Default")
      (node (ref "J8") (pin "B2") (pinfunction "SSTXP2_B2") (pintype "bidirectional"))
    )
    (net (code "210") (name "unconnected-(TB1-+5V-PadP27)") (class "Default")
      (node (ref "TB1") (pin "P27") (pinfunction "+5V_P27") (pintype "bidirectional"))
    )
    (net (code "211") (name "unconnected-(TB1-AIN0-PadP22)") (class "Default")
      (node (ref "TB1") (pin "P22") (pinfunction "AIN0_P22") (pintype "bidirectional"))
    )
    (net (code "212") (name "unconnected-(TB1-AIN1-PadP21)") (class "Default")
      (node (ref "TB1") (pin "P21") (pinfunction "AIN1_P21") (pintype "bidirectional"))
    )
    (net (code "213") (name "unconnected-(TB1-AIN2-PadP20)") (class "Default")
      (node (ref "TB1") (pin "P20") (pinfunction "AIN2_P20") (pintype "bidirectional"))
    )
    (net (code "214") (name "unconnected-(TB1-AIN3-PadP19)") (class "Default")
      (node (ref "TB1") (pin "P19") (pinfunction "AIN3_P19") (pintype "bidirectional"))
    )
    (net (code "215") (name "unconnected-(TB1-AIN4-PadP25)") (class "Default")
      (node (ref "TB1") (pin "P25") (pinfunction "AIN4_P25") (pintype "bidirectional"))
    )
    (net (code "216") (name "unconnected-(TB1-AIN5-PadP26)") (class "Default")
      (node (ref "TB1") (pin "P26") (pinfunction "AIN5_P26") (pintype "bidirectional"))
    )
    (net (code "217") (name "unconnected-(TB1-AREF-PadP18)") (class "Default")
      (node (ref "TB1") (pin "P18") (pinfunction "AREF_P18") (pintype "bidirectional"))
    )
    (net (code "218") (name "unconnected-(U1-~{PB}-Pad7)") (class "Default")
      (node (ref "U1") (pin "7") (pinfunction "~{PB}_7") (pintype "passive"))
    )
    (net (code "219") (name "unconnected-(U6-VIN3-Pad6)") (class "Default")
      (node (ref "U6") (pin "6") (pinfunction "VIN3_6") (pintype "bidirectional"))
    )
    (net (code "220") (name "unconnected-(U7-VIN3-Pad6)") (class "Default")
      (node (ref "U7") (pin "6") (pinfunction "VIN3_6") (pintype "bidirectional"))
    )
    (net (code "221") (name "unconnected-(U8-VIN3-Pad6)") (class "Default")
      (node (ref "U8") (pin "6") (pinfunction "VIN3_6") (pintype "bidirectional"))
    )
    (net (code "222") (name "unconnected-(U9-VIN3-Pad6)") (class "Default")
      (node (ref "U9") (pin "6") (pinfunction "VIN3_6") (pintype "bidirectional"))
    )
    (net (code "223") (name "unconnected-(U10-VIN3-Pad6)") (class "Default")
      (node (ref "U10") (pin "6") (pinfunction "VIN3_6") (pintype "bidirectional"))
    )
    (net (code "224") (name "unconnected-(U14-NRST-Pad69)") (class "Default")
      (node (ref "U14") (pin "69") (pinfunction "NRST_69") (pintype "bidirectional"))
    )
    (net (code "225") (name "unconnected-(U14-PA0-Pad23)") (class "Default")
      (node (ref "U14") (pin "23") (pinfunction "PA0_23") (pintype "bidirectional"))
    )
    (net (code "226") (name "unconnected-(U14-PA1-Pad24)") (class "Default")
      (node (ref "U14") (pin "24") (pinfunction "PA1_24") (pintype "bidirectional"))
    )
    (net (code "227") (name "unconnected-(U14-PA2-Pad85)") (class "Default")
      (node (ref "U14") (pin "85") (pinfunction "PA2_85") (pintype "bidirectional"))
    )
    (net (code "228") (name "unconnected-(U14-PA3-Pad84)") (class "Default")
      (node (ref "U14") (pin "84") (pinfunction "PA3_84") (pintype "bidirectional"))
    )
    (net (code "229") (name "unconnected-(U14-PA4-Pad83)") (class "Default")
      (node (ref "U14") (pin "83") (pinfunction "PA4_83") (pintype "bidirectional"))
    )
    (net (code "230") (name "unconnected-(U14-PA5-Pad25)") (class "Default")
      (node (ref "U14") (pin "25") (pinfunction "PA5_25") (pintype "bidirectional"))
    )
    (net (code "231") (name "unconnected-(U14-PA6-Pad82)") (class "Default")
      (node (ref "U14") (pin "82") (pinfunction "PA6_82") (pintype "bidirectional"))
    )
    (net (code "232") (name "unconnected-(U14-PA7-Pad26)") (class "Default")
      (node (ref "U14") (pin "26") (pinfunction "PA7_26") (pintype "bidirectional"))
    )
    (net (code "233") (name "unconnected-(U14-PA10-Pad3)") (class "Default")
      (node (ref "U14") (pin "3") (pinfunction "PA10_3") (pintype "bidirectional"))
    )
    (net (code "234") (name "unconnected-(U14-PA11-Pad4)") (class "Default")
      (node (ref "U14") (pin "4") (pinfunction "PA11_4") (pintype "bidirectional"))
    )
    (net (code "235") (name "unconnected-(U14-PA12-Pad5)") (class "Default")
      (node (ref "U14") (pin "5") (pinfunction "PA12_5") (pintype "bidirectional"))
    )
    (net (code "236") (name "unconnected-(U14-PA13-Pad6)") (class "Default")
      (node (ref "U14") (pin "6") (pinfunction "PA13_6") (pintype "bidirectional"))
    )
    (net (code "237") (name "unconnected-(U14-PA14-Pad7)") (class "Default")
      (node (ref "U14") (pin "7") (pinfunction "PA14_7") (pintype "bidirectional"))
    )
    (net (code "238") (name "unconnected-(U14-PA15-Pad8)") (class "Default")
      (node (ref "U14") (pin "8") (pinfunction "PA15_8") (pintype "bidirectional"))
    )
    (net (code "239") (name "unconnected-(U14-PA16-Pad78)") (class "Default")
      (node (ref "U14") (pin "78") (pinfunction "PA16_78") (pintype "bidirectional"))
    )
    (net (code "240") (name "unconnected-(U14-PA19-Pad71)") (class "Default")
      (node (ref "U14") (pin "71") (pinfunction "PA19_71") (pintype "bidirectional"))
    )
    (net (code "241") (name "unconnected-(U14-PA20-Pad72)") (class "Default")
      (node (ref "U14") (pin "72") (pinfunction "PA20_72") (pintype "bidirectional"))
    )
    (net (code "242") (name "unconnected-(U14-PA21-Pad107)") (class "Default")
      (node (ref "U14") (pin "107") (pinfunction "PA21_107") (pintype "bidirectional"))
    )
    (net (code "243") (name "unconnected-(U14-PA22-Pad81)") (class "Default")
      (node (ref "U14") (pin "81") (pinfunction "PA22_81") (pintype "bidirectional"))
    )
    (net (code "244") (name "unconnected-(U14-PA23-Pad80)") (class "Default")
      (node (ref "U14") (pin "80") (pinfunction "PA23_80") (pintype "bidirectional"))
    )
    (net (code "245") (name "unconnected-(U14-PA24-Pad79)") (class "Default")
      (node (ref "U14") (pin "79") (pinfunction "PA24_79") (pintype "bidirectional"))
    )
    (net (code "246") (name "unconnected-(U14-PA25-Pad108)") (class "Default")
      (node (ref "U14") (pin "108") (pinfunction "PA25_108") (pintype "bidirectional"))
    )
    (net (code "247") (name "unconnected-(U14-PA26-Pad109)") (class "Default")
      (node (ref "U14") (pin "109") (pinfunction "PA26_109") (pintype "bidirectional"))
    )
    (net (code "248") (name "unconnected-(U14-PA27-Pad110)") (class "Default")
      (node (ref "U14") (pin "110") (pinfunction "PA27_110") (pintype "bidirectional"))
    )
    (net (code "249") (name "unconnected-(U14-PB0-Pad113)") (class "Default")
      (node (ref "U14") (pin "113") (pinfunction "PB0_113") (pintype "bidirectional"))
    )
    (net (code "250") (name "unconnected-(U14-PB1-Pad114)") (class "Default")
      (node (ref "U14") (pin "114") (pinfunction "PB1_114") (pintype "bidirectional"))
    )
    (net (code "251") (name "unconnected-(U14-PB2-Pad115)") (class "Default")
      (node (ref "U14") (pin "115") (pinfunction "PB2_115") (pintype "bidirectional"))
    )
    (net (code "252") (name "unconnected-(U14-PB3-Pad118)") (class "Default")
      (node (ref "U14") (pin "118") (pinfunction "PB3_118") (pintype "bidirectional"))
    )
    (net (code "253") (name "unconnected-(U14-PB4-Pad119)") (class "Default")
      (node (ref "U14") (pin "119") (pinfunction "PB4_119") (pintype "bidirectional"))
    )
    (net (code "254") (name "unconnected-(U14-PB5-Pad120)") (class "Default")
      (node (ref "U14") (pin "120") (pinfunction "PB5_120") (pintype "bidirectional"))
    )
    (net (code "255") (name "unconnected-(U14-PB6-Pad121)") (class "Default")
      (node (ref "U14") (pin "121") (pinfunction "PB6_121") (pintype "bidirectional"))
    )
    (net (code "256") (name "unconnected-(U14-PB7-Pad122)") (class "Default")
      (node (ref "U14") (pin "122") (pinfunction "PB7_122") (pintype "bidirectional"))
    )
    (net (code "257") (name "unconnected-(U14-PB8-Pad123)") (class "Default")
      (node (ref "U14") (pin "123") (pinfunction "PB8_123") (pintype "bidirectional"))
    )
    (net (code "258") (name "unconnected-(U14-PB9-Pad127)") (class "Default")
      (node (ref "U14") (pin "127") (pinfunction "PB9_127") (pintype "bidirectional"))
    )
    (net (code "259") (name "unconnected-(U14-PB12-Pad86)") (class "Default")
      (node (ref "U14") (pin "86") (pinfunction "PB12_86") (pintype "bidirectional"))
    )
    (net (code "260") (name "unconnected-(U14-PB13-Pad87)") (class "Default")
      (node (ref "U14") (pin "87") (pinfunction "PB13_87") (pintype "bidirectional"))
    )
    (net (code "261") (name "unconnected-(U14-PB14-Pad140)") (class "Default")
      (node (ref "U14") (pin "140") (pinfunction "PB14_140") (pintype "bidirectional"))
    )
    (net (code "262") (name "unconnected-(U14-PB15-Pad76)") (class "Default")
      (node (ref "U14") (pin "76") (pinfunction "PB15_76") (pintype "bidirectional"))
    )
    (net (code "263") (name "unconnected-(U14-PB16-Pad77)") (class "Default")
      (node (ref "U14") (pin "77") (pinfunction "PB16_77") (pintype "bidirectional"))
    )
    (net (code "264") (name "unconnected-(U14-PB18-Pad89)") (class "Default")
      (node (ref "U14") (pin "89") (pinfunction "PB18_89") (pintype "bidirectional"))
    )
    (net (code "265") (name "unconnected-(U14-PB19-Pad90)") (class "Default")
      (node (ref "U14") (pin "90") (pinfunction "PB19_90") (pintype "bidirectional"))
    )
    (net (code "266") (name "unconnected-(U14-PB20-Pad91)") (class "Default")
      (node (ref "U14") (pin "91") (pinfunction "PB20_91") (pintype "bidirectional"))
    )
    (net (code "267") (name "unconnected-(U14-PB21-Pad92)") (class "Default")
      (node (ref "U14") (pin "92") (pinfunction "PB21_92") (pintype "bidirectional"))
    )
    (net (code "268") (name "unconnected-(U14-PB22-Pad141)") (class "Default")
      (node (ref "U14") (pin "141") (pinfunction "PB22_141") (pintype "bidirectional"))
    )
    (net (code "269") (name "unconnected-(U14-PB23-Pad142)") (class "Default")
      (node (ref "U14") (pin "142") (pinfunction "PB23_142") (pintype "bidirectional"))
    )
    (net (code "270") (name "unconnected-(U14-PB24-Pad143)") (class "Default")
      (node (ref "U14") (pin "143") (pinfunction "PB24_143") (pintype "bidirectional"))
    )
    (net (code "271") (name "unconnected-(U14-PB26-Pad1)") (class "Default")
      (node (ref "U14") (pin "1") (pinfunction "PB26_1") (pintype "bidirectional"))
    )
    (net (code "272") (name "unconnected-(U14-PB27-Pad68)") (class "Default")
      (node (ref "U14") (pin "68") (pinfunction "PB27_68") (pintype "bidirectional"))
    )
    (net (code "273") (name "unconnected-(U14-PC1-Pad55)") (class "Default")
      (node (ref "U14") (pin "55") (pinfunction "PC1_55") (pintype "bidirectional"))
    )
    (net (code "274") (name "unconnected-(U14-PC2-Pad59)") (class "Default")
      (node (ref "U14") (pin "59") (pinfunction "PC2_59") (pintype "bidirectional"))
    )
    (net (code "275") (name "unconnected-(U14-PC3-Pad60)") (class "Default")
      (node (ref "U14") (pin "60") (pinfunction "PC3_60") (pintype "bidirectional"))
    )
    (net (code "276") (name "unconnected-(U14-PC4-Pad116)") (class "Default")
      (node (ref "U14") (pin "116") (pinfunction "PC4_116") (pintype "bidirectional"))
    )
    (net (code "277") (name "unconnected-(U14-PC5-Pad63)") (class "Default")
      (node (ref "U14") (pin "63") (pinfunction "PC5_63") (pintype "bidirectional"))
    )
    (net (code "278") (name "unconnected-(U14-PC6-Pad64)") (class "Default")
      (node (ref "U14") (pin "64") (pinfunction "PC6_64") (pintype "bidirectional"))
    )
    (net (code "279") (name "unconnected-(U14-PC7-Pad65)") (class "Default")
      (node (ref "U14") (pin "65") (pinfunction "PC7_65") (pintype "bidirectional"))
    )
    (net (code "280") (name "unconnected-(U14-PC8-Pad66)") (class "Default")
      (node (ref "U14") (pin "66") (pinfunction "PC8_66") (pintype "bidirectional"))
    )
    (net (code "281") (name "unconnected-(U14-PC9-Pad67)") (class "Default")
      (node (ref "U14") (pin "67") (pinfunction "PC9_67") (pintype "bidirectional"))
    )
    (net (code "282") (name "unconnected-(U14-PC10-Pad117)") (class "Default")
      (node (ref "U14") (pin "117") (pinfunction "PC10_117") (pintype "bidirectional"))
    )
    (net (code "283") (name "unconnected-(U14-PC11-Pad93)") (class "Default")
      (node (ref "U14") (pin "93") (pinfunction "PC11_93") (pintype "bidirectional"))
    )
    (net (code "284") (name "unconnected-(U14-PC12-Pad94)") (class "Default")
      (node (ref "U14") (pin "94") (pinfunction "PC12_94") (pintype "bidirectional"))
    )
    (net (code "285") (name "unconnected-(U14-PC13-Pad95)") (class "Default")
      (node (ref "U14") (pin "95") (pinfunction "PC13_95") (pintype "bidirectional"))
    )
    (net (code "286") (name "unconnected-(U14-PC14-Pad96)") (class "Default")
      (node (ref "U14") (pin "96") (pinfunction "PC14_96") (pintype "bidirectional"))
    )
    (net (code "287") (name "unconnected-(U14-PC15-Pad97)") (class "Default")
      (node (ref "U14") (pin "97") (pinfunction "PC15_97") (pintype "bidirectional"))
    )
    (net (code "288") (name "unconnected-(U14-PC16-Pad98)") (class "Default")
      (node (ref "U14") (pin "98") (pinfunction "PC16_98") (pintype "bidirectional"))
    )
    (net (code "289") (name "unconnected-(U14-PC17-Pad99)") (class "Default")
      (node (ref "U14") (pin "99") (pinfunction "PC17_99") (pintype "bidirectional"))
    )
    (net (code "290") (name "unconnected-(U14-PC18-Pad100)") (class "Default")
      (node (ref "U14") (pin "100") (pinfunction "PC18_100") (pintype "bidirectional"))
    )
    (net (code "291") (name "unconnected-(U14-PC19-Pad101)") (class "Default")
      (node (ref "U14") (pin "101") (pinfunction "PC19_101") (pintype "bidirectional"))
    )
    (net (code "292") (name "unconnected-(U14-PC20-Pad131)") (class "Default")
      (node (ref "U14") (pin "131") (pinfunction "PC20_131") (pintype "bidirectional"))
    )
    (net (code "293") (name "unconnected-(U14-PC26-Pad137)") (class "Default")
      (node (ref "U14") (pin "137") (pinfunction "PC26_137") (pintype "bidirectional"))
    )
    (net (code "294") (name "unconnected-(U14-PC27-Pad138)") (class "Default")
      (node (ref "U14") (pin "138") (pinfunction "PC27_138") (pintype "bidirectional"))
    )
    (net (code "295") (name "unconnected-(U14-PC29-Pad102)") (class "Default")
      (node (ref "U14") (pin "102") (pinfunction "PC29_102") (pintype "bidirectional"))
    )
    (net (code "296") (name "unconnected-(U14-PC30-Pad103)") (class "Default")
      (node (ref "U14") (pin "103") (pinfunction "PC30_103") (pintype "bidirectional"))
    )
    (net (code "297") (name "unconnected-(U14-PD0-Pad13)") (class "Default")
      (node (ref "U14") (pin "13") (pinfunction "PD0_13") (pintype "bidirectional"))
    )
    (net (code "298") (name "unconnected-(U14-PD1-Pad14)") (class "Default")
      (node (ref "U14") (pin "14") (pinfunction "PD1_14") (pintype "bidirectional"))
    )
    (net (code "299") (name "unconnected-(U14-PD2-Pad15)") (class "Default")
      (node (ref "U14") (pin "15") (pinfunction "PD2_15") (pintype "bidirectional"))
    )
    (net (code "300") (name "unconnected-(U14-PD3-Pad16)") (class "Default")
      (node (ref "U14") (pin "16") (pinfunction "PD3_16") (pintype "bidirectional"))
    )
    (net (code "301") (name "unconnected-(U14-PD4-Pad17)") (class "Default")
      (node (ref "U14") (pin "17") (pinfunction "PD4_17") (pintype "bidirectional"))
    )
    (net (code "302") (name "unconnected-(U14-PD5-Pad18)") (class "Default")
      (node (ref "U14") (pin "18") (pinfunction "PD5_18") (pintype "bidirectional"))
    )
    (net (code "303") (name "unconnected-(U14-PD6-Pad19)") (class "Default")
      (node (ref "U14") (pin "19") (pinfunction "PD6_19") (pintype "bidirectional"))
    )
    (net (code "304") (name "unconnected-(U14-PD9-Pad22)") (class "Default")
      (node (ref "U14") (pin "22") (pinfunction "PD9_22") (pintype "bidirectional"))
    )
    (net (code "305") (name "unconnected-(U14-PD10-Pad32)") (class "Default")
      (node (ref "U14") (pin "32") (pinfunction "PD10_32") (pintype "bidirectional"))
    )
    (net (code "306") (name "unconnected-(U14-SHDN-Pad50)") (class "Default")
      (node (ref "U14") (pin "50") (pinfunction "SHDN_50") (pintype "bidirectional"))
    )
    (net (code "307") (name "unconnected-(U17-1IN+-Pad3)") (class "Default")
      (node (ref "U17") (pin "3") (pinfunction "1IN+_3") (pintype "input"))
    )
    (net (code "308") (name "unconnected-(U17-1IN--Pad2)") (class "Default")
      (node (ref "U17") (pin "2") (pinfunction "1IN-_2") (pintype "input"))
    )
    (net (code "309") (name "unconnected-(U17-1OUT-Pad1)") (class "Default")
      (node (ref "U17") (pin "1") (pinfunction "1OUT_1") (pintype "output"))
    )
  )
)
